# 0413.net
KiCad netlist of a schematic drawn in Altium Designer
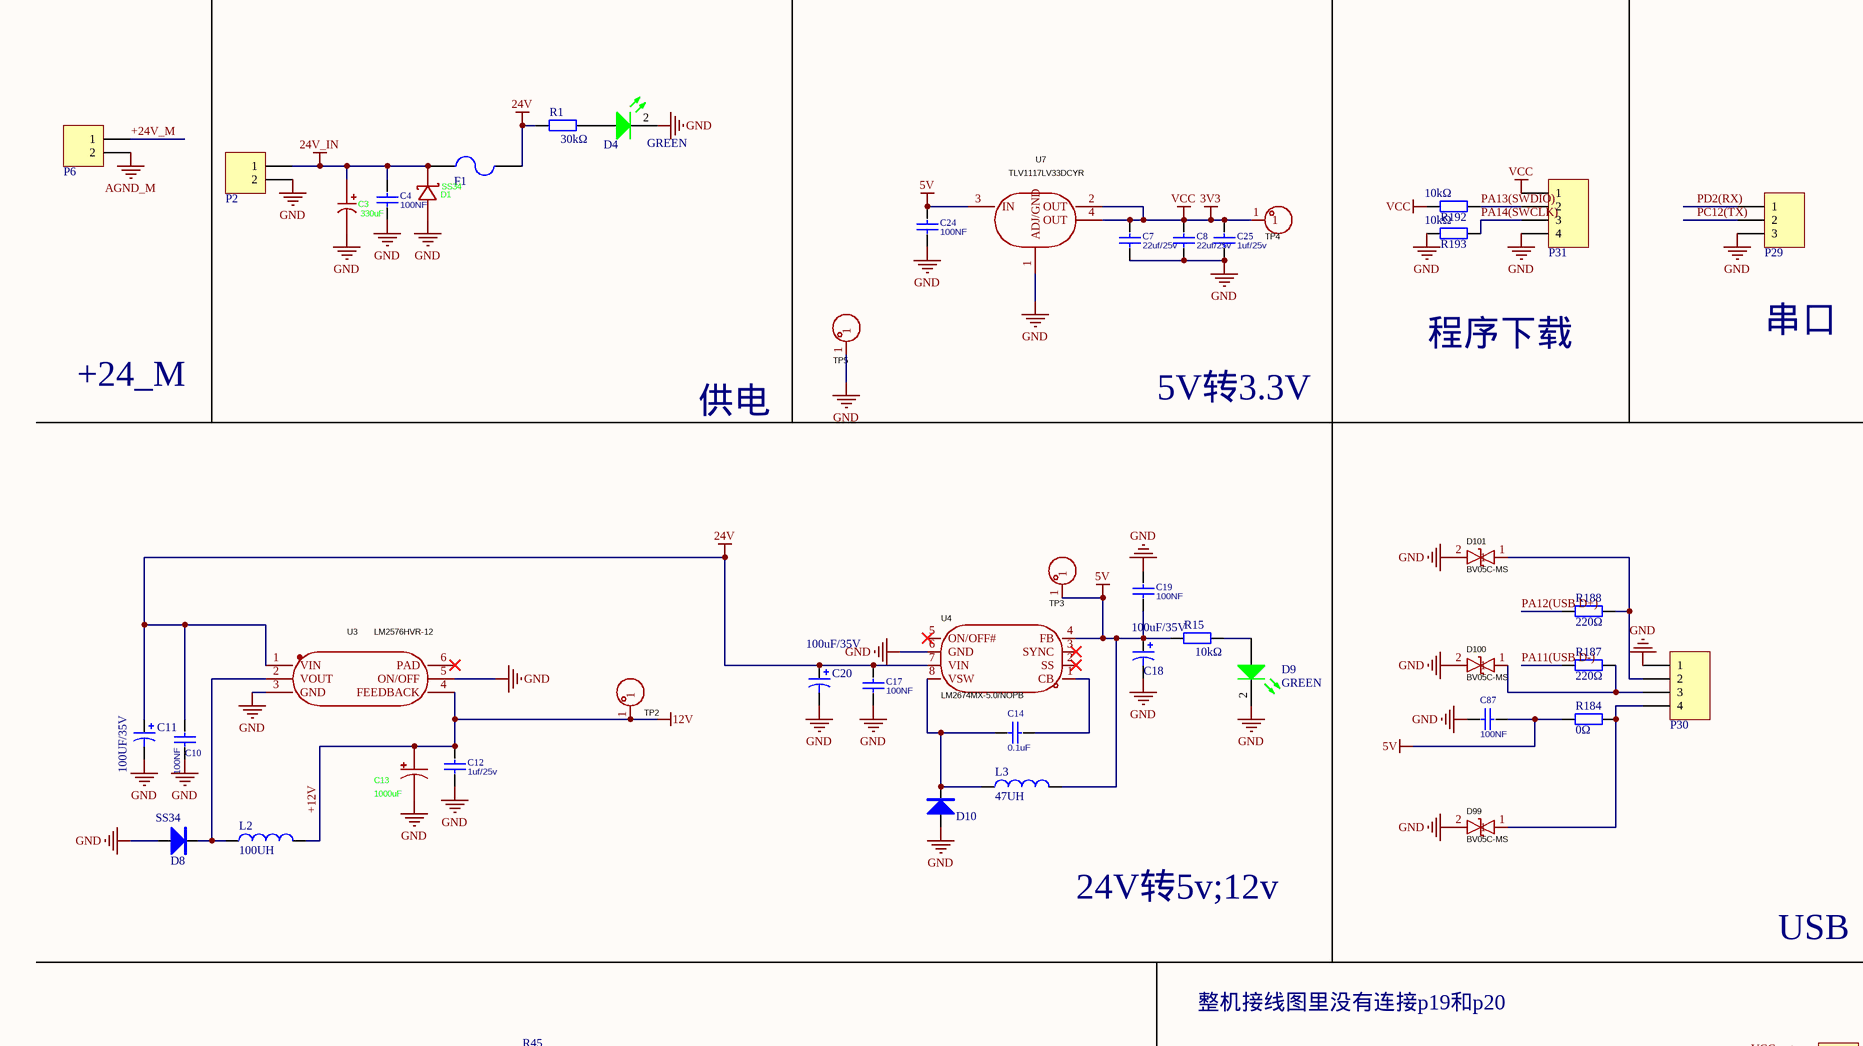
[diagram p0: 主控板0413.SchDoc, top left]
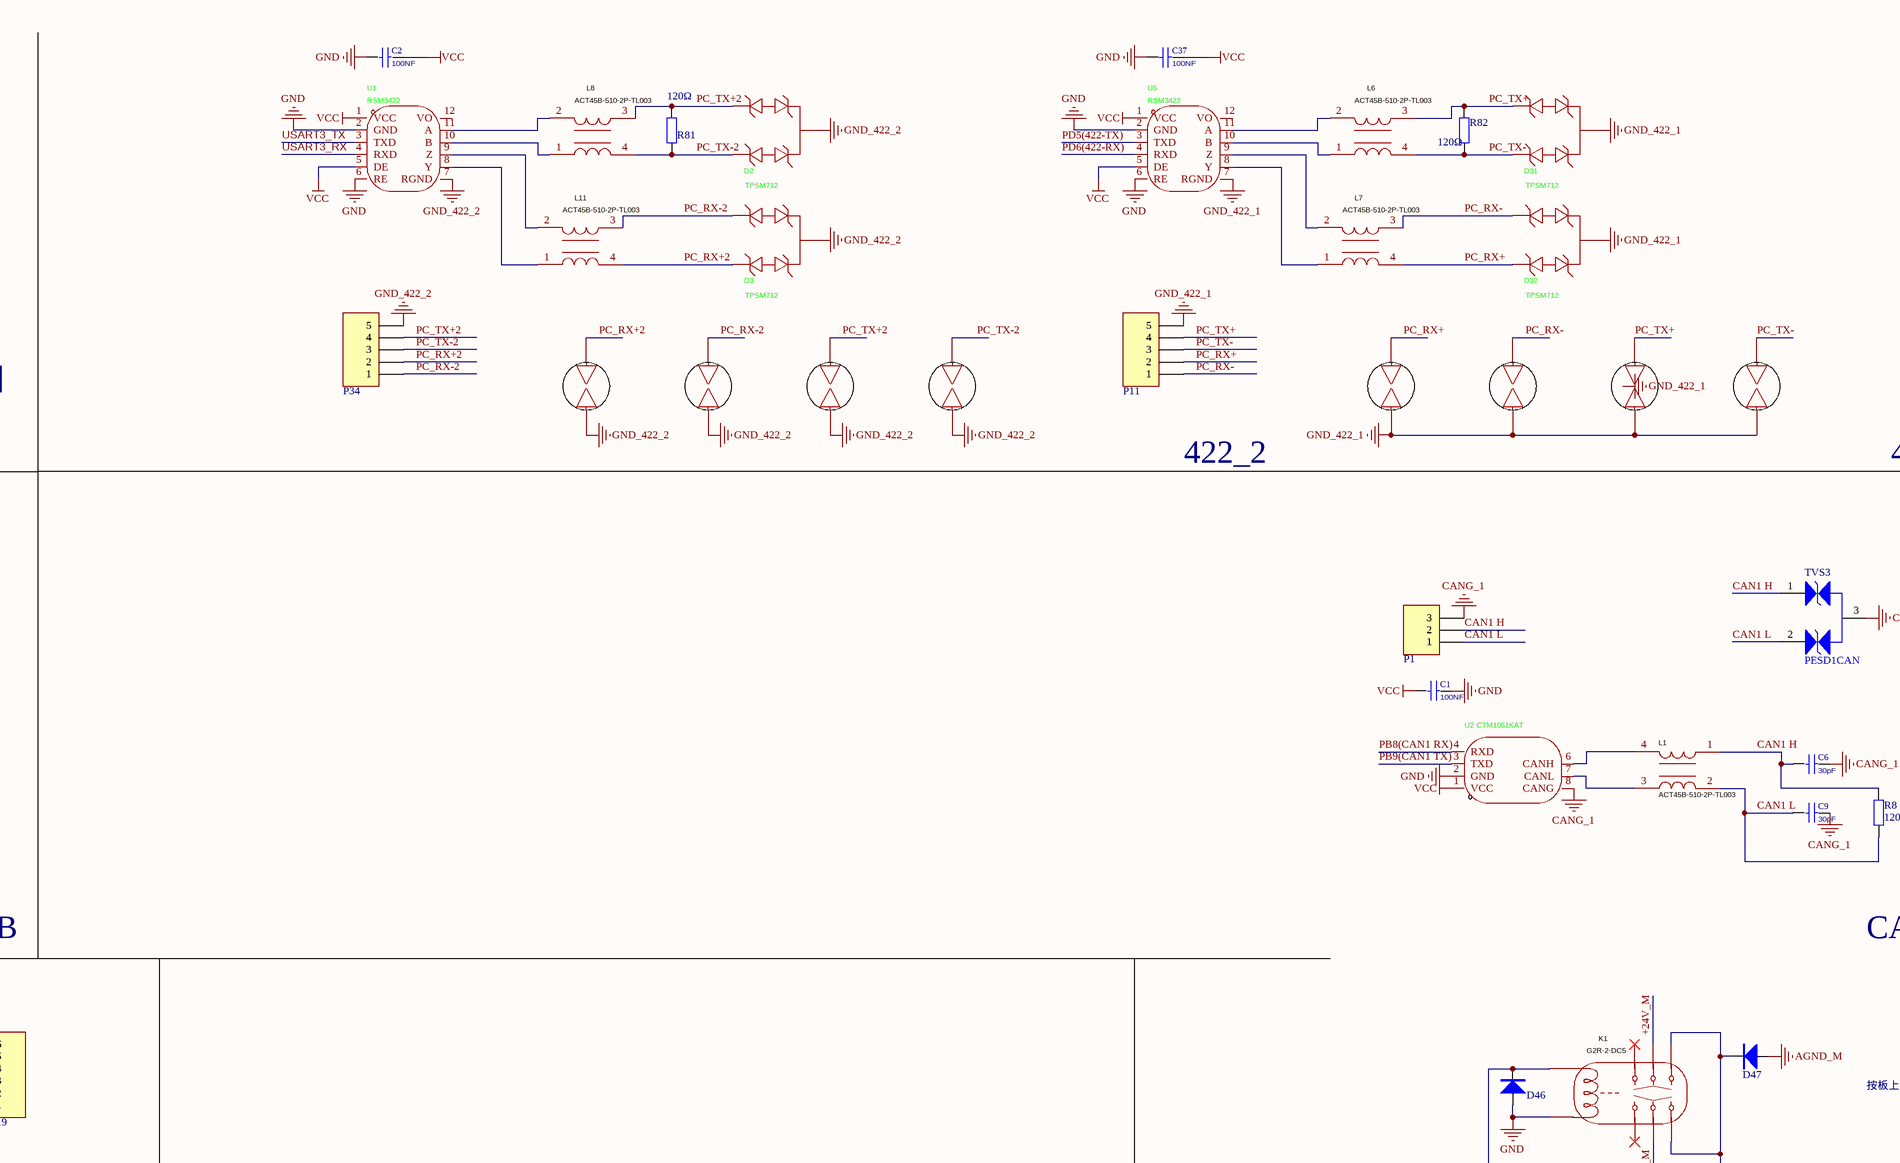
[diagram p1: 主控板0413.SchDoc, top middle]
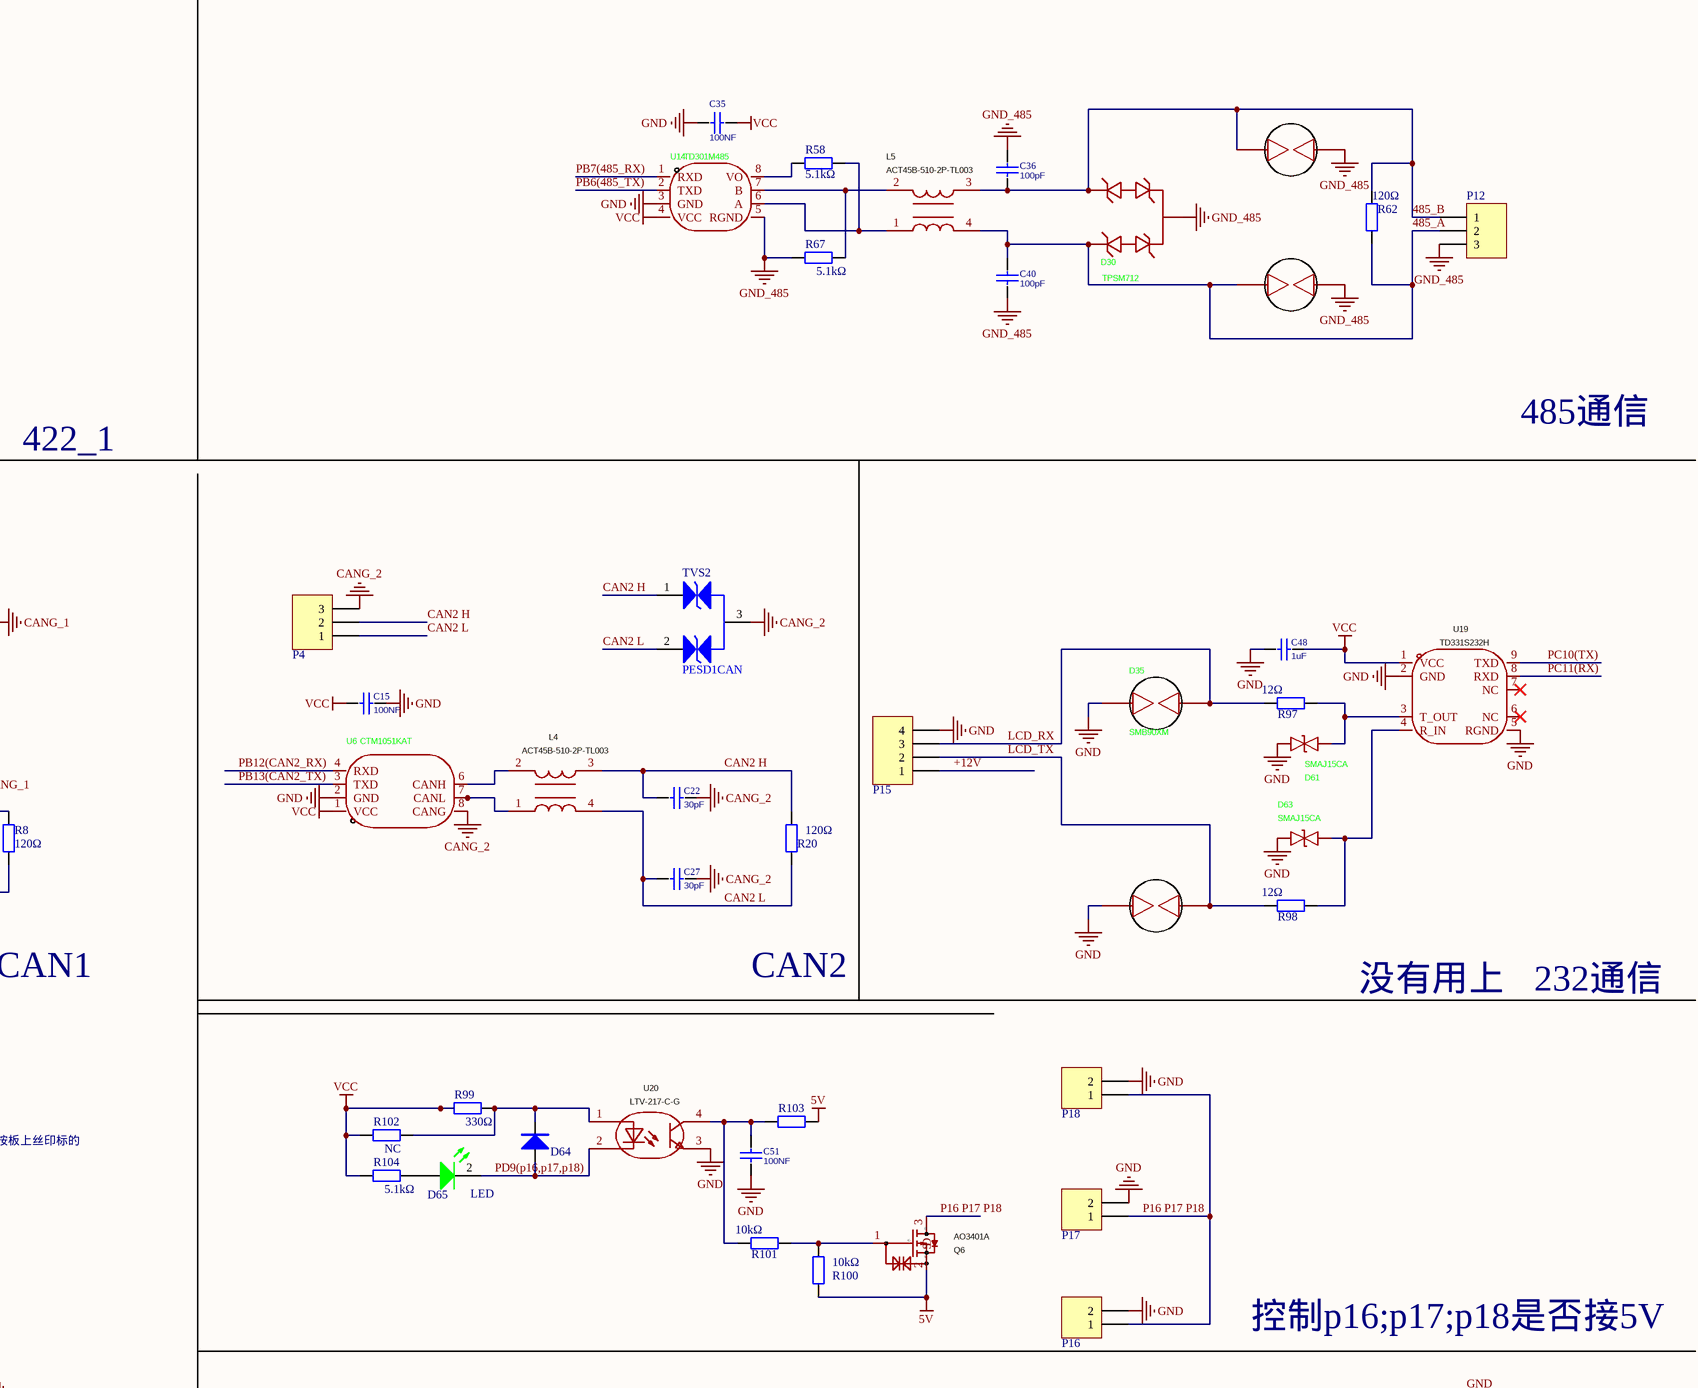
[diagram p2: 主控板0413.SchDoc, top right]
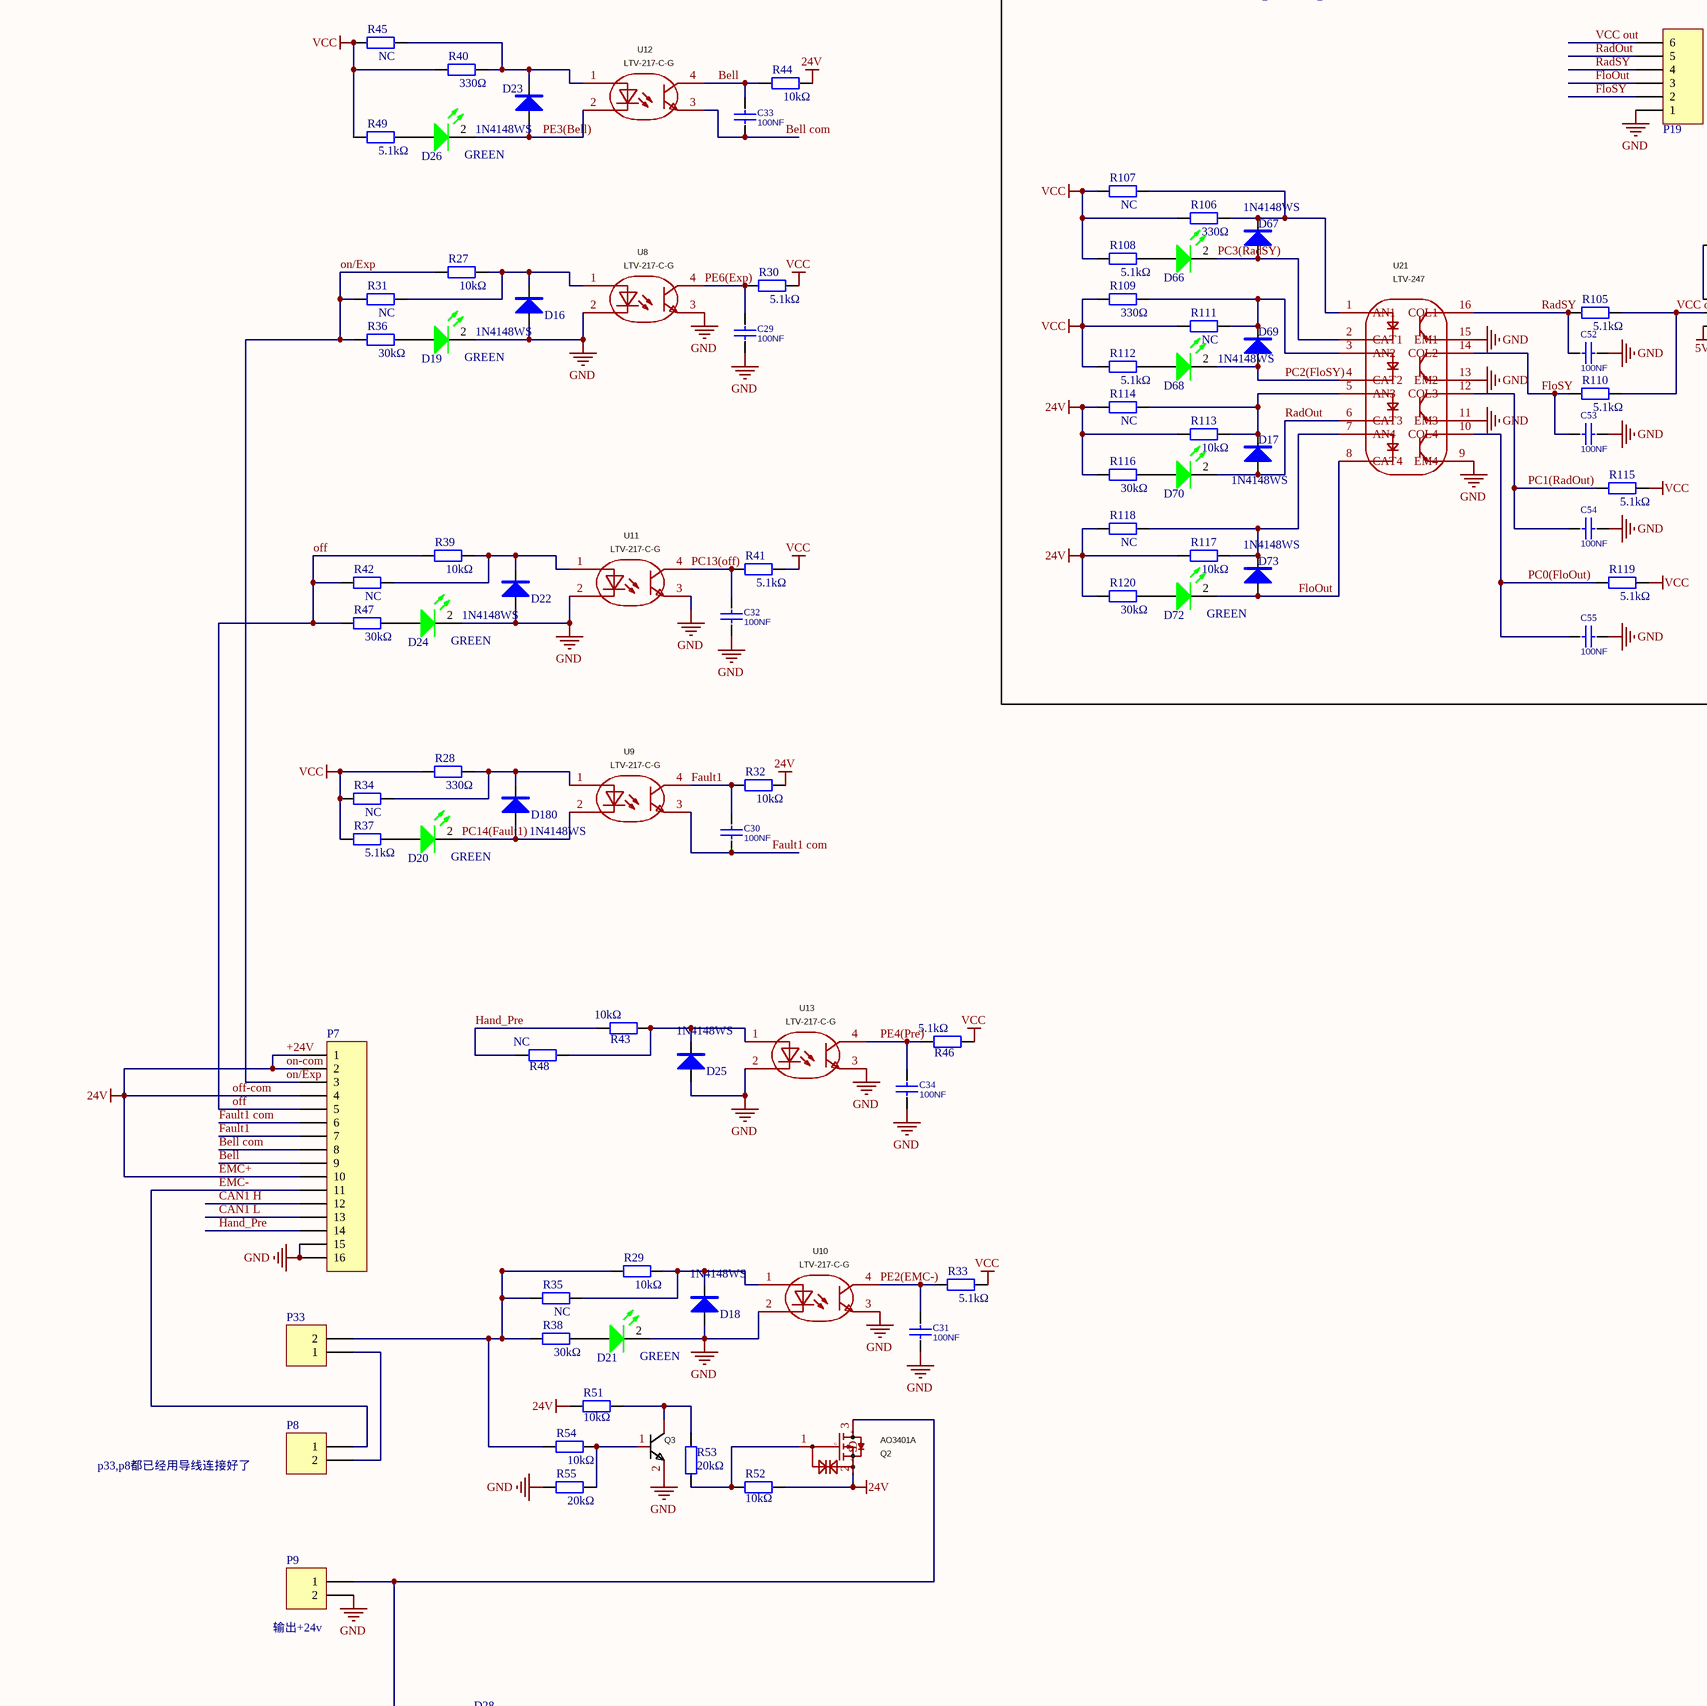
[diagram p3: 主控板0413.SchDoc, centre left]
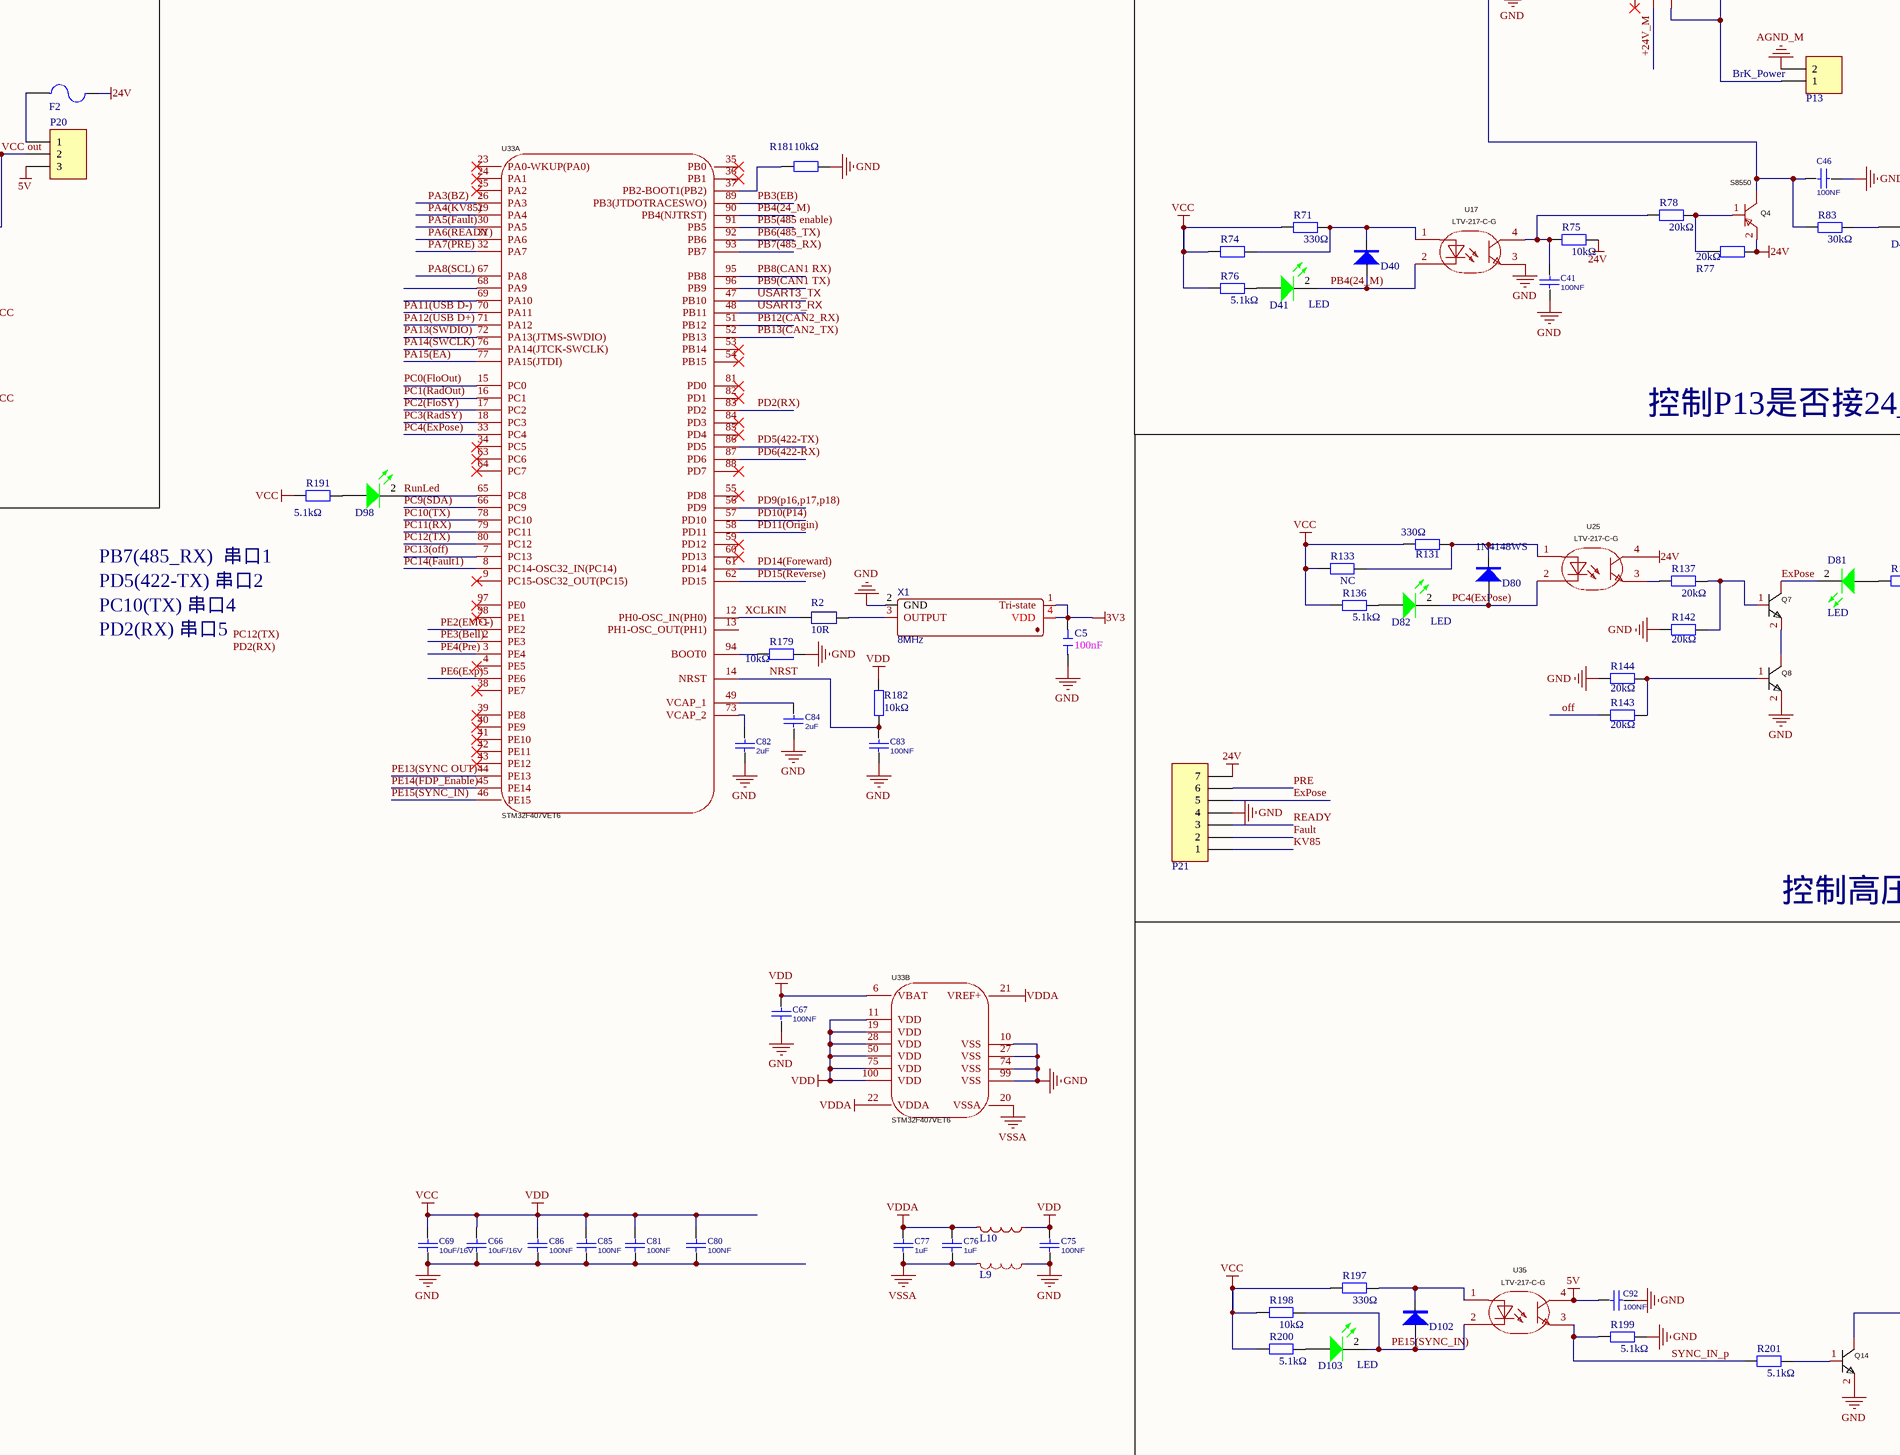
[diagram p4: 主控板0413.SchDoc, centre middle]
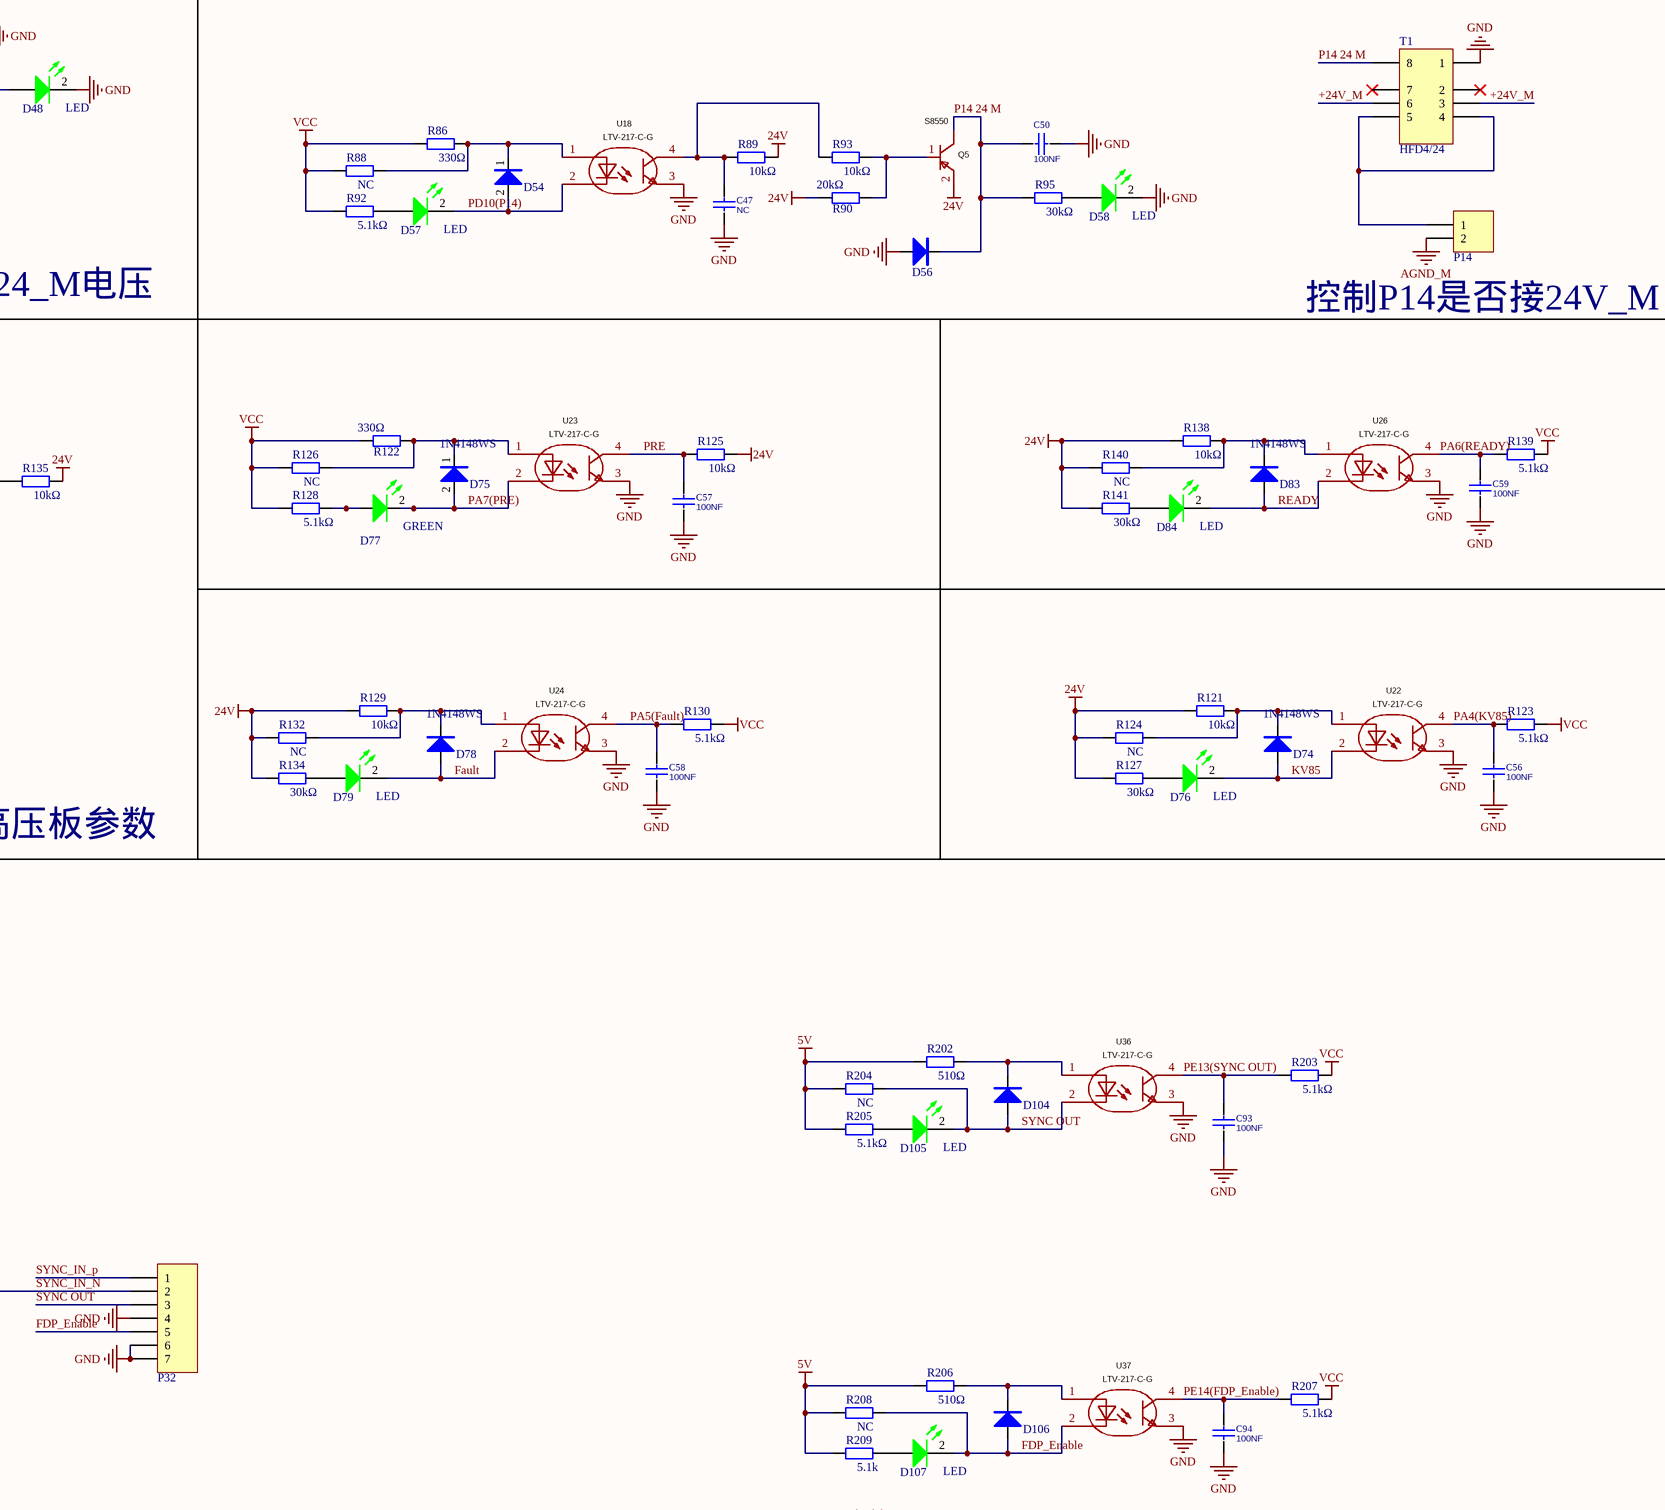
[diagram p5: 主控板0413.SchDoc, centre right]
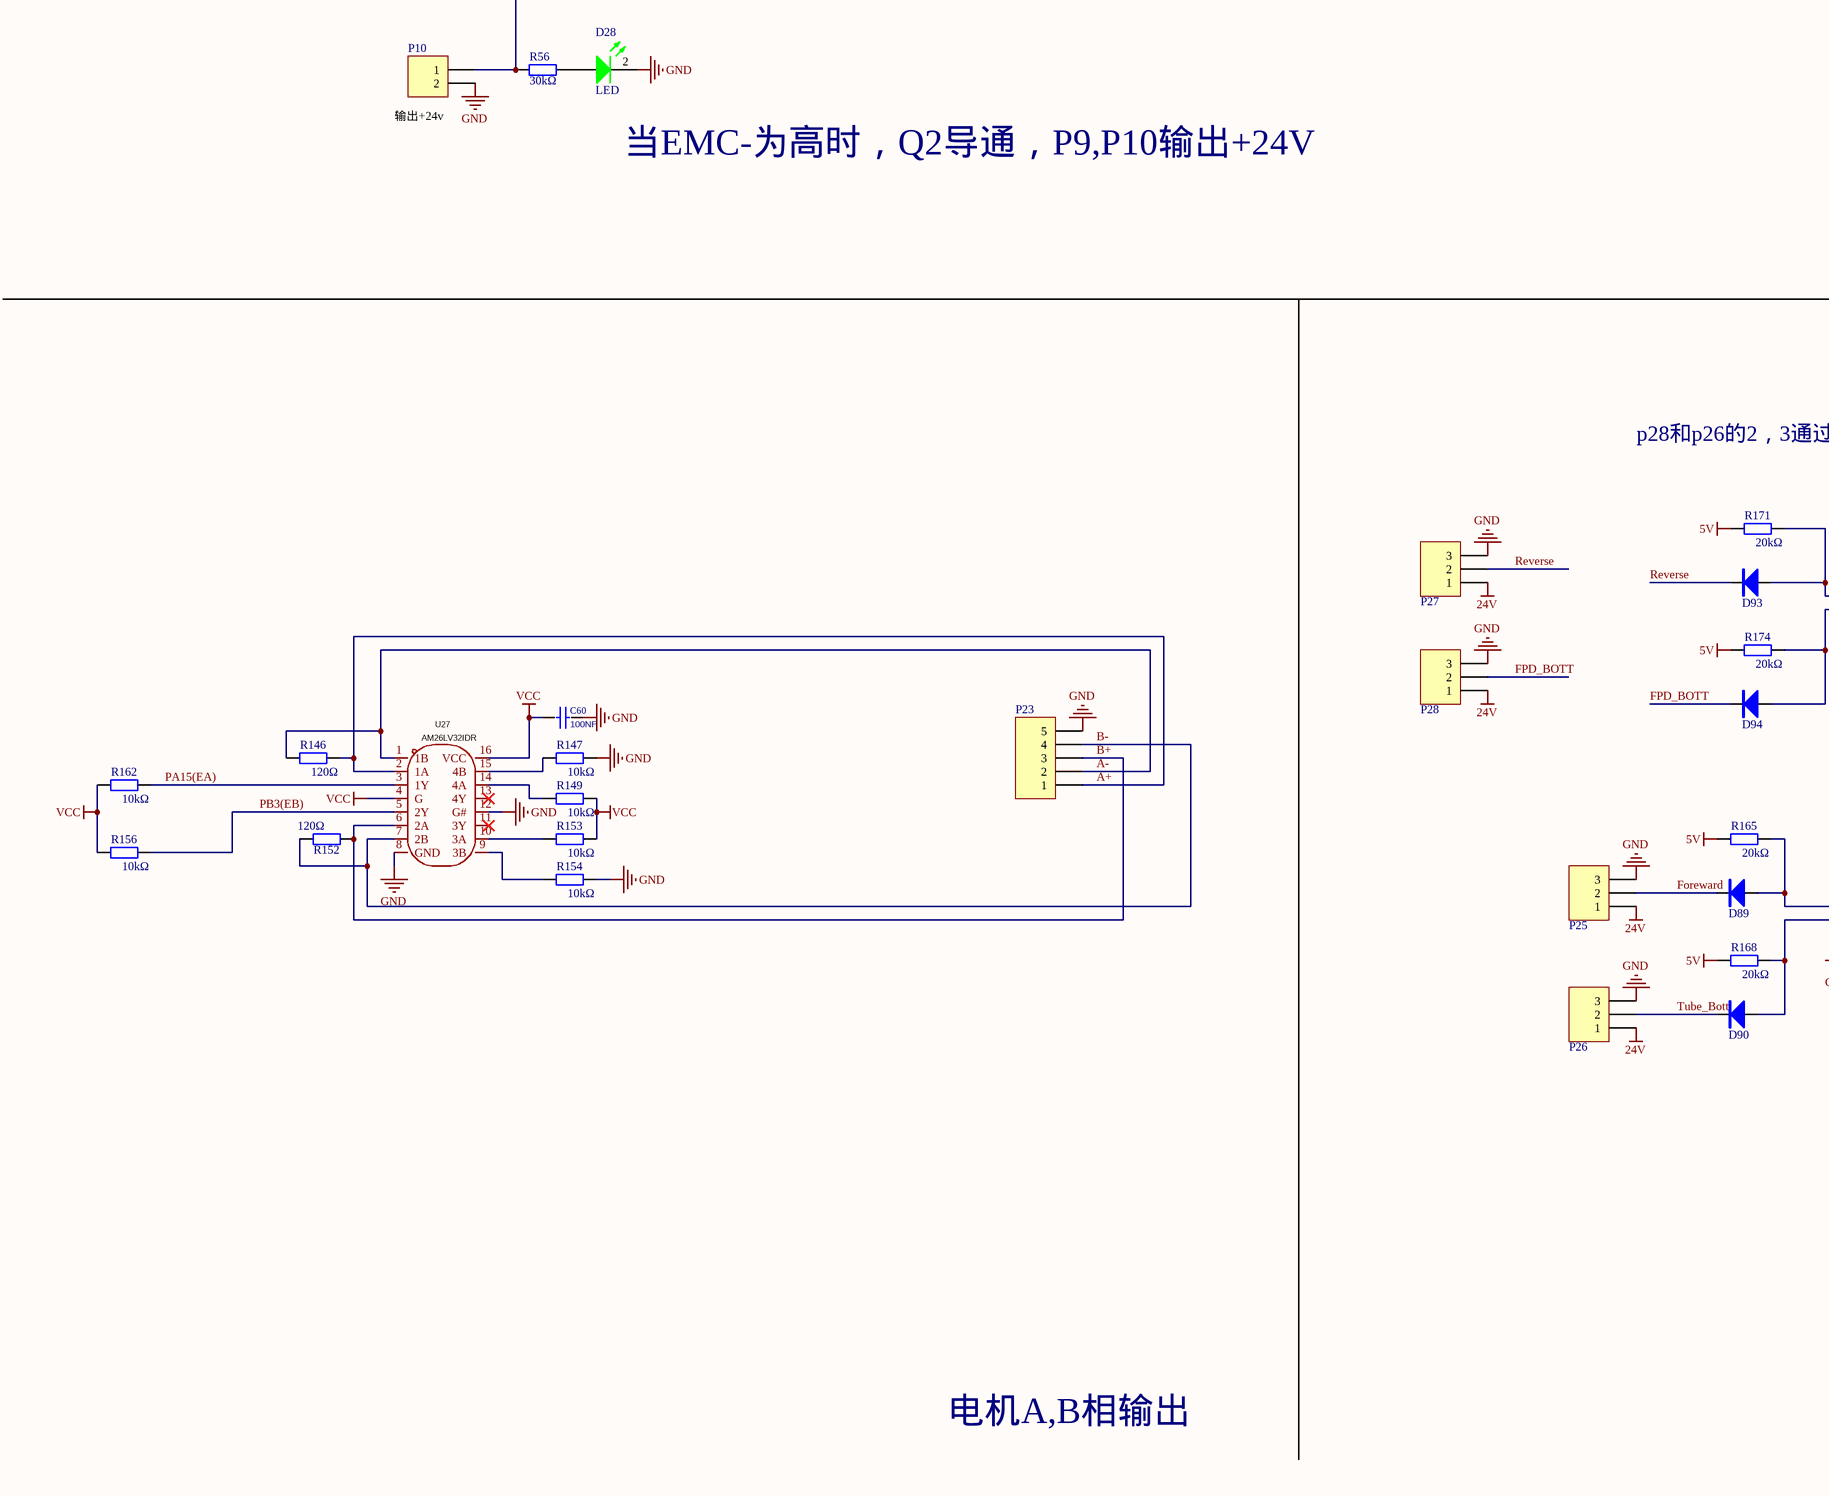
[diagram p6: 主控板0413.SchDoc, bottom left]
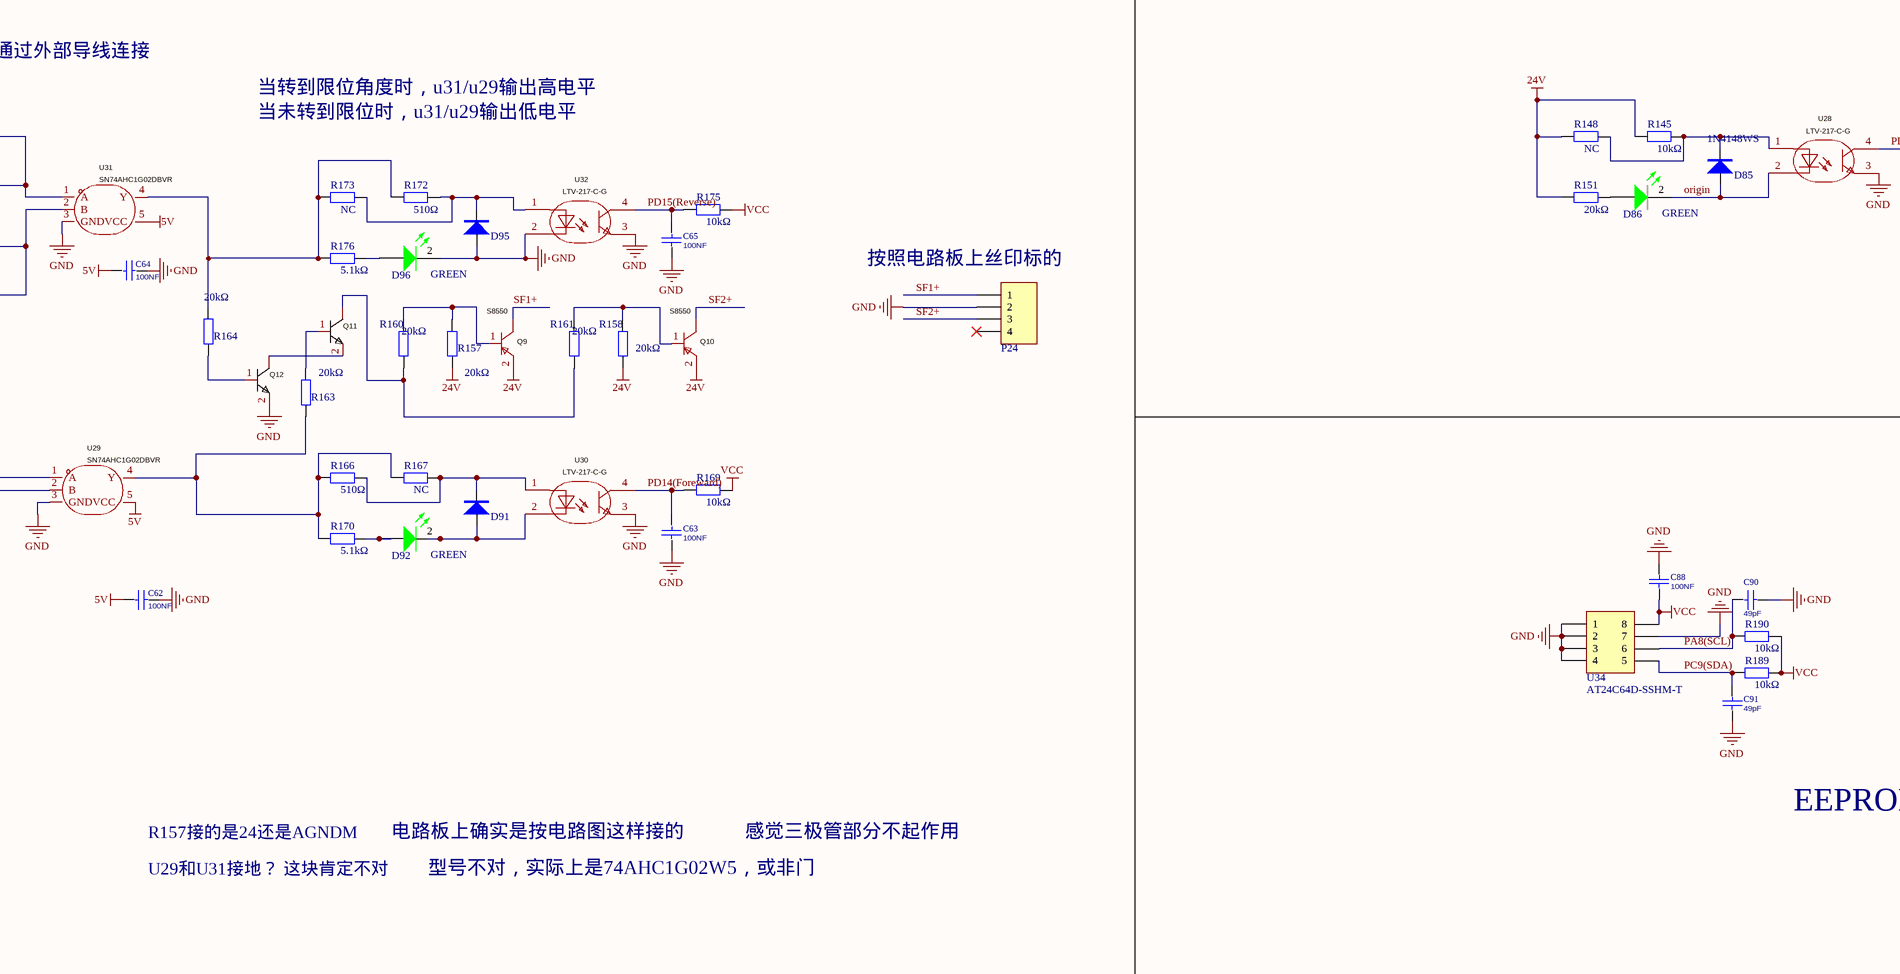
[diagram p7: 主控板0413.SchDoc, bottom middle]
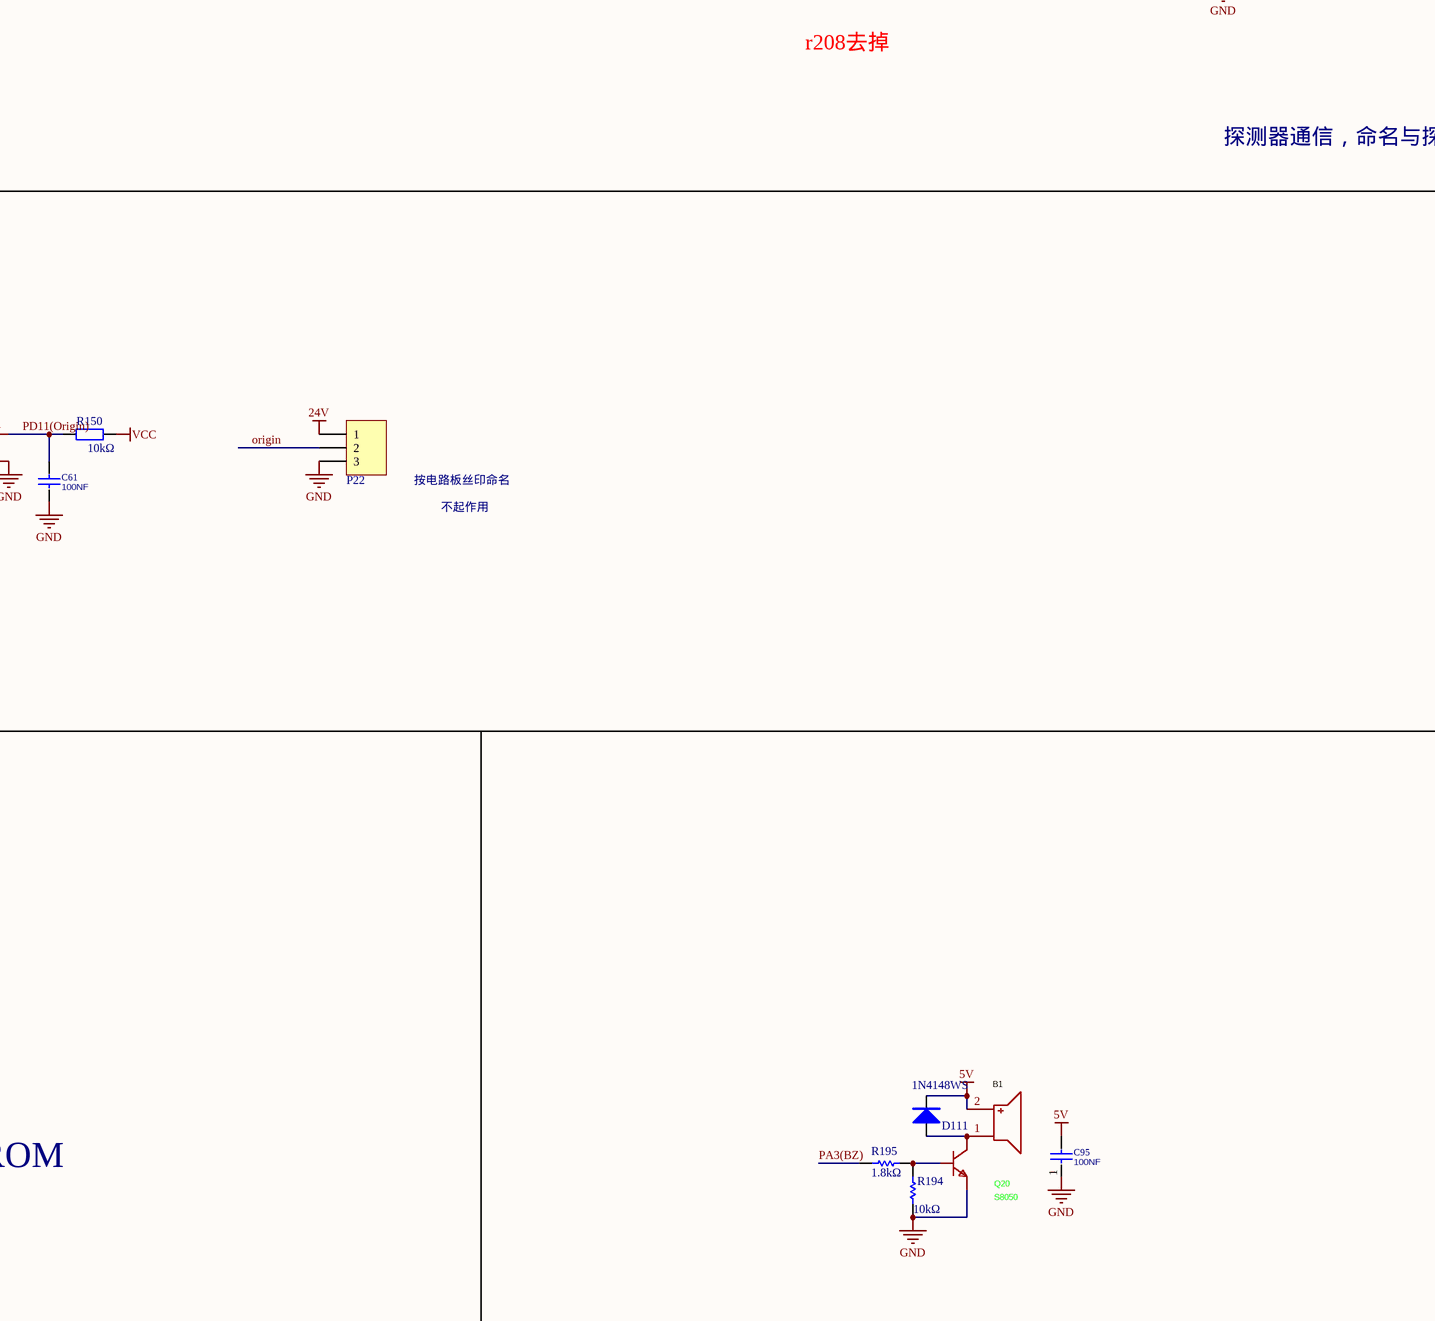
[diagram p8: 主控板0413.SchDoc, bottom right]

(export (version "E")
  (design (tool "Eeschema 10.0.6"))
  (components
    (comp (ref "B1")
      (value "~")
      (footprint "CPA5")
      (fields (field (name "MANUFACTURER") "华能") (field (name "MANUFACTURER PART") "QMB-09B-03"))
      (libsource (lib "小板1_1") (part "QMB-09B-03"))
    )
    (comp (ref "C1")
      (value "100NF")
      (footprint "C0603")
      (description "贴片电容 10uF/X5R/20%/6.3V")
      (fields (field (name "PUBLISHER") "Altium Limited"))
      (libsource (lib "*") (part "CAP"))
    )
    (comp (ref "C2")
      (value "100NF")
      (footprint "C0603")
      (description "贴片电容 10uF/X5R/20%/6.3V")
      (fields (field (name "PUBLISHER") "Altium Limited"))
      (libsource (lib "*") (part "CAP"))
    )
    (comp (ref "C3")
      (value "330uF")
      (footprint "CAP-TH_BD8.0-P3.50-D0.5-FD")
      (fields (field (name "MANUFACTURER PART") "JBLH2331M035D120RLM 330UF 35V"))
      (libsource (lib "altium-import") (part "root_3_JBLH2331M035D120RLM 330UF 35V_"))
    )
    (comp (ref "C4")
      (value "100NF")
      (footprint "C1206")
      (description "贴片电容 10uF/X5R/20%/6.3V")
      (fields (field (name "PUBLISHER") "Altium Limited"))
      (libsource (lib "*") (part "CAP"))
    )
    (comp (ref "C5")
      (value "100nF")
      (footprint "C0603")
      (description "Capacitor")
      (libsource (lib "") (part "CAP_1"))
    )
    (comp (ref "C6")
      (value "30pF")
      (footprint "C0603")
      (description "贴片电容 10uF/X5R/20%/6.3V")
      (fields (field (name "PUBLISHER") "Altium Limited"))
      (libsource (lib "*") (part "CAP"))
    )
    (comp (ref "C7")
      (value "22uf/25v")
      (footprint "C0805")
      (fields (field (name "PUBLISHER") "Altium Limited"))
      (libsource (lib "*") (part "CAP"))
    )
    (comp (ref "C8")
      (value "22uf/25v")
      (footprint "C0805")
      (fields (field (name "PUBLISHER") "Altium Limited"))
      (libsource (lib "*") (part "CAP"))
    )
    (comp (ref "C9")
      (value "30pF")
      (footprint "C0603")
      (description "贴片电容 10uF/X5R/20%/6.3V")
      (fields (field (name "PUBLISHER") "Altium Limited"))
      (libsource (lib "*") (part "CAP"))
    )
    (comp (ref "C10")
      (value "100NF")
      (footprint "C0603")
      (description "贴片电容 10uF/X5R/20%/6.3V")
      (fields (field (name "PUBLISHER") "Altium Limited"))
      (libsource (lib "*") (part "CAP"))
    )
    (comp (ref "C11")
      (value "100UF/35V")
      (footprint "CAP10")
      (description "Polarized Capacitor (Radial)")
      (fields (field (name "PUBLISHER") "Altium Limited"))
      (libsource (lib "Miscellaneous Devices") (part "Cap Pol1"))
    )
    (comp (ref "C12")
      (value "1uf/25v")
      (footprint "C0603")
      (fields (field (name "PUBLISHER") "Altium Limited"))
      (libsource (lib "*") (part "CAP"))
    )
    (comp (ref "C13")
      (value "1000uF")
      (footprint "CAP-TH_BD10.0-P5.00-D1.0-FD")
      (fields (field (name "MANUFACTURER PART") "ORZ102M1CBK-1012"))
      (libsource (lib "altium-import") (part "root_0_ORZ102M1CBK-1012_"))
    )
    (comp (ref "C14")
      (value "0.1uF")
      (footprint "C0603")
      (fields (field (name "PUBLISHER") "Altium Limited"))
      (libsource (lib "*") (part "CAP"))
    )
    (comp (ref "C15")
      (value "100NF")
      (footprint "C0603")
      (description "贴片电容 10uF/X5R/20%/6.3V")
      (fields (field (name "PUBLISHER") "Altium Limited"))
      (libsource (lib "*") (part "CAP"))
    )
    (comp (ref "C17")
      (value "100NF")
      (footprint "C1206")
      (description "贴片电容 10uF/X5R/20%/6.3V")
      (fields (field (name "PUBLISHER") "Altium Limited"))
      (libsource (lib "*") (part "CAP"))
    )
    (comp (ref "C18")
      (value "100uF/35V")
      (footprint "CAP10")
      (description "Polarized Capacitor (Radial)")
      (fields (field (name "PUBLISHER") "Altium Limited"))
      (libsource (lib "Miscellaneous Devices") (part "Cap Pol1"))
    )
    (comp (ref "C19")
      (value "100NF")
      (footprint "C0603")
      (description "贴片电容 10uF/X5R/20%/6.3V")
      (fields (field (name "PUBLISHER") "Altium Limited"))
      (libsource (lib "*") (part "CAP"))
    )
    (comp (ref "C20")
      (value "100uF/35V")
      (footprint "CAP10")
      (description "Polarized Capacitor (Radial)")
      (fields (field (name "PUBLISHER") "Altium Limited"))
      (libsource (lib "Miscellaneous Devices") (part "Cap Pol1"))
    )
    (comp (ref "C22")
      (value "30pF")
      (footprint "C0603")
      (description "贴片电容 10uF/X5R/20%/6.3V")
      (fields (field (name "PUBLISHER") "Altium Limited"))
      (libsource (lib "*") (part "CAP"))
    )
    (comp (ref "C24")
      (value "100NF")
      (footprint "C0603")
      (description "贴片电容 10uF/X5R/20%/6.3V")
      (fields (field (name "PUBLISHER") "Altium Limited"))
      (libsource (lib "*") (part "CAP"))
    )
    (comp (ref "C25")
      (value "1uf/25v")
      (footprint "C0603")
      (fields (field (name "PUBLISHER") "Altium Limited"))
      (libsource (lib "*") (part "CAP"))
    )
    (comp (ref "C27")
      (value "30pF")
      (footprint "C0603")
      (description "贴片电容 10uF/X5R/20%/6.3V")
      (fields (field (name "PUBLISHER") "Altium Limited"))
      (libsource (lib "*") (part "CAP"))
    )
    (comp (ref "C29")
      (value "100NF")
      (footprint "C0603")
      (description "贴片电容 10uF/X5R/20%/6.3V")
      (fields (field (name "PUBLISHER") "Altium Limited"))
      (libsource (lib "*") (part "CAP"))
    )
    (comp (ref "C30")
      (value "100NF")
      (footprint "C0603")
      (description "贴片电容 10uF/X5R/20%/6.3V")
      (fields (field (name "PUBLISHER") "Altium Limited"))
      (libsource (lib "*") (part "CAP"))
    )
    (comp (ref "C31")
      (value "100NF")
      (footprint "C0603")
      (description "贴片电容 10uF/X5R/20%/6.3V")
      (fields (field (name "PUBLISHER") "Altium Limited"))
      (libsource (lib "*") (part "CAP"))
    )
    (comp (ref "C32")
      (value "100NF")
      (footprint "C0603")
      (description "贴片电容 10uF/X5R/20%/6.3V")
      (fields (field (name "PUBLISHER") "Altium Limited"))
      (libsource (lib "*") (part "CAP"))
    )
    (comp (ref "C33")
      (value "100NF")
      (footprint "C0603")
      (description "贴片电容 10uF/X5R/20%/6.3V")
      (fields (field (name "PUBLISHER") "Altium Limited"))
      (libsource (lib "*") (part "CAP"))
    )
    (comp (ref "C34")
      (value "100NF")
      (footprint "C0603")
      (description "贴片电容 10uF/X5R/20%/6.3V")
      (fields (field (name "PUBLISHER") "Altium Limited"))
      (libsource (lib "*") (part "CAP"))
    )
    (comp (ref "C35")
      (value "100NF")
      (footprint "C0603")
      (description "贴片电容 10uF/X5R/20%/6.3V")
      (fields (field (name "PUBLISHER") "Altium Limited"))
      (libsource (lib "*") (part "CAP"))
    )
    (comp (ref "C36")
      (value "100pF")
      (footprint "C0603")
      (description "贴片电容 10uF/X5R/20%/6.3V")
      (fields (field (name "PUBLISHER") "Altium Limited"))
      (libsource (lib "*") (part "CAP"))
    )
    (comp (ref "C37")
      (value "100NF")
      (footprint "C0603")
      (description "贴片电容 10uF/X5R/20%/6.3V")
      (fields (field (name "PUBLISHER") "Altium Limited"))
      (libsource (lib "*") (part "CAP"))
    )
    (comp (ref "C40")
      (value "100pF")
      (footprint "C0603")
      (description "贴片电容 10uF/X5R/20%/6.3V")
      (fields (field (name "PUBLISHER") "Altium Limited"))
      (libsource (lib "*") (part "CAP"))
    )
    (comp (ref "C41")
      (value "100NF")
      (footprint "C0603")
      (description "贴片电容 10uF/X5R/20%/6.3V")
      (fields (field (name "PUBLISHER") "Altium Limited"))
      (libsource (lib "*") (part "CAP"))
    )
    (comp (ref "C46")
      (value "100NF")
      (footprint "C0603")
      (description "贴片电容 10uF/X5R/20%/6.3V")
      (fields (field (name "PUBLISHER") "Altium Limited"))
      (libsource (lib "*") (part "CAP"))
    )
    (comp (ref "C47")
      (value "NC")
      (footprint "C0603")
      (description "贴片电容 10uF/X5R/20%/6.3V")
      (fields (field (name "PUBLISHER") "Altium Limited"))
      (libsource (lib "*") (part "CAP"))
    )
    (comp (ref "C48")
      (value "1uF")
      (footprint "C0603")
      (description "贴片电容 10uF/X5R/20%/6.3V")
      (fields (field (name "PUBLISHER") "Altium Limited"))
      (libsource (lib "*") (part "CAP"))
    )
    (comp (ref "C50")
      (value "100NF")
      (footprint "C0603")
      (description "贴片电容 10uF/X5R/20%/6.3V")
      (fields (field (name "PUBLISHER") "Altium Limited"))
      (libsource (lib "*") (part "CAP"))
    )
    (comp (ref "C51")
      (value "100NF")
      (footprint "C0603")
      (description "贴片电容 10uF/X5R/20%/6.3V")
      (fields (field (name "PUBLISHER") "Altium Limited"))
      (libsource (lib "*") (part "CAP"))
    )
    (comp (ref "C52")
      (value "100NF")
      (footprint "C0603")
      (description "贴片电容 10uF/X5R/20%/6.3V")
      (fields (field (name "PUBLISHER") "Altium Limited"))
      (libsource (lib "*") (part "CAP"))
    )
    (comp (ref "C53")
      (value "100NF")
      (footprint "C0603")
      (description "贴片电容 10uF/X5R/20%/6.3V")
      (fields (field (name "PUBLISHER") "Altium Limited"))
      (libsource (lib "*") (part "CAP"))
    )
    (comp (ref "C54")
      (value "100NF")
      (footprint "C0603")
      (description "贴片电容 10uF/X5R/20%/6.3V")
      (fields (field (name "PUBLISHER") "Altium Limited"))
      (libsource (lib "*") (part "CAP"))
    )
    (comp (ref "C55")
      (value "100NF")
      (footprint "C0603")
      (description "贴片电容 10uF/X5R/20%/6.3V")
      (fields (field (name "PUBLISHER") "Altium Limited"))
      (libsource (lib "*") (part "CAP"))
    )
    (comp (ref "C56")
      (value "100NF")
      (footprint "C0603")
      (description "贴片电容 10uF/X5R/20%/6.3V")
      (fields (field (name "PUBLISHER") "Altium Limited"))
      (libsource (lib "*") (part "CAP"))
    )
    (comp (ref "C57")
      (value "100NF")
      (footprint "C0603")
      (description "贴片电容 10uF/X5R/20%/6.3V")
      (fields (field (name "PUBLISHER") "Altium Limited"))
      (libsource (lib "*") (part "CAP"))
    )
    (comp (ref "C58")
      (value "100NF")
      (footprint "C0603")
      (description "贴片电容 10uF/X5R/20%/6.3V")
      (fields (field (name "PUBLISHER") "Altium Limited"))
      (libsource (lib "*") (part "CAP"))
    )
    (comp (ref "C59")
      (value "100NF")
      (footprint "C0603")
      (description "贴片电容 10uF/X5R/20%/6.3V")
      (fields (field (name "PUBLISHER") "Altium Limited"))
      (libsource (lib "*") (part "CAP"))
    )
    (comp (ref "C60")
      (value "100NF")
      (footprint "C0603")
      (description "贴片电容 10uF/X5R/20%/6.3V")
      (fields (field (name "PUBLISHER") "Altium Limited"))
      (libsource (lib "*") (part "CAP"))
    )
    (comp (ref "C61")
      (value "100NF")
      (footprint "C0603")
      (description "贴片电容 10uF/X5R/20%/6.3V")
      (fields (field (name "PUBLISHER") "Altium Limited"))
      (libsource (lib "*") (part "CAP"))
    )
    (comp (ref "C62")
      (value "100NF")
      (footprint "C0603")
      (description "贴片电容 10uF/X5R/20%/6.3V")
      (fields (field (name "PUBLISHER") "Altium Limited"))
      (libsource (lib "*") (part "CAP"))
    )
    (comp (ref "C63")
      (value "100NF")
      (footprint "C0603")
      (description "贴片电容 10uF/X5R/20%/6.3V")
      (fields (field (name "PUBLISHER") "Altium Limited"))
      (libsource (lib "*") (part "CAP"))
    )
    (comp (ref "C64")
      (value "100NF")
      (footprint "C0603")
      (description "贴片电容 10uF/X5R/20%/6.3V")
      (fields (field (name "PUBLISHER") "Altium Limited"))
      (libsource (lib "*") (part "CAP"))
    )
    (comp (ref "C65")
      (value "100NF")
      (footprint "C0603")
      (description "贴片电容 10uF/X5R/20%/6.3V")
      (fields (field (name "PUBLISHER") "Altium Limited"))
      (libsource (lib "*") (part "CAP"))
    )
    (comp (ref "C66")
      (value "10uF/16V")
      (footprint "C0603")
      (fields (field (name "PUBLISHER") "Altium Limited"))
      (libsource (lib "*") (part "CAP"))
    )
    (comp (ref "C67")
      (value "100NF")
      (footprint "C0603")
      (description "贴片电容 10uF/X5R/20%/6.3V")
      (fields (field (name "PUBLISHER") "Altium Limited"))
      (libsource (lib "*") (part "CAP"))
    )
    (comp (ref "C69")
      (value "10uF/16V")
      (footprint "C0603")
      (fields (field (name "PUBLISHER") "Altium Limited"))
      (libsource (lib "*") (part "CAP"))
    )
    (comp (ref "C75")
      (value "100NF")
      (footprint "C0603")
      (description "贴片电容 10uF/X5R/20%/6.3V")
      (fields (field (name "PUBLISHER") "Altium Limited"))
      (libsource (lib "*") (part "CAP"))
    )
    (comp (ref "C76")
      (value "1uF")
      (footprint "C0603")
      (description "贴片电容 10uF/X5R/20%/6.3V")
      (fields (field (name "PUBLISHER") "Altium Limited"))
      (libsource (lib "*") (part "CAP"))
    )
    (comp (ref "C77")
      (value "1uF")
      (footprint "C0603")
      (description "贴片电容 10uF/X5R/20%/6.3V")
      (fields (field (name "PUBLISHER") "Altium Limited"))
      (libsource (lib "*") (part "CAP"))
    )
    (comp (ref "C80")
      (value "100NF")
      (footprint "C0603")
      (description "贴片电容 10uF/X5R/20%/6.3V")
      (fields (field (name "PUBLISHER") "Altium Limited"))
      (libsource (lib "*") (part "CAP"))
    )
    (comp (ref "C81")
      (value "100NF")
      (footprint "C0603")
      (description "贴片电容 10uF/X5R/20%/6.3V")
      (fields (field (name "PUBLISHER") "Altium Limited"))
      (libsource (lib "*") (part "CAP"))
    )
    (comp (ref "C82")
      (value "2uF")
      (footprint "C0603")
      (description "贴片电容 10uF/X5R/20%/6.3V")
      (fields (field (name "PUBLISHER") "Altium Limited"))
      (libsource (lib "*") (part "CAP"))
    )
    (comp (ref "C83")
      (value "100NF")
      (footprint "C0603")
      (description "贴片电容 10uF/X5R/20%/6.3V")
      (fields (field (name "PUBLISHER") "Altium Limited"))
      (libsource (lib "*") (part "CAP"))
    )
    (comp (ref "C84")
      (value "2uF")
      (footprint "C0603")
      (description "贴片电容 10uF/X5R/20%/6.3V")
      (fields (field (name "PUBLISHER") "Altium Limited"))
      (libsource (lib "*") (part "CAP"))
    )
    (comp (ref "C85")
      (value "100NF")
      (footprint "C0603")
      (description "贴片电容 10uF/X5R/20%/6.3V")
      (fields (field (name "PUBLISHER") "Altium Limited"))
      (libsource (lib "*") (part "CAP"))
    )
    (comp (ref "C86")
      (value "100NF")
      (footprint "C0603")
      (fields (field (name "PUBLISHER") "Altium Limited"))
      (libsource (lib "*") (part "CAP"))
    )
    (comp (ref "C87")
      (value "100NF")
      (footprint "C0603")
      (description "贴片电容 10uF/X5R/20%/6.3V")
      (fields (field (name "PUBLISHER") "Altium Limited"))
      (libsource (lib "*") (part "CAP"))
    )
    (comp (ref "C88")
      (value "100NF")
      (footprint "C0603")
      (description "贴片电容 10uF/X5R/20%/6.3V")
      (fields (field (name "PUBLISHER") "Altium Limited"))
      (libsource (lib "*") (part "CAP"))
    )
    (comp (ref "C90")
      (value "49pF")
      (footprint "C0603")
      (description "贴片电容 10uF/X5R/20%/6.3V")
      (fields (field (name "PUBLISHER") "Altium Limited"))
      (libsource (lib "*") (part "CAP"))
    )
    (comp (ref "C91")
      (value "49pF")
      (footprint "C0603")
      (description "贴片电容 10uF/X5R/20%/6.3V")
      (fields (field (name "PUBLISHER") "Altium Limited"))
      (libsource (lib "*") (part "CAP"))
    )
    (comp (ref "C92")
      (value "100NF")
      (footprint "C0603")
      (description "贴片电容 10uF/X5R/20%/6.3V")
      (fields (field (name "PUBLISHER") "Altium Limited"))
      (libsource (lib "*") (part "CAP"))
    )
    (comp (ref "C93")
      (value "100NF")
      (footprint "C0603")
      (description "贴片电容 10uF/X5R/20%/6.3V")
      (fields (field (name "PUBLISHER") "Altium Limited"))
      (libsource (lib "*") (part "CAP"))
    )
    (comp (ref "C94")
      (value "100NF")
      (footprint "C0603")
      (description "贴片电容 10uF/X5R/20%/6.3V")
      (fields (field (name "PUBLISHER") "Altium Limited"))
      (libsource (lib "*") (part "CAP"))
    )
    (comp (ref "C95")
      (value "100NF")
      (footprint "C0603")
      (description "贴片电容 10uF/X5R/20%/6.3V")
      (fields (field (name "PUBLISHER") "Altium Limited"))
      (libsource (lib "大板") (part "CAP"))
    )
    (comp (ref "D1")
      (value "SS34")
      (footprint "SMA_L4.3-W2.6-LS5.2-RD")
      (libsource (lib "altium-import") (part "root_3_SS34_C8678_"))
    )
    (comp (ref "D2")
      (value "TPSM712")
      (footprint "SOT-23-3_L2.9-W1.3-P1.90-LS2.4-BR")
      (libsource (lib "altium-import") (part "root_0_TPSM712_"))
    )
    (comp (ref "D3")
      (value "TPSM712")
      (footprint "SOT-23-3_L2.9-W1.3-P1.90-LS2.4-BR")
      (libsource (lib "altium-import") (part "root_0_TPSM712_"))
    )
    (comp (ref "D4")
      (value "GREEN")
      (footprint "LED0603")
      (description "LED")
      (libsource (lib "小板1_1") (part "GREEN LED"))
    )
    (comp (ref "D5")
      (value "SMB90XM")
      (footprint "DIO-DT-SMD_L3.2-W1.6")
      (libsource (lib "altium-import") (part "root_1_SMB90XM_"))
    )
    (comp (ref "D6")
      (value "SMB90XM")
      (footprint "DIO-DT-SMD_L3.2-W1.6")
      (libsource (lib "altium-import") (part "root_1_SMB90XM_"))
    )
    (comp (ref "D7")
      (value "SMB90XM")
      (footprint "DIO-DT-SMD_L3.2-W1.6")
      (libsource (lib "altium-import") (part "root_0_SMB90XM_"))
    )
    (comp (ref "D8") (value "SS34") (footprint "SMA") (libsource (lib "标准封装库") (part "D_TH_FR104")))
    (comp (ref "D9")
      (value "GREEN")
      (footprint "LED0603")
      (description "LED")
      (libsource (lib "小板1_1") (part "GREEN LED"))
    )
    (comp (ref "D10") (value "SS34") (footprint "SMA") (libsource (lib "标准封装库") (part "D_TH_FR104")))
    (comp (ref "D11")
      (value "SMB90XM")
      (footprint "DIO-DT-SMD_L3.2-W1.6")
      (libsource (lib "altium-import") (part "root_0_SMB90XM_"))
    )
    (comp (ref "D12")
      (value "SMB90XM")
      (footprint "DIO-DT-SMD_L3.2-W1.6")
      (libsource (lib "altium-import") (part "root_0_SMB90XM_"))
    )
    (comp (ref "D14")
      (value "SMB90XM")
      (footprint "DIO-DT-SMD_L3.2-W1.6")
      (libsource (lib "altium-import") (part "root_0_SMB90XM_"))
    )
    (comp (ref "D15")
      (value "SMB90XM")
      (footprint "DIO-DT-SMD_L3.2-W1.6")
      (libsource (lib "altium-import") (part "root_0_SMB90XM_"))
    )
    (comp (ref "D16") (value "1N4148WS") (footprint "D123-1") (libsource (lib "标准封装库") (part "D_TH_FR104")))
    (comp (ref "D17") (value "1N4148WS") (footprint "D123-1") (libsource (lib "标准封装库") (part "D_TH_FR104")))
    (comp (ref "D18") (value "1N4148WS") (footprint "D123-1") (libsource (lib "标准封装库") (part "D_TH_FR104")))
    (comp (ref "D19")
      (value "GREEN")
      (footprint "LED0603")
      (description "LED")
      (libsource (lib "小板1_1") (part "GREEN LED"))
    )
    (comp (ref "D20")
      (value "GREEN")
      (footprint "LED0603")
      (description "LED")
      (libsource (lib "小板1_1") (part "GREEN LED"))
    )
    (comp (ref "D21")
      (value "GREEN")
      (footprint "LED0603")
      (description "LED")
      (libsource (lib "小板1_1") (part "GREEN LED"))
    )
    (comp (ref "D22") (value "1N4148WS") (footprint "D123-1") (libsource (lib "标准封装库") (part "D_TH_FR104")))
    (comp (ref "D23") (value "1N4148WS") (footprint "D123-1") (libsource (lib "标准封装库") (part "D_TH_FR104")))
    (comp (ref "D24")
      (value "GREEN")
      (footprint "LED0603")
      (description "LED")
      (libsource (lib "小板1_1") (part "GREEN LED"))
    )
    (comp (ref "D25") (value "1N4148WS") (footprint "D123-1") (libsource (lib "标准封装库") (part "D_TH_FR104")))
    (comp (ref "D26")
      (value "GREEN")
      (footprint "LED0603")
      (description "LED")
      (libsource (lib "小板1_1") (part "GREEN LED"))
    )
    (comp (ref "D28") (value "LED") (footprint "LED0603") (libsource (lib "小板1_1") (part "GREEN LED")))
    (comp (ref "D29")
      (value "SMB90XM")
      (footprint "DIO-DT-SMD_L3.2-W1.6")
      (libsource (lib "altium-import") (part "root_0_SMB90XM_"))
    )
    (comp (ref "D30")
      (value "TPSM712")
      (footprint "SOT-23-3_L2.9-W1.3-P1.90-LS2.4-BR")
      (libsource (lib "altium-import") (part "root_0_TPSM712_"))
    )
    (comp (ref "D31")
      (value "TPSM712")
      (footprint "SOT-23-3_L2.9-W1.3-P1.90-LS2.4-BR")
      (libsource (lib "altium-import") (part "root_0_TPSM712_"))
    )
    (comp (ref "D32")
      (value "TPSM712")
      (footprint "SOT-23-3_L2.9-W1.3-P1.90-LS2.4-BR")
      (libsource (lib "altium-import") (part "root_0_TPSM712_"))
    )
    (comp (ref "D33")
      (value "SMB90XM")
      (footprint "DIO-DT-SMD_L3.2-W1.6")
      (libsource (lib "altium-import") (part "root_0_SMB90XM_"))
    )
    (comp (ref "D34")
      (value "SMB90XM")
      (footprint "DIO-DT-SMD_L3.2-W1.6")
      (libsource (lib "altium-import") (part "root_0_SMB90XM_"))
    )
    (comp (ref "D35")
      (value "SMB90XM")
      (footprint "DIO-DT-SMD_L3.2-W1.6")
      (libsource (lib "altium-import") (part "root_1_SMB90XM_"))
    )
    (comp (ref "D36")
      (value "SMB90XM")
      (footprint "DIO-DT-SMD_L3.2-W1.6")
      (libsource (lib "altium-import") (part "root_1_SMB90XM_"))
    )
    (comp (ref "D40") (value "M7") (footprint "D123-1") (libsource (lib "标准封装库") (part "D_TH_FR104")))
    (comp (ref "D41") (value "LED") (footprint "LED0603") (libsource (lib "小板1_1") (part "GREEN LED")))
    (comp (ref "D46") (value "M7") (footprint "D123-1") (libsource (lib "标准封装库") (part "D_TH_FR104")))
    (comp (ref "D47") (value "M7") (footprint "SMA") (libsource (lib "标准封装库") (part "D_TH_FR104")))
    (comp (ref "D48") (value "LED") (footprint "LED0603") (libsource (lib "小板1_1") (part "GREEN LED")))
    (comp (ref "D54") (value "M7") (footprint "D123-1") (libsource (lib "大板") (part "D_TH_FR104")))
    (comp (ref "D56") (value "M7") (footprint "D123-1") (libsource (lib "标准封装库") (part "D_TH_FR104")))
    (comp (ref "D57") (value "LED") (footprint "LED0603") (libsource (lib "小板1_1") (part "GREEN LED")))
    (comp (ref "D58") (value "LED") (footprint "LED0603") (libsource (lib "小板1_1") (part "GREEN LED")))
    (comp (ref "D61")
      (value "SMAJ15CA")
      (footprint "SMA_L4.3-W2.6-LS5.0-BI")
      (libsource (lib "altium-import") (part "root_0_SMAJ15CA_C223985_"))
    )
    (comp (ref "D63")
      (value "SMAJ15CA")
      (footprint "SMA_L4.3-W2.6-LS5.0-BI")
      (libsource (lib "altium-import") (part "root_0_SMAJ15CA_C223985_"))
    )
    (comp (ref "D64") (value "M7") (footprint "D123-1") (libsource (lib "标准封装库") (part "D_TH_FR104")))
    (comp (ref "D65") (value "LED") (footprint "LED0603") (libsource (lib "小板1_1") (part "GREEN LED")))
    (comp (ref "D66")
      (value "GREEN")
      (footprint "LED0603")
      (description "LED")
      (libsource (lib "小板1_1") (part "GREEN LED"))
    )
    (comp (ref "D67") (value "1N4148WS") (footprint "D123-1") (libsource (lib "标准封装库") (part "D_TH_FR104")))
    (comp (ref "D68")
      (value "GREEN")
      (footprint "LED0603")
      (description "LED")
      (libsource (lib "小板1_1") (part "GREEN LED"))
    )
    (comp (ref "D69") (value "1N4148WS") (footprint "D123-1") (libsource (lib "标准封装库") (part "D_TH_FR104")))
    (comp (ref "D70")
      (value "GREEN")
      (footprint "LED0603")
      (description "LED")
      (libsource (lib "小板1_1") (part "GREEN LED"))
    )
    (comp (ref "D72")
      (value "GREEN")
      (footprint "LED0603")
      (description "LED")
      (libsource (lib "小板1_1") (part "GREEN LED"))
    )
    (comp (ref "D73") (value "1N4148WS") (footprint "D123-1") (libsource (lib "标准封装库") (part "D_TH_FR104")))
    (comp (ref "D74") (value "1N4148WS") (footprint "D123-1") (libsource (lib "标准封装库") (part "D_TH_FR104")))
    (comp (ref "D75") (value "1N4148WS") (footprint "D123-1") (libsource (lib "大板") (part "D_TH_FR104")))
    (comp (ref "D76") (value "LED") (footprint "LED0603") (libsource (lib "小板1_1") (part "GREEN LED")))
    (comp (ref "D77")
      (value "GREEN")
      (footprint "LED0603")
      (description "LED")
      (libsource (lib "小板1_1") (part "GREEN LED"))
    )
    (comp (ref "D78") (value "1N4148WS") (footprint "D123-1") (libsource (lib "标准封装库") (part "D_TH_FR104")))
    (comp (ref "D79") (value "LED") (footprint "LED0603") (libsource (lib "小板1_1") (part "GREEN LED")))
    (comp (ref "D80") (value "1N4148WS") (footprint "D123-1") (libsource (lib "标准封装库") (part "D_TH_FR104")))
    (comp (ref "D81") (value "LED") (footprint "LED0603") (libsource (lib "小板1_1") (part "GREEN LED")))
    (comp (ref "D82") (value "LED") (footprint "LED0603") (libsource (lib "小板1_1") (part "GREEN LED")))
    (comp (ref "D83") (value "1N4148WS") (footprint "D123-1") (libsource (lib "标准封装库") (part "D_TH_FR104")))
    (comp (ref "D84") (value "LED") (footprint "LED0603") (libsource (lib "小板1_1") (part "GREEN LED")))
    (comp (ref "D85") (value "1N4148WS") (footprint "D123-1") (libsource (lib "标准封装库") (part "D_TH_FR104")))
    (comp (ref "D86")
      (value "GREEN")
      (footprint "LED0603")
      (description "LED")
      (libsource (lib "小板1_1") (part "GREEN LED"))
    )
    (comp (ref "D89") (value "M7") (footprint "D123-1") (libsource (lib "标准封装库") (part "D_TH_FR104")))
    (comp (ref "D90") (value "M7") (footprint "D123-1") (libsource (lib "标准封装库") (part "D_TH_FR104")))
    (comp (ref "D91") (value "M7") (footprint "D123-1") (libsource (lib "标准封装库") (part "D_TH_FR104")))
    (comp (ref "D92")
      (value "GREEN")
      (footprint "LED0603")
      (description "LED")
      (libsource (lib "小板1_1") (part "GREEN LED"))
    )
    (comp (ref "D93") (value "M7") (footprint "D123-1") (libsource (lib "标准封装库") (part "D_TH_FR104")))
    (comp (ref "D94") (value "M7") (footprint "D123-1") (libsource (lib "标准封装库") (part "D_TH_FR104")))
    (comp (ref "D95") (value "M7") (footprint "D123-1") (libsource (lib "标准封装库") (part "D_TH_FR104")))
    (comp (ref "D96")
      (value "GREEN")
      (footprint "LED0603")
      (description "LED")
      (libsource (lib "小板1_1") (part "GREEN LED"))
    )
    (comp (ref "D98")
      (value "GREEN")
      (footprint "LED0603")
      (description "LED")
      (libsource (lib "小板1_1") (part "GREEN LED"))
    )
    (comp (ref "D99") (value "BV05C-MS") (footprint "D123") (libsource (lib "小板1") (part "BV05C-MS")))
    (comp (ref "D100") (value "BV05C-MS") (footprint "D123") (libsource (lib "小板1") (part "BV05C-MS")))
    (comp (ref "D101") (value "BV05C-MS") (footprint "D123") (libsource (lib "小板1") (part "BV05C-MS")))
    (comp (ref "D102") (value "M7") (footprint "D123-1") (libsource (lib "标准封装库") (part "D_TH_FR104")))
    (comp (ref "D103") (value "LED") (footprint "LED0603") (libsource (lib "小板1_1") (part "GREEN LED")))
    (comp (ref "D104") (value "M7") (footprint "D123-1") (libsource (lib "标准封装库") (part "D_TH_FR104")))
    (comp (ref "D105") (value "LED") (footprint "LED0603") (libsource (lib "小板1_1") (part "GREEN LED")))
    (comp (ref "D106") (value "M7") (footprint "D123-1") (libsource (lib "标准封装库") (part "D_TH_FR104")))
    (comp (ref "D107") (value "LED") (footprint "LED0603") (libsource (lib "小板1_1") (part "GREEN LED")))
    (comp (ref "D111") (value "1N4148WS") (footprint "D123-1") (libsource (lib "标准封装库") (part "D_TH_FR104")))
    (comp (ref "D180") (value "1N4148WS") (footprint "D123-1") (libsource (lib "标准封装库") (part "D_TH_FR104")))
    (comp (ref "F1")
      (value "Fuse 2")
      (footprint "D2120")
      (description "Fuse")
      (fields (field (name "PUBLISHER") "Altium Limited"))
      (libsource (lib "Miscellaneous Devices") (part "Fuse 2"))
    )
    (comp (ref "F2")
      (value "Fuse 2")
      (footprint "D2120")
      (description "Fuse")
      (fields (field (name "PUBLISHER") "Altium Limited"))
      (libsource (lib "Miscellaneous Devices") (part "Fuse 2"))
    )
    (comp (ref "K1")
      (value "G2R-2-DC5")
      (footprint "K1")
      (libsource (lib "altium-import") (part "root_0_G2R-2-DC5_"))
    )
    (comp (ref "L1")
      (value "ACT45B-510-2P-TL003")
      (footprint "L1206-6")
      (fields (field (name "MANUFACTURER") "TDK"))
      (libsource (lib "大板") (part "ACT45B-510-2P-TL003"))
    )
    (comp (ref "L2")
      (value "100UH")
      (footprint "L-C54")
      (description "Inductor")
      (fields (field (name "PUBLISHER") "Altium Limited"))
      (libsource (lib "*") (part "Inductor"))
    )
    (comp (ref "L3")
      (value "47UH")
      (footprint "LC")
      (description "Inductor")
      (fields (field (name "PUBLISHER") "Altium Limited"))
      (libsource (lib "*") (part "Inductor"))
    )
    (comp (ref "L4")
      (value "ACT45B-510-2P-TL003")
      (footprint "L1206-6")
      (fields (field (name "MANUFACTURER") "TDK"))
      (libsource (lib "大板") (part "ACT45B-510-2P-TL003"))
    )
    (comp (ref "L5")
      (value "ACT45B-510-2P-TL003")
      (footprint "L1206-6")
      (fields (field (name "MANUFACTURER") "TDK"))
      (libsource (lib "大板") (part "ACT45B-510-2P-TL003"))
    )
    (comp (ref "L6")
      (value "ACT45B-510-2P-TL003")
      (footprint "L1206-6")
      (fields (field (name "MANUFACTURER") "TDK"))
      (libsource (lib "大板") (part "ACT45B-510-2P-TL003"))
    )
    (comp (ref "L7")
      (value "ACT45B-510-2P-TL003")
      (footprint "L1206-6")
      (fields (field (name "MANUFACTURER") "TDK"))
      (libsource (lib "大板") (part "ACT45B-510-2P-TL003"))
    )
    (comp (ref "L8")
      (value "ACT45B-510-2P-TL003")
      (footprint "L1206-6")
      (fields (field (name "MANUFACTURER") "TDK"))
      (libsource (lib "大板") (part "ACT45B-510-2P-TL003"))
    )
    (comp (ref "L9")
      (value "BPH853025R5-101T")
      (footprint "L0603")
      (description "标称阻抗@测试频率:100Ω@100MHz;误差:±25%;直流电阻(RDC):1mΩ;")
      (fields (field (name "MANUFACTURER") "TAI-TECH(台庆)") (field (name "TOLERANCE") "±25%"))
      (libsource (lib "altium-import") (part "root_2_BPH853025R5-101T_"))
    )
    (comp (ref "L10")
      (value "BPH853025R5-101T")
      (footprint "L0603")
      (description "标称阻抗@测试频率:100Ω@100MHz;误差:±25%;直流电阻(RDC):1mΩ;")
      (fields (field (name "MANUFACTURER") "TAI-TECH(台庆)") (field (name "TOLERANCE") "±25%"))
      (libsource (lib "altium-import") (part "root_2_BPH853025R5-101T_"))
    )
    (comp (ref "L11")
      (value "ACT45B-510-2P-TL003")
      (footprint "L1206-6")
      (fields (field (name "MANUFACTURER") "TDK"))
      (libsource (lib "大板") (part "ACT45B-510-2P-TL003"))
    )
    (comp (ref "P1")
      (value "Header 3")
      (footprint "254-3P")
      (description "Header, 3-Pin")
      (fields (field (name "PUBLISHER") "Altium Limited"))
      (libsource (lib "大板") (part "Header 3"))
    )
    (comp (ref "P2")
      (value "Header 2")
      (footprint "JPP1")
      (description "Header, 2-Pin")
      (fields (field (name "PUBLISHER") "Altium Limited"))
      (libsource (lib "Miscellaneous Connectors") (part "Header 2"))
    )
    (comp (ref "P4")
      (value "Header 3")
      (footprint "254-3P")
      (description "Header, 3-Pin")
      (fields (field (name "PUBLISHER") "Altium Limited"))
      (libsource (lib "大板") (part "Header 3"))
    )
    (comp (ref "P6")
      (value "Header 2")
      (footprint "JPP1")
      (description "Header, 2-Pin")
      (fields (field (name "PUBLISHER") "Altium Limited"))
      (libsource (lib "Miscellaneous Connectors") (part "Header 2"))
    )
    (comp (ref "P7")
      (value "Header 16")
      (footprint "254-16P")
      (description "Header, 16-Pin")
      (fields (field (name "PUBLISHER") "Altium Limited"))
      (libsource (lib "Miscellaneous Connectors") (part "Header 16"))
    )
    (comp (ref "P8")
      (value "Header 2")
      (footprint "254-2P")
      (description "Header, 2-Pin")
      (fields (field (name "PUBLISHER") "Altium Limited"))
      (libsource (lib "Miscellaneous Connectors") (part "Header 2"))
    )
    (comp (ref "P9")
      (value "Header 2")
      (footprint "254-2P")
      (description "Header, 2-Pin")
      (fields (field (name "PUBLISHER") "Altium Limited"))
      (libsource (lib "Miscellaneous Connectors") (part "Header 2"))
    )
    (comp (ref "P10")
      (value "Header 2")
      (footprint "254-2P")
      (description "Header, 2-Pin")
      (fields (field (name "PUBLISHER") "Altium Limited"))
      (libsource (lib "Miscellaneous Connectors") (part "Header 2"))
    )
    (comp (ref "P11")
      (value "Header 5")
      (footprint "254-5P")
      (description "Header, 5-Pin")
      (fields (field (name "PUBLISHER") "Altium Limited"))
      (libsource (lib "Miscellaneous Connectors") (part "Header 5"))
    )
    (comp (ref "P12")
      (value "Header 3")
      (footprint "254-3P")
      (description "Header, 3-Pin")
      (fields (field (name "PUBLISHER") "Altium Limited"))
      (libsource (lib "") (part "Header 3_1"))
    )
    (comp (ref "P13")
      (value "Header 2")
      (footprint "JPP1")
      (description "Header, 2-Pin")
      (fields (field (name "PUBLISHER") "Altium Limited"))
      (libsource (lib "") (part "Header 2_1"))
    )
    (comp (ref "P14")
      (value "Header 2")
      (footprint "254-2P")
      (description "Header, 2-Pin")
      (fields (field (name "PUBLISHER") "Altium Limited"))
      (libsource (lib "") (part "Header 2_2"))
    )
    (comp (ref "P15")
      (value "Header 4")
      (footprint "254-4P")
      (description "Header, 4-Pin")
      (fields (field (name "PUBLISHER") "Altium Limited"))
      (libsource (lib "") (part "Header 4_1"))
    )
    (comp (ref "P16")
      (value "Header 2")
      (footprint "254-2P")
      (description "Header, 2-Pin")
      (fields (field (name "PUBLISHER") "Altium Limited"))
      (libsource (lib "") (part "Header 2_3"))
    )
    (comp (ref "P17")
      (value "Header 2")
      (footprint "254-2P")
      (description "Header, 2-Pin")
      (fields (field (name "PUBLISHER") "Altium Limited"))
      (libsource (lib "") (part "Header 2_3"))
    )
    (comp (ref "P18")
      (value "Header 2")
      (footprint "254-2P")
      (description "Header, 2-Pin")
      (fields (field (name "PUBLISHER") "Altium Limited"))
      (libsource (lib "") (part "Header 2_3"))
    )
    (comp (ref "P19")
      (value "Header 6")
      (footprint "254-6P")
      (description "Header, 6-Pin")
      (fields (field (name "PUBLISHER") "Altium Limited"))
      (libsource (lib "Miscellaneous Connectors") (part "Header 6"))
    )
    (comp (ref "P20")
      (value "Header 3")
      (footprint "2.54-3P")
      (description "Header, 3-Pin")
      (fields (field (name "PUBLISHER") "Altium Limited"))
      (libsource (lib "") (part "Header 3_1"))
    )
    (comp (ref "P21")
      (value "Header 7")
      (footprint "254-7P")
      (description "Header, 7-Pin")
      (fields (field (name "PUBLISHER") "Altium Limited"))
      (libsource (lib "Miscellaneous Connectors") (part "Header 7"))
    )
    (comp (ref "P22")
      (value "Header 3")
      (footprint "254-3P")
      (description "Header, 3-Pin")
      (fields (field (name "PUBLISHER") "Altium Limited"))
      (libsource (lib "") (part "Header 3_1"))
    )
    (comp (ref "P23")
      (value "Header 5")
      (footprint "254-5P")
      (description "Header, 5-Pin")
      (fields (field (name "PUBLISHER") "Altium Limited"))
      (libsource (lib "Miscellaneous Connectors") (part "Header 5"))
    )
    (comp (ref "P24")
      (value "Header 4H")
      (footprint "254-4P")
      (description "Header, 4-Pin, Right Angle")
      (fields (field (name "PUBLISHER") "Altium Limited"))
      (libsource (lib "Miscellaneous Connectors") (part "Header 4H"))
    )
    (comp (ref "P25")
      (value "Header 3")
      (footprint "254-3P")
      (description "Header, 3-Pin")
      (fields (field (name "PUBLISHER") "Altium Limited"))
      (libsource (lib "大板") (part "Header 3"))
    )
    (comp (ref "P26")
      (value "Header 3")
      (footprint "254-3P")
      (description "Header, 3-Pin")
      (fields (field (name "PUBLISHER") "Altium Limited"))
      (libsource (lib "大板") (part "Header 3"))
    )
    (comp (ref "P27")
      (value "Header 3")
      (footprint "254-3P")
      (description "Header, 3-Pin")
      (fields (field (name "PUBLISHER") "Altium Limited"))
      (libsource (lib "大板") (part "Header 3"))
    )
    (comp (ref "P28")
      (value "Header 3")
      (footprint "254-3P")
      (description "Header, 3-Pin")
      (fields (field (name "PUBLISHER") "Altium Limited"))
      (libsource (lib "大板") (part "Header 3"))
    )
    (comp (ref "P29")
      (value "Header 3")
      (footprint "2.54-3P")
      (description "Header, 3-Pin")
      (fields (field (name "PUBLISHER") "Altium Limited"))
      (libsource (lib "") (part "Header 3_1"))
    )
    (comp (ref "P30")
      (value "Header 4")
      (footprint "USB-A")
      (description "Header, 4-Pin")
      (fields (field (name "PUBLISHER") "Altium Limited"))
      (libsource (lib "Miscellaneous Connectors") (part "Header 4"))
    )
    (comp (ref "P31")
      (value "Header 4")
      (footprint "JP2")
      (description "Header, 4-Pin")
      (fields (field (name "PUBLISHER") "Altium Limited"))
      (libsource (lib "Miscellaneous Connectors") (part "Header 4"))
    )
    (comp (ref "P32")
      (value "Header 7")
      (footprint "254-7P")
      (description "Header, 7-Pin")
      (fields (field (name "PUBLISHER") "Altium Limited"))
      (libsource (lib "") (part "Header 7_1"))
    )
    (comp (ref "P33")
      (value "Header 2")
      (footprint "254-2P")
      (description "Header, 2-Pin")
      (fields (field (name "PUBLISHER") "Altium Limited"))
      (libsource (lib "") (part "Header 2_3"))
    )
    (comp (ref "P34")
      (value "Header 5")
      (footprint "254-5P")
      (description "Header, 5-Pin")
      (fields (field (name "PUBLISHER") "Altium Limited"))
      (libsource (lib "Miscellaneous Connectors") (part "Header 5"))
    )
    (comp (ref "Q2")
      (value "AO3401A")
      (footprint "SOT32-5")
      (fields (field (name "MANUFACTURER PART") "NCE3415"))
      (libsource (lib "NCE34151_NCE3415") (part "NCE3415"))
    )
    (comp (ref "Q3")
      (value "Y1")
      (footprint "SOT32-5")
      (fields (field (name "MANUFACTURER PART") "MMBT8050C(1.5A)"))
      (libsource (lib "大板") (part "MMBT8050C(1.5A)"))
    )
    (comp (ref "Q4")
      (value "S8550")
      (footprint "SOT32-5")
      (fields (field (name "MANUFACTURER") "宏迦橙"))
      (libsource (lib "小板1_1") (part "S8550_C20069126"))
    )
    (comp (ref "Q5")
      (value "S8550")
      (footprint "SOT32-5")
      (fields (field (name "MANUFACTURER") "宏迦橙"))
      (libsource (lib "小板1_1") (part "S8550_C20069126"))
    )
    (comp (ref "Q6")
      (value "AO3401A")
      (footprint "SOT32-5")
      (fields (field (name "MANUFACTURER PART") "NCE3415"))
      (libsource (lib "NCE34151_NCE3415") (part "NCE3415"))
    )
    (comp (ref "Q7")
      (value "Y1")
      (footprint "SOT32-5")
      (fields (field (name "MANUFACTURER PART") "MMBT8050C(1.5A)"))
      (libsource (lib "大板") (part "MMBT8050C(1.5A)"))
    )
    (comp (ref "Q8")
      (value "Y1")
      (footprint "SOT32-5")
      (fields (field (name "MANUFACTURER PART") "MMBT8050C(1.5A)"))
      (libsource (lib "大板") (part "MMBT8050C(1.5A)"))
    )
    (comp (ref "Q9")
      (value "S8550")
      (footprint "SOT32-5")
      (fields (field (name "MANUFACTURER") "宏迦橙"))
      (libsource (lib "小板1_1") (part "S8550_C20069126"))
    )
    (comp (ref "Q10")
      (value "S8550")
      (footprint "SOT32-5")
      (fields (field (name "MANUFACTURER") "宏迦橙"))
      (libsource (lib "小板1_1") (part "S8550_C20069126"))
    )
    (comp (ref "Q11")
      (value "Y1")
      (footprint "SOT32-5")
      (fields (field (name "MANUFACTURER PART") "MMBT8050C(1.5A)"))
      (libsource (lib "大板") (part "MMBT8050C(1.5A)"))
    )
    (comp (ref "Q12")
      (value "Y1")
      (footprint "SOT32-5")
      (fields (field (name "MANUFACTURER PART") "MMBT8050C(1.5A)"))
      (libsource (lib "大板") (part "MMBT8050C(1.5A)"))
    )
    (comp (ref "Q14")
      (value "Y1")
      (footprint "SOT32-5")
      (fields (field (name "MANUFACTURER PART") "MMBT8050C(1.5A)"))
      (libsource (lib "大板") (part "MMBT8050C(1.5A)"))
    )
    (comp (ref "Q20")
      (value "S8050")
      (footprint "SOT-23-3_L2.9-W1.3-P1.90-LS2.3-BR")
      (libsource (lib "altium-import") (part "root_0_S8050_C20069125_"))
    )
    (comp (ref "R1")
      (value "30kΩ")
      (footprint "R0603")
      (description "Resistor")
      (fields (field (name "PUBLISHER") "Altium Limited"))
      (libsource (lib "") (part "Res2_1"))
    )
    (comp (ref "R2")
      (value "10R")
      (footprint "R0603")
      (fields (field (name "RESISTANCE") "10R"))
      (libsource (lib "DDG_Panel") (part "RES"))
    )
    (comp (ref "R8")
      (value "120Ω")
      (footprint "R0805")
      (description "Resistor")
      (fields (field (name "PUBLISHER") "Altium Limited"))
      (libsource (lib "") (part "Res2_3"))
    )
    (comp (ref "R15")
      (value "10kΩ")
      (footprint "R0603")
      (description "Resistor")
      (fields (field (name "PUBLISHER") "Altium Limited"))
      (libsource (lib "") (part "Res2_1"))
    )
    (comp (ref "R20")
      (value "120Ω")
      (footprint "R0805")
      (description "Resistor")
      (fields (field (name "PUBLISHER") "Altium Limited"))
      (libsource (lib "") (part "Res2_2"))
    )
    (comp (ref "R27")
      (value "10kΩ")
      (footprint "R0603")
      (description "Resistor")
      (fields (field (name "PUBLISHER") "Altium Limited"))
      (libsource (lib "") (part "Res2_1"))
    )
    (comp (ref "R28")
      (value "330Ω")
      (footprint "R0603")
      (description "Resistor")
      (fields (field (name "PUBLISHER") "Altium Limited"))
      (libsource (lib "") (part "Res2_1"))
    )
    (comp (ref "R29")
      (value "10kΩ")
      (footprint "R0603")
      (description "Resistor")
      (fields (field (name "PUBLISHER") "Altium Limited"))
      (libsource (lib "") (part "Res2_1"))
    )
    (comp (ref "R30")
      (value "5.1kΩ")
      (footprint "R0603")
      (description "Resistor")
      (fields (field (name "PUBLISHER") "Altium Limited"))
      (libsource (lib "") (part "Res2_1"))
    )
    (comp (ref "R31")
      (value "NC")
      (footprint "R0603")
      (description "Resistor")
      (fields (field (name "PUBLISHER") "Altium Limited"))
      (libsource (lib "") (part "Res2_1"))
    )
    (comp (ref "R32")
      (value "10kΩ")
      (footprint "R0603")
      (description "Resistor")
      (fields (field (name "PUBLISHER") "Altium Limited"))
      (libsource (lib "") (part "Res2_1"))
    )
    (comp (ref "R33")
      (value "5.1kΩ")
      (footprint "R0603")
      (description "Resistor")
      (fields (field (name "PUBLISHER") "Altium Limited"))
      (libsource (lib "") (part "Res2_1"))
    )
    (comp (ref "R34")
      (value "NC")
      (footprint "R0603")
      (description "Resistor")
      (fields (field (name "PUBLISHER") "Altium Limited"))
      (libsource (lib "") (part "Res2_1"))
    )
    (comp (ref "R35")
      (value "NC")
      (footprint "R0603")
      (description "Resistor")
      (fields (field (name "PUBLISHER") "Altium Limited"))
      (libsource (lib "") (part "Res2_1"))
    )
    (comp (ref "R36")
      (value "30kΩ")
      (footprint "R0603")
      (description "Resistor")
      (fields (field (name "PUBLISHER") "Altium Limited"))
      (libsource (lib "") (part "Res2_1"))
    )
    (comp (ref "R37")
      (value "5.1kΩ")
      (footprint "R0603")
      (description "Resistor")
      (fields (field (name "PUBLISHER") "Altium Limited"))
      (libsource (lib "") (part "Res2_1"))
    )
    (comp (ref "R38")
      (value "30kΩ")
      (footprint "R0603")
      (description "Resistor")
      (fields (field (name "PUBLISHER") "Altium Limited"))
      (libsource (lib "") (part "Res2_1"))
    )
    (comp (ref "R39")
      (value "10kΩ")
      (footprint "R0603")
      (description "Resistor")
      (fields (field (name "PUBLISHER") "Altium Limited"))
      (libsource (lib "") (part "Res2_1"))
    )
    (comp (ref "R40")
      (value "330Ω")
      (footprint "R0603")
      (description "Resistor")
      (fields (field (name "PUBLISHER") "Altium Limited"))
      (libsource (lib "") (part "Res2_1"))
    )
    (comp (ref "R41")
      (value "5.1kΩ")
      (footprint "R0603")
      (description "Resistor")
      (fields (field (name "PUBLISHER") "Altium Limited"))
      (libsource (lib "") (part "Res2_1"))
    )
    (comp (ref "R42")
      (value "NC")
      (footprint "R0603")
      (description "Resistor")
      (fields (field (name "PUBLISHER") "Altium Limited"))
      (libsource (lib "") (part "Res2_1"))
    )
    (comp (ref "R43")
      (value "10kΩ")
      (footprint "R0603")
      (description "Resistor")
      (fields (field (name "PUBLISHER") "Altium Limited"))
      (libsource (lib "大板") (part "Res2"))
    )
    (comp (ref "R44")
      (value "10kΩ")
      (footprint "R0603")
      (description "Resistor")
      (fields (field (name "PUBLISHER") "Altium Limited"))
      (libsource (lib "") (part "Res2_1"))
    )
    (comp (ref "R45")
      (value "NC")
      (footprint "R0603")
      (description "Resistor")
      (fields (field (name "PUBLISHER") "Altium Limited"))
      (libsource (lib "") (part "Res2_1"))
    )
    (comp (ref "R46")
      (value "5.1kΩ")
      (footprint "R0603")
      (description "Resistor")
      (fields (field (name "PUBLISHER") "Altium Limited"))
      (libsource (lib "大板") (part "Res2"))
    )
    (comp (ref "R47")
      (value "30kΩ")
      (footprint "R0603")
      (description "Resistor")
      (fields (field (name "PUBLISHER") "Altium Limited"))
      (libsource (lib "") (part "Res2_1"))
    )
    (comp (ref "R48")
      (value "NC")
      (footprint "R0603")
      (description "Resistor")
      (fields (field (name "PUBLISHER") "Altium Limited"))
      (libsource (lib "大板") (part "Res2"))
    )
    (comp (ref "R49")
      (value "5.1kΩ")
      (footprint "R0603")
      (description "Resistor")
      (fields (field (name "PUBLISHER") "Altium Limited"))
      (libsource (lib "") (part "Res2_1"))
    )
    (comp (ref "R51")
      (value "10kΩ")
      (footprint "R0603")
      (description "Resistor")
      (fields (field (name "PUBLISHER") "Altium Limited"))
      (libsource (lib "大板") (part "Res2"))
    )
    (comp (ref "R52")
      (value "10kΩ")
      (footprint "R0603")
      (description "Resistor")
      (fields (field (name "PUBLISHER") "Altium Limited"))
      (libsource (lib "大板") (part "Res2"))
    )
    (comp (ref "R53")
      (value "20kΩ")
      (footprint "R0603")
      (description "Resistor")
      (fields (field (name "PUBLISHER") "Altium Limited"))
      (libsource (lib "") (part "Res2_3"))
    )
    (comp (ref "R54")
      (value "10kΩ")
      (footprint "R0603")
      (description "Resistor")
      (fields (field (name "PUBLISHER") "Altium Limited"))
      (libsource (lib "") (part "Res2_1"))
    )
    (comp (ref "R55")
      (value "20kΩ")
      (footprint "R0603")
      (description "Resistor")
      (fields (field (name "PUBLISHER") "Altium Limited"))
      (libsource (lib "") (part "Res2_1"))
    )
    (comp (ref "R56")
      (value "30kΩ")
      (footprint "R0603")
      (description "Resistor")
      (fields (field (name "PUBLISHER") "Altium Limited"))
      (libsource (lib "") (part "Res2_1"))
    )
    (comp (ref "R58")
      (value "5.1kΩ")
      (footprint "R0603")
      (description "Resistor")
      (fields (field (name "PUBLISHER") "Altium Limited"))
      (libsource (lib "大板") (part "Res2"))
    )
    (comp (ref "R62")
      (value "120Ω")
      (footprint "R0805")
      (description "Resistor")
      (fields (field (name "PUBLISHER") "Altium Limited"))
      (libsource (lib "") (part "Res2_3"))
    )
    (comp (ref "R67")
      (value "5.1kΩ")
      (footprint "R0603")
      (description "Resistor")
      (fields (field (name "PUBLISHER") "Altium Limited"))
      (libsource (lib "") (part "Res2_1"))
    )
    (comp (ref "R71")
      (value "330Ω")
      (footprint "R0603")
      (description "Resistor")
      (fields (field (name "PUBLISHER") "Altium Limited"))
      (libsource (lib "") (part "Res2_1"))
    )
    (comp (ref "R74")
      (value "15P101R")
      (footprint "R0603")
      (description "Resistor")
      (fields (field (name "PUBLISHER") "Altium Limited"))
      (libsource (lib "") (part "Res2_1"))
    )
    (comp (ref "R75")
      (value "10kΩ")
      (footprint "R0603")
      (description "Resistor")
      (fields (field (name "PUBLISHER") "Altium Limited"))
      (libsource (lib "") (part "Res2_1"))
    )
    (comp (ref "R76")
      (value "5.1kΩ")
      (footprint "R0603")
      (description "Resistor")
      (fields (field (name "PUBLISHER") "Altium Limited"))
      (libsource (lib "") (part "Res2_1"))
    )
    (comp (ref "R77")
      (value "20kΩ")
      (footprint "R0603")
      (description "Resistor")
      (fields (field (name "PUBLISHER") "Altium Limited"))
      (libsource (lib "") (part "Res2_1"))
    )
    (comp (ref "R78")
      (value "20kΩ")
      (footprint "R0603")
      (description "Resistor")
      (fields (field (name "PUBLISHER") "Altium Limited"))
      (libsource (lib "") (part "Res2_1"))
    )
    (comp (ref "R81")
      (value "120Ω")
      (footprint "R0805")
      (description "Resistor")
      (fields (field (name "PUBLISHER") "Altium Limited"))
      (libsource (lib "") (part "Res2_3"))
    )
    (comp (ref "R82")
      (value "120Ω")
      (footprint "R0805")
      (description "Resistor")
      (fields (field (name "PUBLISHER") "Altium Limited"))
      (libsource (lib "") (part "Res2_2"))
    )
    (comp (ref "R83")
      (value "30kΩ")
      (footprint "R0603")
      (description "Resistor")
      (fields (field (name "PUBLISHER") "Altium Limited"))
      (libsource (lib "") (part "Res2_1"))
    )
    (comp (ref "R86")
      (value "330Ω")
      (footprint "R0603")
      (description "Resistor")
      (fields (field (name "PUBLISHER") "Altium Limited"))
      (libsource (lib "") (part "Res2_1"))
    )
    (comp (ref "R88")
      (value "NC")
      (footprint "R0603")
      (description "Resistor")
      (fields (field (name "PUBLISHER") "Altium Limited"))
      (libsource (lib "") (part "Res2_1"))
    )
    (comp (ref "R89")
      (value "10kΩ")
      (footprint "R0603")
      (description "Resistor")
      (fields (field (name "PUBLISHER") "Altium Limited"))
      (libsource (lib "") (part "Res2_1"))
    )
    (comp (ref "R90")
      (value "20kΩ")
      (footprint "R0603")
      (description "Resistor")
      (fields (field (name "PUBLISHER") "Altium Limited"))
      (libsource (lib "大板") (part "Res2"))
    )
    (comp (ref "R92")
      (value "5.1kΩ")
      (footprint "R0603")
      (description "Resistor")
      (fields (field (name "PUBLISHER") "Altium Limited"))
      (libsource (lib "") (part "Res2_1"))
    )
    (comp (ref "R93")
      (value "10kΩ")
      (footprint "R0603")
      (description "Resistor")
      (fields (field (name "PUBLISHER") "Altium Limited"))
      (libsource (lib "") (part "Res2_1"))
    )
    (comp (ref "R95")
      (value "30kΩ")
      (footprint "R0603")
      (description "Resistor")
      (fields (field (name "PUBLISHER") "Altium Limited"))
      (libsource (lib "") (part "Res2_1"))
    )
    (comp (ref "R97")
      (value "12Ω")
      (footprint "R0805")
      (description "Resistor")
      (fields (field (name "PUBLISHER") "Altium Limited"))
      (libsource (lib "大板") (part "Res2"))
    )
    (comp (ref "R98")
      (value "12Ω")
      (footprint "R0805")
      (description "Resistor")
      (fields (field (name "PUBLISHER") "Altium Limited"))
      (libsource (lib "大板") (part "Res2"))
    )
    (comp (ref "R99")
      (value "330Ω")
      (footprint "R0603")
      (description "Resistor")
      (fields (field (name "PUBLISHER") "Altium Limited"))
      (libsource (lib "") (part "Res2_1"))
    )
    (comp (ref "R100")
      (value "10kΩ")
      (footprint "R0603")
      (description "Resistor")
      (fields (field (name "PUBLISHER") "Altium Limited"))
      (libsource (lib "") (part "Res2_3"))
    )
    (comp (ref "R101")
      (value "10kΩ")
      (footprint "R0603")
      (description "Resistor")
      (fields (field (name "PUBLISHER") "Altium Limited"))
      (libsource (lib "") (part "Res2_1"))
    )
    (comp (ref "R102")
      (value "NC")
      (footprint "R0603")
      (description "Resistor")
      (fields (field (name "PUBLISHER") "Altium Limited"))
      (libsource (lib "") (part "Res2_1"))
    )
    (comp (ref "R103")
      (value "10kΩ")
      (footprint "R0603")
      (description "Resistor")
      (fields (field (name "PUBLISHER") "Altium Limited"))
      (libsource (lib "") (part "Res2_1"))
    )
    (comp (ref "R104")
      (value "5.1kΩ")
      (footprint "R0603")
      (description "Resistor")
      (fields (field (name "PUBLISHER") "Altium Limited"))
      (libsource (lib "") (part "Res2_1"))
    )
    (comp (ref "R105")
      (value "5.1kΩ")
      (footprint "R0603")
      (description "Resistor")
      (fields (field (name "PUBLISHER") "Altium Limited"))
      (libsource (lib "") (part "Res2_1"))
    )
    (comp (ref "R106")
      (value "330Ω")
      (footprint "R0603")
      (description "Resistor")
      (fields (field (name "PUBLISHER") "Altium Limited"))
      (libsource (lib "") (part "Res2_1"))
    )
    (comp (ref "R107")
      (value "NC")
      (footprint "R0603")
      (description "Resistor")
      (fields (field (name "PUBLISHER") "Altium Limited"))
      (libsource (lib "") (part "Res2_1"))
    )
    (comp (ref "R108")
      (value "5.1kΩ")
      (footprint "R0603")
      (description "Resistor")
      (fields (field (name "PUBLISHER") "Altium Limited"))
      (libsource (lib "") (part "Res2_1"))
    )
    (comp (ref "R109")
      (value "330Ω")
      (footprint "R0603")
      (description "Resistor")
      (fields (field (name "PUBLISHER") "Altium Limited"))
      (libsource (lib "") (part "Res2_1"))
    )
    (comp (ref "R110")
      (value "5.1kΩ")
      (footprint "R0603")
      (description "Resistor")
      (fields (field (name "PUBLISHER") "Altium Limited"))
      (libsource (lib "") (part "Res2_1"))
    )
    (comp (ref "R111")
      (value "NC")
      (footprint "R0603")
      (description "Resistor")
      (fields (field (name "PUBLISHER") "Altium Limited"))
      (libsource (lib "") (part "Res2_1"))
    )
    (comp (ref "R112")
      (value "5.1kΩ")
      (footprint "R0603")
      (description "Resistor")
      (fields (field (name "PUBLISHER") "Altium Limited"))
      (libsource (lib "") (part "Res2_1"))
    )
    (comp (ref "R113")
      (value "10kΩ")
      (footprint "R0603")
      (description "Resistor")
      (fields (field (name "PUBLISHER") "Altium Limited"))
      (libsource (lib "") (part "Res2_1"))
    )
    (comp (ref "R114")
      (value "NC")
      (footprint "R0603")
      (description "Resistor")
      (fields (field (name "PUBLISHER") "Altium Limited"))
      (libsource (lib "") (part "Res2_1"))
    )
    (comp (ref "R115")
      (value "5.1kΩ")
      (footprint "R0603")
      (description "Resistor")
      (fields (field (name "PUBLISHER") "Altium Limited"))
      (libsource (lib "") (part "Res2_1"))
    )
    (comp (ref "R116")
      (value "30kΩ")
      (footprint "R0603")
      (description "Resistor")
      (fields (field (name "PUBLISHER") "Altium Limited"))
      (libsource (lib "") (part "Res2_1"))
    )
    (comp (ref "R117")
      (value "10kΩ")
      (footprint "R0603")
      (description "Resistor")
      (fields (field (name "PUBLISHER") "Altium Limited"))
      (libsource (lib "") (part "Res2_1"))
    )
    (comp (ref "R118")
      (value "NC")
      (footprint "R0603")
      (description "Resistor")
      (fields (field (name "PUBLISHER") "Altium Limited"))
      (libsource (lib "") (part "Res2_1"))
    )
    (comp (ref "R119")
      (value "5.1kΩ")
      (footprint "R0603")
      (description "Resistor")
      (fields (field (name "PUBLISHER") "Altium Limited"))
      (libsource (lib "") (part "Res2_1"))
    )
    (comp (ref "R120")
      (value "30kΩ")
      (footprint "R0603")
      (description "Resistor")
      (fields (field (name "PUBLISHER") "Altium Limited"))
      (libsource (lib "") (part "Res2_1"))
    )
    (comp (ref "R121")
      (value "10kΩ")
      (footprint "R0603")
      (description "Resistor")
      (fields (field (name "PUBLISHER") "Altium Limited"))
      (libsource (lib "") (part "Res2_1"))
    )
    (comp (ref "R122")
      (value "330Ω")
      (footprint "R0805")
      (description "Resistor")
      (fields (field (name "PUBLISHER") "Altium Limited"))
      (libsource (lib "大板") (part "Res2"))
    )
    (comp (ref "R123")
      (value "5.1kΩ")
      (footprint "R0603")
      (description "Resistor")
      (fields (field (name "PUBLISHER") "Altium Limited"))
      (libsource (lib "") (part "Res2_1"))
    )
    (comp (ref "R124")
      (value "NC")
      (footprint "R0603")
      (description "Resistor")
      (fields (field (name "PUBLISHER") "Altium Limited"))
      (libsource (lib "") (part "Res2_1"))
    )
    (comp (ref "R125")
      (value "10kΩ")
      (footprint "R0603")
      (description "Resistor")
      (fields (field (name "PUBLISHER") "Altium Limited"))
      (libsource (lib "") (part "Res2_1"))
    )
    (comp (ref "R126")
      (value "NC")
      (footprint "R0603")
      (description "Resistor")
      (fields (field (name "PUBLISHER") "Altium Limited"))
      (libsource (lib "") (part "Res2_1"))
    )
    (comp (ref "R127")
      (value "30kΩ")
      (footprint "R0603")
      (description "Resistor")
      (fields (field (name "PUBLISHER") "Altium Limited"))
      (libsource (lib "") (part "Res2_1"))
    )
    (comp (ref "R128")
      (value "5.1kΩ")
      (footprint "R0603")
      (description "Resistor")
      (fields (field (name "PUBLISHER") "Altium Limited"))
      (libsource (lib "") (part "Res2_1"))
    )
    (comp (ref "R129")
      (value "10kΩ")
      (footprint "R0603")
      (description "Resistor")
      (fields (field (name "PUBLISHER") "Altium Limited"))
      (libsource (lib "") (part "Res2_1"))
    )
    (comp (ref "R130")
      (value "5.1kΩ")
      (footprint "R0603")
      (description "Resistor")
      (fields (field (name "PUBLISHER") "Altium Limited"))
      (libsource (lib "") (part "Res2_1"))
    )
    (comp (ref "R131")
      (value "330Ω")
      (footprint "R0805")
      (description "Resistor")
      (fields (field (name "PUBLISHER") "Altium Limited"))
      (libsource (lib "大板") (part "Res2"))
    )
    (comp (ref "R132")
      (value "NC")
      (footprint "R0603")
      (description "Resistor")
      (fields (field (name "PUBLISHER") "Altium Limited"))
      (libsource (lib "") (part "Res2_1"))
    )
    (comp (ref "R133")
      (value "NC")
      (footprint "R0603")
      (description "Resistor")
      (fields (field (name "PUBLISHER") "Altium Limited"))
      (libsource (lib "") (part "Res2_1"))
    )
    (comp (ref "R134")
      (value "30kΩ")
      (footprint "R0603")
      (description "Resistor")
      (fields (field (name "PUBLISHER") "Altium Limited"))
      (libsource (lib "") (part "Res2_1"))
    )
    (comp (ref "R135")
      (value "10kΩ")
      (footprint "R0603")
      (description "Resistor")
      (fields (field (name "PUBLISHER") "Altium Limited"))
      (libsource (lib "") (part "Res2_1"))
    )
    (comp (ref "R136")
      (value "5.1kΩ")
      (footprint "R0603")
      (description "Resistor")
      (fields (field (name "PUBLISHER") "Altium Limited"))
      (libsource (lib "") (part "Res2_1"))
    )
    (comp (ref "R137")
      (value "20kΩ")
      (footprint "R0603")
      (description "Resistor")
      (fields (field (name "PUBLISHER") "Altium Limited"))
      (libsource (lib "") (part "Res2_1"))
    )
    (comp (ref "R138")
      (value "10kΩ")
      (footprint "R0603")
      (description "Resistor")
      (fields (field (name "PUBLISHER") "Altium Limited"))
      (libsource (lib "") (part "Res2_1"))
    )
    (comp (ref "R139")
      (value "5.1kΩ")
      (footprint "R0603")
      (description "Resistor")
      (fields (field (name "PUBLISHER") "Altium Limited"))
      (libsource (lib "") (part "Res2_1"))
    )
    (comp (ref "R140")
      (value "NC")
      (footprint "R0603")
      (description "Resistor")
      (fields (field (name "PUBLISHER") "Altium Limited"))
      (libsource (lib "") (part "Res2_1"))
    )
    (comp (ref "R141")
      (value "30kΩ")
      (footprint "R0603")
      (description "Resistor")
      (fields (field (name "PUBLISHER") "Altium Limited"))
      (libsource (lib "") (part "Res2_1"))
    )
    (comp (ref "R142")
      (value "20kΩ")
      (footprint "R0603")
      (description "Resistor")
      (fields (field (name "PUBLISHER") "Altium Limited"))
      (libsource (lib "大板") (part "Res2"))
    )
    (comp (ref "R143")
      (value "20kΩ")
      (footprint "R0603")
      (description "Resistor")
      (fields (field (name "PUBLISHER") "Altium Limited"))
      (libsource (lib "") (part "Res2_1"))
    )
    (comp (ref "R144")
      (value "20kΩ")
      (footprint "R0603")
      (description "Resistor")
      (fields (field (name "PUBLISHER") "Altium Limited"))
      (libsource (lib "大板") (part "Res2"))
    )
    (comp (ref "R145")
      (value "10kΩ")
      (footprint "R0603")
      (description "Resistor")
      (fields (field (name "PUBLISHER") "Altium Limited"))
      (libsource (lib "") (part "Res2_1"))
    )
    (comp (ref "R146")
      (value "120Ω")
      (footprint "R0603")
      (description "Resistor")
      (fields (field (name "PUBLISHER") "Altium Limited"))
      (libsource (lib "") (part "Res2_1"))
    )
    (comp (ref "R147")
      (value "10kΩ")
      (footprint "R0603")
      (description "Resistor")
      (fields (field (name "PUBLISHER") "Altium Limited"))
      (libsource (lib "") (part "Res2_1"))
    )
    (comp (ref "R148")
      (value "NC")
      (footprint "R0603")
      (description "Resistor")
      (fields (field (name "PUBLISHER") "Altium Limited"))
      (libsource (lib "") (part "Res2_1"))
    )
    (comp (ref "R149")
      (value "10kΩ")
      (footprint "R0603")
      (description "Resistor")
      (fields (field (name "PUBLISHER") "Altium Limited"))
      (libsource (lib "") (part "Res2_1"))
    )
    (comp (ref "R150")
      (value "10kΩ")
      (footprint "R0603")
      (description "Resistor")
      (fields (field (name "PUBLISHER") "Altium Limited"))
      (libsource (lib "") (part "Res2_1"))
    )
    (comp (ref "R151")
      (value "20kΩ")
      (footprint "R0603")
      (description "Resistor")
      (fields (field (name "PUBLISHER") "Altium Limited"))
      (libsource (lib "") (part "Res2_1"))
    )
    (comp (ref "R152")
      (value "120Ω")
      (footprint "R0603")
      (description "Resistor")
      (fields (field (name "PUBLISHER") "Altium Limited"))
      (libsource (lib "大板") (part "Res2"))
    )
    (comp (ref "R153")
      (value "10kΩ")
      (footprint "R0603")
      (description "Resistor")
      (fields (field (name "PUBLISHER") "Altium Limited"))
      (libsource (lib "") (part "Res2_1"))
    )
    (comp (ref "R154")
      (value "10kΩ")
      (footprint "R0603")
      (description "Resistor")
      (fields (field (name "PUBLISHER") "Altium Limited"))
      (libsource (lib "") (part "Res2_1"))
    )
    (comp (ref "R156")
      (value "10kΩ")
      (footprint "R0603")
      (description "Resistor")
      (fields (field (name "PUBLISHER") "Altium Limited"))
      (libsource (lib "") (part "Res2_1"))
    )
    (comp (ref "R157")
      (value "20kΩ")
      (footprint "R0603")
      (description "Resistor")
      (fields (field (name "PUBLISHER") "Altium Limited"))
      (libsource (lib "") (part "Res2_3"))
    )
    (comp (ref "R158")
      (value "20kΩ")
      (footprint "R0603")
      (description "Resistor")
      (fields (field (name "PUBLISHER") "Altium Limited"))
      (libsource (lib "") (part "Res2_3"))
    )
    (comp (ref "R160")
      (value "20kΩ")
      (footprint "R0603")
      (description "Resistor")
      (fields (field (name "PUBLISHER") "Altium Limited"))
      (libsource (lib "") (part "Res2_3"))
    )
    (comp (ref "R161")
      (value "20kΩ")
      (footprint "R0603")
      (description "Resistor")
      (fields (field (name "PUBLISHER") "Altium Limited"))
      (libsource (lib "") (part "Res2_3"))
    )
    (comp (ref "R162")
      (value "10kΩ")
      (footprint "R0603")
      (description "Resistor")
      (fields (field (name "PUBLISHER") "Altium Limited"))
      (libsource (lib "") (part "Res2_1"))
    )
    (comp (ref "R163")
      (value "20kΩ")
      (footprint "R0603")
      (description "Resistor")
      (fields (field (name "PUBLISHER") "Altium Limited"))
      (libsource (lib "") (part "Res2_3"))
    )
    (comp (ref "R164")
      (value "20kΩ")
      (footprint "R0603")
      (description "Resistor")
      (fields (field (name "PUBLISHER") "Altium Limited"))
      (libsource (lib "") (part "Res2_2"))
    )
    (comp (ref "R165")
      (value "20kΩ")
      (footprint "R0603")
      (description "Resistor")
      (fields (field (name "PUBLISHER") "Altium Limited"))
      (libsource (lib "") (part "Res2_1"))
    )
    (comp (ref "R166")
      (value "510Ω")
      (footprint "R0603")
      (description "Resistor")
      (fields (field (name "PUBLISHER") "Altium Limited"))
      (libsource (lib "") (part "Res2_1"))
    )
    (comp (ref "R167")
      (value "NC")
      (footprint "R0603")
      (description "Resistor")
      (fields (field (name "PUBLISHER") "Altium Limited"))
      (libsource (lib "") (part "Res2_1"))
    )
    (comp (ref "R168")
      (value "20kΩ")
      (footprint "R0603")
      (description "Resistor")
      (fields (field (name "PUBLISHER") "Altium Limited"))
      (libsource (lib "") (part "Res2_1"))
    )
    (comp (ref "R169")
      (value "10kΩ")
      (footprint "R0603")
      (description "Resistor")
      (fields (field (name "PUBLISHER") "Altium Limited"))
      (libsource (lib "") (part "Res2_1"))
    )
    (comp (ref "R170")
      (value "5.1kΩ")
      (footprint "R0603")
      (description "Resistor")
      (fields (field (name "PUBLISHER") "Altium Limited"))
      (libsource (lib "") (part "Res2_1"))
    )
    (comp (ref "R171")
      (value "20kΩ")
      (footprint "R0603")
      (description "Resistor")
      (fields (field (name "PUBLISHER") "Altium Limited"))
      (libsource (lib "") (part "Res2_1"))
    )
    (comp (ref "R172")
      (value "510Ω")
      (footprint "R0603")
      (description "Resistor")
      (fields (field (name "PUBLISHER") "Altium Limited"))
      (libsource (lib "") (part "Res2_1"))
    )
    (comp (ref "R173")
      (value "NC")
      (footprint "R0603")
      (description "Resistor")
      (fields (field (name "PUBLISHER") "Altium Limited"))
      (libsource (lib "") (part "Res2_1"))
    )
    (comp (ref "R174")
      (value "20kΩ")
      (footprint "R0603")
      (description "Resistor")
      (fields (field (name "PUBLISHER") "Altium Limited"))
      (libsource (lib "") (part "Res2_1"))
    )
    (comp (ref "R175")
      (value "10kΩ")
      (footprint "R0603")
      (description "Resistor")
      (fields (field (name "PUBLISHER") "Altium Limited"))
      (libsource (lib "") (part "Res2_1"))
    )
    (comp (ref "R176")
      (value "5.1kΩ")
      (footprint "R0603")
      (description "Resistor")
      (fields (field (name "PUBLISHER") "Altium Limited"))
      (libsource (lib "") (part "Res2_1"))
    )
    (comp (ref "R179")
      (value "10kΩ")
      (footprint "R0603")
      (description "Resistor")
      (fields (field (name "PUBLISHER") "Altium Limited"))
      (libsource (lib "大板") (part "Res2"))
    )
    (comp (ref "R181")
      (value "10kΩ")
      (footprint "R0603")
      (description "Resistor")
      (fields (field (name "PUBLISHER") "Altium Limited"))
      (libsource (lib "大板") (part "Res2"))
    )
    (comp (ref "R182")
      (value "10kΩ")
      (footprint "R0603")
      (description "Resistor")
      (fields (field (name "PUBLISHER") "Altium Limited"))
      (libsource (lib "") (part "Res2_2"))
    )
    (comp (ref "R184")
      (value "0Ω")
      (footprint "R0603")
      (description "Resistor")
      (fields (field (name "PUBLISHER") "Altium Limited"))
      (libsource (lib "大板") (part "Res2"))
    )
    (comp (ref "R187")
      (value "220Ω")
      (footprint "R0603")
      (description "Resistor")
      (fields (field (name "PUBLISHER") "Altium Limited"))
      (libsource (lib "大板") (part "Res2"))
    )
    (comp (ref "R188")
      (value "220Ω")
      (footprint "R0603")
      (description "Resistor")
      (fields (field (name "PUBLISHER") "Altium Limited"))
      (libsource (lib "大板") (part "Res2"))
    )
    (comp (ref "R189")
      (value "10kΩ")
      (footprint "R0603")
      (description "Resistor")
      (fields (field (name "PUBLISHER") "Altium Limited"))
      (libsource (lib "") (part "Res2_1"))
    )
    (comp (ref "R190")
      (value "10kΩ")
      (footprint "R0603")
      (description "Resistor")
      (fields (field (name "PUBLISHER") "Altium Limited"))
      (libsource (lib "") (part "Res2_1"))
    )
    (comp (ref "R191")
      (value "5.1kΩ")
      (footprint "R0603")
      (description "Resistor")
      (fields (field (name "PUBLISHER") "Altium Limited"))
      (libsource (lib "大板") (part "Res2"))
    )
    (comp (ref "R192")
      (value "10kΩ")
      (footprint "R0603")
      (description "Resistor")
      (fields (field (name "PUBLISHER") "Altium Limited"))
      (libsource (lib "大板") (part "Res2"))
    )
    (comp (ref "R193")
      (value "10kΩ")
      (footprint "R0603")
      (description "Resistor")
      (fields (field (name "PUBLISHER") "Altium Limited"))
      (libsource (lib "大板") (part "Res2"))
    )
    (comp (ref "R194")
      (value "10kΩ")
      (footprint "R0603")
      (description "Semiconductor Resistor")
      (fields (field (name "PUBLISHER") "Altium Limited"))
      (libsource (lib "小板1") (part "Res Semi"))
    )
    (comp (ref "R195")
      (value "1.8kΩ")
      (footprint "R0603")
      (description "Semiconductor Resistor")
      (fields (field (name "PUBLISHER") "Altium Limited"))
      (libsource (lib "小板1") (part "Res Semi"))
    )
    (comp (ref "R197")
      (value "330Ω")
      (footprint "R0603")
      (description "Resistor")
      (fields (field (name "PUBLISHER") "Altium Limited"))
      (libsource (lib "") (part "Res2_1"))
    )
    (comp (ref "R198")
      (value "10kΩ")
      (footprint "R0603")
      (description "Resistor")
      (fields (field (name "PUBLISHER") "Altium Limited"))
      (libsource (lib "") (part "Res2_1"))
    )
    (comp (ref "R199")
      (value "5.1kΩ")
      (footprint "R0603")
      (description "Resistor")
      (fields (field (name "PUBLISHER") "Altium Limited"))
      (libsource (lib "") (part "Res2_1"))
    )
    (comp (ref "R200")
      (value "5.1kΩ")
      (footprint "R0603")
      (description "Resistor")
      (fields (field (name "PUBLISHER") "Altium Limited"))
      (libsource (lib "") (part "Res2_1"))
    )
    (comp (ref "R201")
      (value "5.1kΩ")
      (footprint "R0603")
      (description "Resistor")
      (fields (field (name "PUBLISHER") "Altium Limited"))
      (libsource (lib "") (part "Res2_1"))
    )
    (comp (ref "R202")
      (value "510Ω")
      (footprint "R0603")
      (description "Resistor")
      (fields (field (name "PUBLISHER") "Altium Limited"))
      (libsource (lib "") (part "Res2_1"))
    )
    (comp (ref "R203")
      (value "5.1kΩ")
      (footprint "R0603")
      (description "Resistor")
      (fields (field (name "PUBLISHER") "Altium Limited"))
      (libsource (lib "") (part "Res2_1"))
    )
    (comp (ref "R204")
      (value "NC")
      (footprint "R0603")
      (description "Resistor")
      (fields (field (name "PUBLISHER") "Altium Limited"))
      (libsource (lib "") (part "Res2_1"))
    )
    (comp (ref "R205")
      (value "5.1kΩ")
      (footprint "R0603")
      (description "Resistor")
      (fields (field (name "PUBLISHER") "Altium Limited"))
      (libsource (lib "") (part "Res2_1"))
    )
    (comp (ref "R206")
      (value "510Ω")
      (footprint "R0603")
      (description "Resistor")
      (fields (field (name "PUBLISHER") "Altium Limited"))
      (libsource (lib "") (part "Res2_1"))
    )
    (comp (ref "R207")
      (value "5.1kΩ")
      (footprint "R0603")
      (description "Resistor")
      (fields (field (name "PUBLISHER") "Altium Limited"))
      (libsource (lib "") (part "Res2_1"))
    )
    (comp (ref "R208")
      (value "NC")
      (footprint "R0603")
      (description "Resistor")
      (fields (field (name "PUBLISHER") "Altium Limited"))
      (libsource (lib "") (part "Res2_1"))
    )
    (comp (ref "R209")
      (value "5.1k")
      (footprint "R0603")
      (description "Resistor")
      (fields (field (name "PUBLISHER") "Altium Limited"))
      (libsource (lib "") (part "Res2_1"))
    )
    (comp (ref "T1")
      (value "HFD4/24")
      (footprint "JP1")
      (description "Header, 6-Pin, Dual row")
      (fields (field (name "PUBLISHER") "Altium Limited"))
      (libsource (lib "小板1_1") (part "Header 6X2"))
    )
    (comp (ref "TP2")
      (value "RH-5001")
      (footprint "TP")
      (fields (field (name "MANUFACTURER") "荣和"))
      (libsource (lib "altium-import") (part "root_1_RH-5001_"))
    )
    (comp (ref "TP3")
      (value "RH-5001")
      (footprint "TP")
      (fields (field (name "MANUFACTURER") "荣和"))
      (libsource (lib "altium-import") (part "root_1_RH-5001_"))
    )
    (comp (ref "TP4")
      (value "RH-5001")
      (footprint "TP")
      (fields (field (name "MANUFACTURER") "荣和"))
      (libsource (lib "altium-import") (part "root_0_RH-5001_"))
    )
    (comp (ref "TP5")
      (value "RH-5001")
      (footprint "TP")
      (fields (field (name "MANUFACTURER") "荣和"))
      (libsource (lib "altium-import") (part "root_1_RH-5001_"))
    )
    (comp (ref "TVS2")
      (value "PESD1CAN")
      (footprint "SOT-23-3_L2.9-W1.3-P1.90-LS2.3-BR")
      (libsource (lib "*") (part "CAN_TVS_NUP2015L"))
    )
    (comp (ref "TVS3")
      (value "PESD1CAN")
      (footprint "SOT-23-3_L2.9-W1.3-P1.90-LS2.3-BR")
      (libsource (lib "*") (part "CAN_TVS_NUP2015L"))
    )
    (comp (ref "U1")
      (value "RSM3422")
      (footprint "DIP-12_L19.5-W16.5-P2.54-LS12.7-BL")
      (libsource (lib "altium-import") (part "root_0_RSM3422_C7425471_"))
    )
    (comp (ref "U2")
      (value "CTM1051KAT")
      (footprint "COMM-TH_CTM1051KAT")
      (fields (field (name "MANUFACTURER") "VISOM"))
      (libsource (lib "altium-import") (part "root_0_CTM1051KAT_"))
    )
    (comp (ref "U3")
      (value "LM2576HVR-12")
      (footprint "TO5")
      (fields (field (name "MANUFACTURER") "HTC") (field (name "MANUFACTURER PART") "LM2576HVR-5.0"))
      (libsource (lib "altium-import") (part "root_0_LM2576HVR-5.0_"))
    )
    (comp (ref "U4")
      (value "LM2674MX-5.0/NOPB")
      (footprint "SOP-8")
      (fields (field (name "MANUFACTURER PART") "LM2672M-ADJ/NOPB"))
      (libsource (lib "altium-import") (part "root_2_LM2672M-ADJ/NOPB_"))
    )
    (comp (ref "U5")
      (value "RSM3422")
      (footprint "DIP-12_L19.5-W16.5-P2.54-LS12.7-BL")
      (libsource (lib "altium-import") (part "root_0_RSM3422_C7425471_"))
    )
    (comp (ref "U6")
      (value "CTM1051KAT")
      (footprint "COMM-TH_CTM1051KAT")
      (fields (field (name "MANUFACTURER") "VISOM"))
      (libsource (lib "altium-import") (part "root_0_CTM1051KAT_"))
    )
    (comp (ref "U7")
      (value "TLV1117LV33DCYR")
      (footprint "TO9")
      (libsource (lib "altium-import") (part "root_0_TLV1117LV33DCYR_"))
    )
    (comp (ref "U8")
      (value "LTV-217-C-G")
      (footprint "SOP-4")
      (libsource (lib "altium-import") (part "root_0_LTV-217-C-G_"))
    )
    (comp (ref "U9")
      (value "LTV-217-C-G")
      (footprint "SOP-4")
      (libsource (lib "altium-import") (part "root_0_LTV-217-C-G_"))
    )
    (comp (ref "U10")
      (value "LTV-217-C-G")
      (footprint "SOP-4")
      (libsource (lib "altium-import") (part "root_0_LTV-217-C-G_"))
    )
    (comp (ref "U11")
      (value "LTV-217-C-G")
      (footprint "SOP-4")
      (libsource (lib "altium-import") (part "root_0_LTV-217-C-G_"))
    )
    (comp (ref "U12")
      (value "LTV-217-C-G")
      (footprint "SOP-4")
      (libsource (lib "altium-import") (part "root_0_LTV-217-C-G_"))
    )
    (comp (ref "U13")
      (value "LTV-217-C-G")
      (footprint "SOP-4")
      (libsource (lib "altium-import") (part "root_0_LTV-217-C-G_"))
    )
    (comp (ref "U14")
      (value "TD301M485")
      (footprint "COMM-TH_TD301M485")
      (fields (field (name "MANUFACTURER") "VISOM"))
      (libsource (lib "altium-import") (part "root_0_TD301M485_"))
    )
    (comp (ref "U17")
      (value "LTV-217-C-G")
      (footprint "SOP-4")
      (libsource (lib "altium-import") (part "root_0_LTV-217-C-G_"))
    )
    (comp (ref "U18")
      (value "LTV-217-C-G")
      (footprint "SOP-4")
      (libsource (lib "altium-import") (part "root_0_LTV-217-C-G_"))
    )
    (comp (ref "U19")
      (value "TD331S232H")
      (footprint "U1")
      (libsource (lib "altium-import") (part "root_0_TD331S232H_"))
    )
    (comp (ref "U20")
      (value "LTV-217-C-G")
      (footprint "SOP-4")
      (libsource (lib "altium-import") (part "root_0_LTV-217-C-G_"))
    )
    (comp (ref "U21")
      (value "LTV-247")
      (footprint "SOP16-1")
      (libsource (lib "altium-import") (part "root_0_LTV-247_"))
    )
    (comp (ref "U22")
      (value "LTV-217-C-G")
      (footprint "SOP-4")
      (libsource (lib "altium-import") (part "root_0_LTV-217-C-G_"))
    )
    (comp (ref "U23")
      (value "LTV-217-C-G")
      (footprint "SOP-4")
      (libsource (lib "altium-import") (part "root_0_LTV-217-C-G_"))
    )
    (comp (ref "U24")
      (value "LTV-217-C-G")
      (footprint "SOP-4")
      (libsource (lib "altium-import") (part "root_0_LTV-217-C-G_"))
    )
    (comp (ref "U25")
      (value "LTV-217-C-G")
      (footprint "SOP-4")
      (libsource (lib "altium-import") (part "root_0_LTV-217-C-G_"))
    )
    (comp (ref "U26")
      (value "LTV-217-C-G")
      (footprint "SOP-4")
      (libsource (lib "altium-import") (part "root_0_LTV-217-C-G_"))
    )
    (comp (ref "U27")
      (value "AM26LV32IDR")
      (footprint "SOP16")
      (fields (field (name "MANUFACTURER PART") "AM26LV32CDR"))
      (libsource (lib "altium-import") (part "root_0_AM26LV32CDR_"))
    )
    (comp (ref "U28")
      (value "LTV-217-C-G")
      (footprint "SOP-4")
      (libsource (lib "altium-import") (part "root_0_LTV-217-C-G_"))
    )
    (comp (ref "U29")
      (value "SN74AHC1G02DBVR")
      (footprint "SOT32-6")
      (fields (field (name "MANUFACTURER PART") "74AHC1G02GV"))
      (libsource (lib "altium-import") (part "root_0_74AHC1G02GV_"))
    )
    (comp (ref "U30")
      (value "LTV-217-C-G")
      (footprint "SOP-4")
      (libsource (lib "altium-import") (part "root_0_LTV-217-C-G_"))
    )
    (comp (ref "U31")
      (value "SN74AHC1G02DBVR")
      (footprint "SOT32-6")
      (fields (field (name "MANUFACTURER PART") "74AHC1G02GV"))
      (libsource (lib "altium-import") (part "root_0_74AHC1G02GV_"))
    )
    (comp (ref "U32")
      (value "LTV-217-C-G")
      (footprint "SOP-4")
      (libsource (lib "altium-import") (part "root_0_LTV-217-C-G_"))
    )
    (comp (ref "U33")
      (value "STM32F407VET6")
      (footprint "100PIN")
      (libsource (lib "大板") (part "STM32F407VET6"))
    )
    (comp (ref "U34")
      (value "AT24C64D-SSHM-T")
      (footprint "SOP-8")
      (description "Header, 4-Pin, Dual row")
      (fields (field (name "PUBLISHER") "Altium Limited"))
      (libsource (lib "大板") (part "Header 4X2A"))
    )
    (comp (ref "U35")
      (value "LTV-217-C-G")
      (footprint "SOP-4")
      (libsource (lib "altium-import") (part "root_0_LTV-217-C-G_"))
    )
    (comp (ref "U36")
      (value "LTV-217-C-G")
      (footprint "SOP-4")
      (libsource (lib "altium-import") (part "root_0_LTV-217-C-G_"))
    )
    (comp (ref "U37")
      (value "LTV-217-C-G")
      (footprint "SOP-4")
      (libsource (lib "altium-import") (part "root_0_LTV-217-C-G_"))
    )
    (comp (ref "X1")
      (value "8MHz")
      (footprint "OSC-SMD_4P-L5.0-W3.2-BL_SG5032")
      (fields (field (name "CONTRIBUTOR") "LCSC"))
      (libsource (lib "低成本_控制-2") (part "8MHz"))
    )
  )
  (nets
    (net (code "1") (name "/+24V_M") (class "Default")
      (node (ref "K1") (pin "3") (pinfunction "3_3") (pintype "passive"))
      (node (ref "K1") (pin "6") (pinfunction "6_6") (pintype "passive"))
      (node (ref "P6") (pin "1") (pinfunction "1_1") (pintype "passive"))
      (node (ref "T1") (pin "3") (pinfunction "3_3") (pintype "passive"))
      (node (ref "T1") (pin "6") (pinfunction "6_6") (pintype "passive"))
    )
    (net (code "2") (name "/485_A") (class "Default")
      (node (ref "C40") (pin "2") (pinfunction "2_2") (pintype "passive"))
      (node (ref "D30") (pin "2") (pinfunction "2_2") (pintype "passive"))
      (node (ref "D6") (pin "1") (pinfunction "1_1") (pintype "passive"))
      (node (ref "L5") (pin "4") (pinfunction "4_4") (pintype "passive"))
      (node (ref "P12") (pin "2") (pinfunction "2_2") (pintype "passive"))
      (node (ref "R62") (pin "2") (pinfunction "2_2") (pintype "passive"))
    )
    (net (code "3") (name "/485_B") (class "Default")
      (node (ref "C36") (pin "2") (pinfunction "2_2") (pintype "passive"))
      (node (ref "D30") (pin "1") (pinfunction "1_1") (pintype "passive"))
      (node (ref "D5") (pin "1") (pinfunction "1_1") (pintype "passive"))
      (node (ref "L5") (pin "3") (pinfunction "3_3") (pintype "passive"))
      (node (ref "P12") (pin "1") (pinfunction "1_1") (pintype "passive"))
      (node (ref "R62") (pin "1") (pinfunction "1_1") (pintype "passive"))
    )
    (net (code "4") (name "/A+") (class "Default")
      (node (ref "P23") (pin "1") (pinfunction "1_1") (pintype "passive"))
      (node (ref "R146") (pin "1") (pinfunction "1_1") (pintype "passive"))
      (node (ref "U27") (pin "2") (pinfunction "1A_2") (pintype "passive"))
    )
    (net (code "5") (name "/A-") (class "Default")
      (node (ref "P23") (pin "2") (pinfunction "2_2") (pintype "passive"))
      (node (ref "R146") (pin "2") (pinfunction "2_2") (pintype "passive"))
      (node (ref "U27") (pin "1") (pinfunction "1B_1") (pintype "passive"))
    )
    (net (code "6") (name "/B+") (class "Default")
      (node (ref "P23") (pin "3") (pinfunction "3_3") (pintype "passive"))
      (node (ref "R152") (pin "2") (pinfunction "2_2") (pintype "passive"))
      (node (ref "U27") (pin "6") (pinfunction "2A_6") (pintype "passive"))
    )
    (net (code "7") (name "/B-") (class "Default")
      (node (ref "P23") (pin "4") (pinfunction "4_4") (pintype "passive"))
      (node (ref "R152") (pin "1") (pinfunction "1_1") (pintype "passive"))
      (node (ref "U27") (pin "7") (pinfunction "2B_7") (pintype "passive"))
    )
    (net (code "8") (name "/Bell") (class "Default")
      (node (ref "C33") (pin "2") (pinfunction "2_2") (pintype "passive"))
      (node (ref "P7") (pin "9") (pinfunction "9_9") (pintype "passive"))
      (node (ref "R44") (pin "2") (pinfunction "2_2") (pintype "passive"))
      (node (ref "U12") (pin "4") (pinfunction "4_4") (pintype "passive"))
    )
    (net (code "9") (name "/Bell com") (class "Default")
      (node (ref "C33") (pin "1") (pinfunction "1_1") (pintype "passive"))
      (node (ref "P7") (pin "8") (pinfunction "8_8") (pintype "passive"))
      (node (ref "U12") (pin "3") (pinfunction "3_3") (pintype "passive"))
    )
    (net (code "10") (name "/CAN1 H") (class "Default")
      (node (ref "C6") (pin "1") (pinfunction "1_1") (pintype "passive"))
      (node (ref "L1") (pin "1") (pinfunction "1_1") (pintype "passive"))
      (node (ref "P1") (pin "2") (pinfunction "2_2") (pintype "passive"))
      (node (ref "P7") (pin "12") (pinfunction "12_12") (pintype "passive"))
      (node (ref "R8") (pin "1") (pinfunction "1_1") (pintype "passive"))
      (node (ref "TVS3") (pin "1") (pinfunction "1_1") (pintype "passive"))
    )
    (net (code "11") (name "/CAN1 L") (class "Default")
      (node (ref "C9") (pin "1") (pinfunction "1_1") (pintype "passive"))
      (node (ref "L1") (pin "2") (pinfunction "2_2") (pintype "passive"))
      (node (ref "P1") (pin "1") (pinfunction "1_1") (pintype "passive"))
      (node (ref "P7") (pin "13") (pinfunction "13_13") (pintype "passive"))
      (node (ref "R8") (pin "2") (pinfunction "2_2") (pintype "passive"))
      (node (ref "TVS3") (pin "2") (pinfunction "2_2") (pintype "passive"))
    )
    (net (code "12") (name "/CAN2 H") (class "Default")
      (node (ref "C22") (pin "1") (pinfunction "1_1") (pintype "passive"))
      (node (ref "L4") (pin "3") (pinfunction "3_3") (pintype "passive"))
      (node (ref "P4") (pin "2") (pinfunction "2_2") (pintype "passive"))
      (node (ref "R20") (pin "2") (pinfunction "2_2") (pintype "passive"))
      (node (ref "TVS2") (pin "1") (pinfunction "1_1") (pintype "passive"))
    )
    (net (code "13") (name "/CAN2 L") (class "Default")
      (node (ref "C27") (pin "1") (pinfunction "1_1") (pintype "passive"))
      (node (ref "L4") (pin "4") (pinfunction "4_4") (pintype "passive"))
      (node (ref "P4") (pin "1") (pinfunction "1_1") (pintype "passive"))
      (node (ref "R20") (pin "1") (pinfunction "1_1") (pintype "passive"))
      (node (ref "TVS2") (pin "2") (pinfunction "2_2") (pintype "passive"))
    )
    (net (code "14") (name "/EMC-") (class "Default")
      (node (ref "P7") (pin "11") (pinfunction "11_11") (pintype "passive"))
      (node (ref "P8") (pin "1") (pinfunction "1_1") (pintype "passive"))
    )
    (net (code "15") (name "/ExPose") (class "Default")
      (node (ref "D81") (pin "2") (pinfunction "K_2") (pintype "passive"))
      (node (ref "P21") (pin "5") (pinfunction "5_5") (pintype "passive"))
      (node (ref "Q7") (pin "3") (pinfunction "C_3") (pintype "passive"))
    )
    (net (code "16") (name "/FDP_Enable") (class "Default")
      (node (ref "D106") (pin "2") (pinfunction "2_2") (pintype "passive"))
      (node (ref "D107") (pin "2") (pinfunction "K_2") (pintype "passive"))
      (node (ref "P32") (pin "5") (pinfunction "5_5") (pintype "passive"))
      (node (ref "R208") (pin "1") (pinfunction "1_1") (pintype "passive"))
      (node (ref "U37") (pin "2") (pinfunction "2_2") (pintype "passive"))
    )
    (net (code "17") (name "/FPD_BOTT") (class "Default")
      (node (ref "D94") (pin "1") (pinfunction "1_1") (pintype "passive"))
      (node (ref "P28") (pin "2") (pinfunction "2_2") (pintype "passive"))
    )
    (net (code "18") (name "/Fault") (class "Default")
      (node (ref "D78") (pin "2") (pinfunction "2_2") (pintype "passive"))
      (node (ref "D79") (pin "2") (pinfunction "K_2") (pintype "passive"))
      (node (ref "P21") (pin "2") (pinfunction "2_2") (pintype "passive"))
      (node (ref "U24") (pin "2") (pinfunction "2_2") (pintype "passive"))
    )
    (net (code "19") (name "/Fault1") (class "Default")
      (node (ref "C30") (pin "2") (pinfunction "2_2") (pintype "passive"))
      (node (ref "P7") (pin "7") (pinfunction "7_7") (pintype "passive"))
      (node (ref "R32") (pin "2") (pinfunction "2_2") (pintype "passive"))
      (node (ref "U9") (pin "4") (pinfunction "4_4") (pintype "passive"))
    )
    (net (code "20") (name "/Fault1 com") (class "Default")
      (node (ref "C30") (pin "1") (pinfunction "1_1") (pintype "passive"))
      (node (ref "P7") (pin "6") (pinfunction "6_6") (pintype "passive"))
      (node (ref "U9") (pin "3") (pinfunction "3_3") (pintype "passive"))
    )
    (net (code "21") (name "/FloOut") (class "Default")
      (node (ref "D72") (pin "2") (pinfunction "K_2") (pintype "passive"))
      (node (ref "D73") (pin "2") (pinfunction "2_2") (pintype "passive"))
      (node (ref "P19") (pin "4") (pinfunction "3_4") (pintype "passive"))
      (node (ref "U21") (pin "8") (pinfunction "CAT4_8") (pintype "passive"))
    )
    (net (code "22") (name "/FloSY") (class "Default")
      (node (ref "C53") (pin "2") (pinfunction "2_2") (pintype "passive"))
      (node (ref "P19") (pin "5") (pinfunction "2_5") (pintype "passive"))
      (node (ref "R110") (pin "2") (pinfunction "2_2") (pintype "passive"))
      (node (ref "U21") (pin "14") (pinfunction "COL2_14") (pintype "passive"))
    )
    (net (code "23") (name "/Foreward") (class "Default")
      (node (ref "D89") (pin "1") (pinfunction "1_1") (pintype "passive"))
      (node (ref "P25") (pin "2") (pinfunction "2_2") (pintype "passive"))
    )
    (net (code "24") (name "/Hand_Pre") (class "Default")
      (node (ref "P7") (pin "14") (pinfunction "14_14") (pintype "passive"))
      (node (ref "R43") (pin "1") (pinfunction "1_1") (pintype "passive"))
      (node (ref "R48") (pin "1") (pinfunction "1_1") (pintype "passive"))
    )
    (net (code "25") (name "/KV85") (class "Default")
      (node (ref "D74") (pin "2") (pinfunction "2_2") (pintype "passive"))
      (node (ref "D76") (pin "2") (pinfunction "K_2") (pintype "passive"))
      (node (ref "P21") (pin "1") (pinfunction "1_1") (pintype "passive"))
      (node (ref "U22") (pin "2") (pinfunction "2_2") (pintype "passive"))
    )
    (net (code "26") (name "/LCD_RX") (class "Default")
      (node (ref "D35") (pin "2") (pinfunction "2_2") (pintype "passive"))
      (node (ref "P15") (pin "3") (pinfunction "3_3") (pintype "passive"))
      (node (ref "R97") (pin "1") (pinfunction "1_1") (pintype "passive"))
    )
    (net (code "27") (name "/LCD_TX") (class "Default")
      (node (ref "D36") (pin "2") (pinfunction "2_2") (pintype "passive"))
      (node (ref "P15") (pin "2") (pinfunction "2_2") (pintype "passive"))
      (node (ref "R98") (pin "1") (pinfunction "1_1") (pintype "passive"))
    )
    (net (code "28") (name "/NRST") (class "Default")
      (node (ref "C83") (pin "2") (pinfunction "2_2") (pintype "passive"))
      (node (ref "R182") (pin "1") (pinfunction "1_1") (pintype "passive"))
      (node (ref "U33") (pin "14") (pinfunction "NRST_14") (pintype "passive"))
    )
    (net (code "29") (name "/P14 24 M") (class "Default")
      (node (ref "C50") (pin "2") (pinfunction "2_2") (pintype "passive"))
      (node (ref "D56") (pin "1") (pinfunction "1_1") (pintype "passive"))
      (node (ref "Q5") (pin "3") (pinfunction "C_3") (pintype "passive"))
      (node (ref "R95") (pin "2") (pinfunction "2_2") (pintype "passive"))
      (node (ref "T1") (pin "8") (pinfunction "8_8") (pintype "passive"))
    )
    (net (code "30") (name "/P16 P17 P18") (class "Default")
      (node (ref "P16") (pin "1") (pinfunction "1_1") (pintype "passive"))
      (node (ref "P17") (pin "1") (pinfunction "1_1") (pintype "passive"))
      (node (ref "P18") (pin "1") (pinfunction "1_1") (pintype "passive"))
      (node (ref "Q6") (pin "3") (pinfunction "D_3") (pintype "passive"))
    )
    (net (code "31") (name "/PA3(BZ)") (class "Default")
      (node (ref "R195") (pin "2") (pinfunction "2_2") (pintype "passive"))
      (node (ref "U33") (pin "26") (pinfunction "PA3_26") (pintype "passive"))
    )
    (net (code "32") (name "/PA4(KV85)") (class "Default")
      (node (ref "C56") (pin "2") (pinfunction "2_2") (pintype "passive"))
      (node (ref "R123") (pin "2") (pinfunction "2_2") (pintype "passive"))
      (node (ref "U22") (pin "4") (pinfunction "4_4") (pintype "passive"))
      (node (ref "U33") (pin "29") (pinfunction "PA4_29") (pintype "passive"))
    )
    (net (code "33") (name "/PA5(Fault)") (class "Default")
      (node (ref "C58") (pin "2") (pinfunction "2_2") (pintype "passive"))
      (node (ref "R130") (pin "2") (pinfunction "2_2") (pintype "passive"))
      (node (ref "U24") (pin "4") (pinfunction "4_4") (pintype "passive"))
      (node (ref "U33") (pin "30") (pinfunction "PA5_30") (pintype "passive"))
    )
    (net (code "34") (name "/PA6(READY)") (class "Default")
      (node (ref "C59") (pin "2") (pinfunction "2_2") (pintype "passive"))
      (node (ref "R139") (pin "2") (pinfunction "2_2") (pintype "passive"))
      (node (ref "U26") (pin "4") (pinfunction "4_4") (pintype "passive"))
      (node (ref "U33") (pin "31") (pinfunction "PA6_31") (pintype "passive"))
    )
    (net (code "35") (name "/PA7(PRE)") (class "Default")
      (node (ref "D75") (pin "2") (pinfunction "2_2") (pintype "passive"))
      (node (ref "D77") (pin "2") (pinfunction "K_2") (pintype "passive"))
      (node (ref "U23") (pin "2") (pinfunction "2_2") (pintype "passive"))
      (node (ref "U33") (pin "32") (pinfunction "PA7_32") (pintype "passive"))
    )
    (net (code "36") (name "/PA8(SCL)") (class "Default")
      (node (ref "C90") (pin "1") (pinfunction "1_1") (pintype "passive"))
      (node (ref "R190") (pin "2") (pinfunction "2_2") (pintype "passive"))
      (node (ref "U33") (pin "67") (pinfunction "PA8_67") (pintype "passive"))
      (node (ref "U34") (pin "6") (pinfunction "6_6") (pintype "passive"))
    )
    (net (code "37") (name "/PA11(USB D-)") (class "Default")
      (node (ref "R187") (pin "1") (pinfunction "1_1") (pintype "passive"))
      (node (ref "U33") (pin "70") (pinfunction "PA11_70") (pintype "passive"))
    )
    (net (code "38") (name "/PA12(USB D+)") (class "Default")
      (node (ref "R188") (pin "1") (pinfunction "1_1") (pintype "passive"))
      (node (ref "U33") (pin "71") (pinfunction "PA12_71") (pintype "passive"))
    )
    (net (code "39") (name "/PA13(SWDIO)") (class "Default")
      (node (ref "P31") (pin "2") (pinfunction "2_2") (pintype "passive"))
      (node (ref "R192") (pin "2") (pinfunction "2_2") (pintype "passive"))
      (node (ref "U33") (pin "72") (pinfunction "PA13(JTMS-SWDIO)_72") (pintype "passive"))
    )
    (net (code "40") (name "/PA14(SWCLK)") (class "Default")
      (node (ref "P31") (pin "3") (pinfunction "3_3") (pintype "passive"))
      (node (ref "R193") (pin "2") (pinfunction "2_2") (pintype "passive"))
      (node (ref "U33") (pin "76") (pinfunction "PA14(JTCK-SWCLK)_76") (pintype "passive"))
    )
    (net (code "41") (name "/PA15(EA)") (class "Default")
      (node (ref "R162") (pin "1") (pinfunction "1_1") (pintype "passive"))
      (node (ref "U27") (pin "3") (pinfunction "1Y_3") (pintype "passive"))
      (node (ref "U33") (pin "77") (pinfunction "PA15(JTDI)_77") (pintype "passive"))
    )
    (net (code "42") (name "/PB3(EB)") (class "Default")
      (node (ref "R156") (pin "1") (pinfunction "1_1") (pintype "passive"))
      (node (ref "U27") (pin "5") (pinfunction "2Y_5") (pintype "passive"))
      (node (ref "U33") (pin "89") (pinfunction "PB3(JTDOTRACESWO)_89") (pintype "passive"))
    )
    (net (code "43") (name "/PB4(24_M)") (class "Default")
      (node (ref "D40") (pin "2") (pinfunction "2_2") (pintype "passive"))
      (node (ref "D41") (pin "2") (pinfunction "K_2") (pintype "passive"))
      (node (ref "U17") (pin "2") (pinfunction "2_2") (pintype "passive"))
      (node (ref "U33") (pin "90") (pinfunction "PB4(NJTRST)_90") (pintype "passive"))
    )
    (net (code "44") (name "/PB5(485 enable)") (class "Default")
      (node (ref "U33") (pin "91") (pinfunction "PB5_91") (pintype "passive"))
    )
    (net (code "45") (name "/PB6(485_TX)") (class "Default")
      (node (ref "U14") (pin "2") (pinfunction "TXD_2") (pintype "passive"))
      (node (ref "U33") (pin "92") (pinfunction "PB6_92") (pintype "passive"))
    )
    (net (code "46") (name "/PB7(485_RX)") (class "Default")
      (node (ref "U14") (pin "1") (pinfunction "RXD_1") (pintype "passive"))
      (node (ref "U33") (pin "93") (pinfunction "PB7_93") (pintype "passive"))
    )
    (net (code "47") (name "/PB8(CAN1 RX)") (class "Default")
      (node (ref "U2") (pin "4") (pinfunction "RXD_4") (pintype "passive"))
      (node (ref "U33") (pin "95") (pinfunction "PB8_95") (pintype "passive"))
    )
    (net (code "48") (name "/PB9(CAN1 TX)") (class "Default")
      (node (ref "U2") (pin "3") (pinfunction "TXD_3") (pintype "passive"))
      (node (ref "U33") (pin "96") (pinfunction "PB9_96") (pintype "passive"))
    )
    (net (code "49") (name "/PB12(CAN2_RX)") (class "Default")
      (node (ref "U33") (pin "51") (pinfunction "PB12_51") (pintype "passive"))
      (node (ref "U6") (pin "4") (pinfunction "RXD_4") (pintype "passive"))
    )
    (net (code "50") (name "/PB13(CAN2_TX)") (class "Default")
      (node (ref "U33") (pin "52") (pinfunction "PB13_52") (pintype "passive"))
      (node (ref "U6") (pin "3") (pinfunction "TXD_3") (pintype "passive"))
    )
    (net (code "51") (name "/PC0(FloOut)") (class "Default")
      (node (ref "C55") (pin "2") (pinfunction "2_2") (pintype "passive"))
      (node (ref "R119") (pin "2") (pinfunction "2_2") (pintype "passive"))
      (node (ref "U21") (pin "10") (pinfunction "COL4_10") (pintype "passive"))
      (node (ref "U33") (pin "15") (pinfunction "PC0_15") (pintype "passive"))
    )
    (net (code "52") (name "/PC1(RadOut)") (class "Default")
      (node (ref "C54") (pin "2") (pinfunction "2_2") (pintype "passive"))
      (node (ref "R115") (pin "2") (pinfunction "2_2") (pintype "passive"))
      (node (ref "U21") (pin "12") (pinfunction "COL3_12") (pintype "passive"))
      (node (ref "U33") (pin "16") (pinfunction "PC1_16") (pintype "passive"))
    )
    (net (code "53") (name "/PC2(FloSY)") (class "Default")
      (node (ref "D68") (pin "2") (pinfunction "K_2") (pintype "passive"))
      (node (ref "D69") (pin "2") (pinfunction "2_2") (pintype "passive"))
      (node (ref "U21") (pin "4") (pinfunction "CAT2_4") (pintype "passive"))
      (node (ref "U33") (pin "17") (pinfunction "PC2_17") (pintype "passive"))
    )
    (net (code "54") (name "/PC3(RadSY)") (class "Default")
      (node (ref "D66") (pin "2") (pinfunction "K_2") (pintype "passive"))
      (node (ref "D67") (pin "2") (pinfunction "2_2") (pintype "passive"))
      (node (ref "U21") (pin "2") (pinfunction "CAT1_2") (pintype "passive"))
      (node (ref "U33") (pin "18") (pinfunction "PC3_18") (pintype "passive"))
    )
    (net (code "55") (name "/PC4(ExPose)") (class "Default")
      (node (ref "D80") (pin "2") (pinfunction "2_2") (pintype "passive"))
      (node (ref "D82") (pin "2") (pinfunction "K_2") (pintype "passive"))
      (node (ref "U25") (pin "2") (pinfunction "2_2") (pintype "passive"))
      (node (ref "U33") (pin "33") (pinfunction "PC4_33") (pintype "passive"))
    )
    (net (code "56") (name "/PC9(SDA)") (class "Default")
      (node (ref "C91") (pin "1") (pinfunction "1_1") (pintype "passive"))
      (node (ref "R189") (pin "2") (pinfunction "2_2") (pintype "passive"))
      (node (ref "U33") (pin "66") (pinfunction "PC9_66") (pintype "passive"))
      (node (ref "U34") (pin "5") (pinfunction "5_5") (pintype "passive"))
    )
    (net (code "57") (name "/PC10(TX)") (class "Default")
      (node (ref "U19") (pin "9") (pinfunction "TXD_9") (pintype "passive"))
      (node (ref "U33") (pin "78") (pinfunction "PC10_78") (pintype "passive"))
    )
    (net (code "58") (name "/PC11(RX)") (class "Default")
      (node (ref "U19") (pin "8") (pinfunction "RXD_8") (pintype "passive"))
      (node (ref "U33") (pin "79") (pinfunction "PC11_79") (pintype "passive"))
    )
    (net (code "59") (name "/PC12(TX)") (class "Default")
      (node (ref "P29") (pin "2") (pinfunction "2_2") (pintype "passive"))
      (node (ref "U33") (pin "80") (pinfunction "PC12_80") (pintype "passive"))
    )
    (net (code "60") (name "/PC13(off)") (class "Default")
      (node (ref "C32") (pin "2") (pinfunction "2_2") (pintype "passive"))
      (node (ref "R41") (pin "2") (pinfunction "2_2") (pintype "passive"))
      (node (ref "U11") (pin "4") (pinfunction "4_4") (pintype "passive"))
      (node (ref "U33") (pin "7") (pinfunction "PC13_7") (pintype "passive"))
    )
    (net (code "61") (name "/PC14(Fault1)") (class "Default")
      (node (ref "D180") (pin "2") (pinfunction "2_2") (pintype "passive"))
      (node (ref "D20") (pin "2") (pinfunction "K_2") (pintype "passive"))
      (node (ref "U33") (pin "8") (pinfunction "PC14-OSC32_IN(PC14)_8") (pintype "passive"))
      (node (ref "U9") (pin "2") (pinfunction "2_2") (pintype "passive"))
    )
    (net (code "62") (name "/PC_RX+") (class "Default")
      (node (ref "D15") (pin "1") (pinfunction "1_1") (pintype "passive"))
      (node (ref "D32") (pin "2") (pinfunction "2_2") (pintype "passive"))
      (node (ref "L7") (pin "4") (pinfunction "4_4") (pintype "passive"))
      (node (ref "P11") (pin "2") (pinfunction "2_2") (pintype "passive"))
    )
    (net (code "63") (name "/PC_RX+2") (class "Default")
      (node (ref "D3") (pin "2") (pinfunction "2_2") (pintype "passive"))
      (node (ref "D7") (pin "1") (pinfunction "1_1") (pintype "passive"))
      (node (ref "L11") (pin "4") (pinfunction "4_4") (pintype "passive"))
      (node (ref "P34") (pin "2") (pinfunction "2_2") (pintype "passive"))
    )
    (net (code "64") (name "/PC_RX-") (class "Default")
      (node (ref "D29") (pin "1") (pinfunction "1_1") (pintype "passive"))
      (node (ref "D32") (pin "1") (pinfunction "1_1") (pintype "passive"))
      (node (ref "L7") (pin "3") (pinfunction "3_3") (pintype "passive"))
      (node (ref "P11") (pin "1") (pinfunction "1_1") (pintype "passive"))
    )
    (net (code "65") (name "/PC_RX-2") (class "Default")
      (node (ref "D11") (pin "1") (pinfunction "1_1") (pintype "passive"))
      (node (ref "D3") (pin "1") (pinfunction "1_1") (pintype "passive"))
      (node (ref "L11") (pin "3") (pinfunction "3_3") (pintype "passive"))
      (node (ref "P34") (pin "1") (pinfunction "1_1") (pintype "passive"))
    )
    (net (code "66") (name "/PC_TX+") (class "Default")
      (node (ref "D31") (pin "1") (pinfunction "1_1") (pintype "passive"))
      (node (ref "D33") (pin "1") (pinfunction "1_1") (pintype "passive"))
      (node (ref "L6") (pin "3") (pinfunction "3_3") (pintype "passive"))
      (node (ref "P11") (pin "4") (pinfunction "4_4") (pintype "passive"))
      (node (ref "R82") (pin "2") (pinfunction "2_2") (pintype "passive"))
    )
    (net (code "67") (name "/PC_TX+2") (class "Default")
      (node (ref "D12") (pin "1") (pinfunction "1_1") (pintype "passive"))
      (node (ref "D2") (pin "1") (pinfunction "1_1") (pintype "passive"))
      (node (ref "L8") (pin "3") (pinfunction "3_3") (pintype "passive"))
      (node (ref "P34") (pin "4") (pinfunction "4_4") (pintype "passive"))
      (node (ref "R81") (pin "1") (pinfunction "1_1") (pintype "passive"))
    )
    (net (code "68") (name "/PC_TX-") (class "Default")
      (node (ref "D31") (pin "2") (pinfunction "2_2") (pintype "passive"))
      (node (ref "D34") (pin "1") (pinfunction "1_1") (pintype "passive"))
      (node (ref "L6") (pin "4") (pinfunction "4_4") (pintype "passive"))
      (node (ref "P11") (pin "3") (pinfunction "3_3") (pintype "passive"))
      (node (ref "R82") (pin "1") (pinfunction "1_1") (pintype "passive"))
    )
    (net (code "69") (name "/PC_TX-2") (class "Default")
      (node (ref "D14") (pin "1") (pinfunction "1_1") (pintype "passive"))
      (node (ref "D2") (pin "2") (pinfunction "2_2") (pintype "passive"))
      (node (ref "L8") (pin "4") (pinfunction "4_4") (pintype "passive"))
      (node (ref "P34") (pin "3") (pinfunction "3_3") (pintype "passive"))
      (node (ref "R81") (pin "2") (pinfunction "2_2") (pintype "passive"))
    )
    (net (code "70") (name "/PD2(RX)") (class "Default")
      (node (ref "P29") (pin "1") (pinfunction "1_1") (pintype "passive"))
      (node (ref "U33") (pin "83") (pinfunction "PD2_83") (pintype "passive"))
    )
    (net (code "71") (name "/PD5(422-TX)") (class "Default")
      (node (ref "U33") (pin "86") (pinfunction "PD5_86") (pintype "passive"))
      (node (ref "U5") (pin "3") (pinfunction "TXD_3") (pintype "passive"))
    )
    (net (code "72") (name "/PD6(422-RX)") (class "Default")
      (node (ref "U33") (pin "87") (pinfunction "PD6_87") (pintype "passive"))
      (node (ref "U5") (pin "4") (pinfunction "RXD_4") (pintype "passive"))
    )
    (net (code "73") (name "/PD9(p16,p17,p18)") (class "Default")
      (node (ref "D64") (pin "2") (pinfunction "2_2") (pintype "passive"))
      (node (ref "D65") (pin "2") (pinfunction "K_2") (pintype "passive"))
      (node (ref "U20") (pin "2") (pinfunction "2_2") (pintype "passive"))
      (node (ref "U33") (pin "56") (pinfunction "PD9_56") (pintype "passive"))
    )
    (net (code "74") (name "/PD10(P14)") (class "Default")
      (node (ref "D54") (pin "2") (pinfunction "2_2") (pintype "passive"))
      (node (ref "D57") (pin "2") (pinfunction "K_2") (pintype "passive"))
      (node (ref "U18") (pin "2") (pinfunction "2_2") (pintype "passive"))
      (node (ref "U33") (pin "57") (pinfunction "PD10_57") (pintype "passive"))
    )
    (net (code "75") (name "/PD11(Origin)") (class "Default")
      (node (ref "C61") (pin "2") (pinfunction "2_2") (pintype "passive"))
      (node (ref "R150") (pin "2") (pinfunction "2_2") (pintype "passive"))
      (node (ref "U28") (pin "4") (pinfunction "4_4") (pintype "passive"))
      (node (ref "U33") (pin "58") (pinfunction "PD11_58") (pintype "passive"))
    )
    (net (code "76") (name "/PD14(Foreward)") (class "Default")
      (node (ref "C63") (pin "2") (pinfunction "2_2") (pintype "passive"))
      (node (ref "R169") (pin "2") (pinfunction "2_2") (pintype "passive"))
      (node (ref "U30") (pin "4") (pinfunction "4_4") (pintype "passive"))
      (node (ref "U33") (pin "61") (pinfunction "PD14_61") (pintype "passive"))
    )
    (net (code "77") (name "/PD15(Reverse)") (class "Default")
      (node (ref "C65") (pin "2") (pinfunction "2_2") (pintype "passive"))
      (node (ref "R175") (pin "2") (pinfunction "2_2") (pintype "passive"))
      (node (ref "U32") (pin "4") (pinfunction "4_4") (pintype "passive"))
      (node (ref "U33") (pin "62") (pinfunction "PD15_62") (pintype "passive"))
    )
    (net (code "78") (name "/PE2(EMC-)") (class "Default")
      (node (ref "C31") (pin "2") (pinfunction "2_2") (pintype "passive"))
      (node (ref "R33") (pin "2") (pinfunction "2_2") (pintype "passive"))
      (node (ref "U10") (pin "4") (pinfunction "4_4") (pintype "passive"))
      (node (ref "U33") (pin "1") (pinfunction "PE2_1") (pintype "passive"))
    )
    (net (code "79") (name "/PE3(Bell)") (class "Default")
      (node (ref "D23") (pin "2") (pinfunction "2_2") (pintype "passive"))
      (node (ref "D26") (pin "2") (pinfunction "K_2") (pintype "passive"))
      (node (ref "U12") (pin "2") (pinfunction "2_2") (pintype "passive"))
      (node (ref "U33") (pin "2") (pinfunction "PE3_2") (pintype "passive"))
    )
    (net (code "80") (name "/PE4(Pre)") (class "Default")
      (node (ref "C34") (pin "1") (pinfunction "1_1") (pintype "passive"))
      (node (ref "R46") (pin "1") (pinfunction "1_1") (pintype "passive"))
      (node (ref "U13") (pin "4") (pinfunction "4_4") (pintype "passive"))
      (node (ref "U33") (pin "3") (pinfunction "PE4_3") (pintype "passive"))
    )
    (net (code "81") (name "/PE6(Exp)") (class "Default")
      (node (ref "C29") (pin "2") (pinfunction "2_2") (pintype "passive"))
      (node (ref "R30") (pin "2") (pinfunction "2_2") (pintype "passive"))
      (node (ref "U33") (pin "5") (pinfunction "PE6_5") (pintype "passive"))
      (node (ref "U8") (pin "4") (pinfunction "4_4") (pintype "passive"))
    )
    (net (code "82") (name "/PE13(SYNC OUT)") (class "Default")
      (node (ref "C93") (pin "2") (pinfunction "2_2") (pintype "passive"))
      (node (ref "R203") (pin "2") (pinfunction "2_2") (pintype "passive"))
      (node (ref "U33") (pin "44") (pinfunction "PE13_44") (pintype "passive"))
      (node (ref "U36") (pin "4") (pinfunction "4_4") (pintype "passive"))
    )
    (net (code "83") (name "/PE14(FDP_Enable)") (class "Default")
      (node (ref "C94") (pin "2") (pinfunction "2_2") (pintype "passive"))
      (node (ref "R207") (pin "2") (pinfunction "2_2") (pintype "passive"))
      (node (ref "U33") (pin "45") (pinfunction "PE14_45") (pintype "passive"))
      (node (ref "U37") (pin "4") (pinfunction "4_4") (pintype "passive"))
    )
    (net (code "84") (name "/PE15(SYNC_IN)") (class "Default")
      (node (ref "D102") (pin "2") (pinfunction "2_2") (pintype "passive"))
      (node (ref "D103") (pin "2") (pinfunction "K_2") (pintype "passive"))
      (node (ref "R198") (pin "1") (pinfunction "1_1") (pintype "passive"))
      (node (ref "U33") (pin "46") (pinfunction "PE15_46") (pintype "passive"))
      (node (ref "U35") (pin "2") (pinfunction "2_2") (pintype "passive"))
    )
    (net (code "85") (name "/PRE") (class "Default")
      (node (ref "C57") (pin "2") (pinfunction "2_2") (pintype "passive"))
      (node (ref "P21") (pin "6") (pinfunction "6_6") (pintype "passive"))
      (node (ref "R125") (pin "2") (pinfunction "2_2") (pintype "passive"))
      (node (ref "U23") (pin "4") (pinfunction "4_4") (pintype "passive"))
    )
    (net (code "86") (name "/READY") (class "Default")
      (node (ref "D83") (pin "2") (pinfunction "2_2") (pintype "passive"))
      (node (ref "D84") (pin "2") (pinfunction "K_2") (pintype "passive"))
      (node (ref "P21") (pin "3") (pinfunction "3_3") (pintype "passive"))
      (node (ref "U26") (pin "2") (pinfunction "2_2") (pintype "passive"))
    )
    (net (code "87") (name "/RadOut") (class "Default")
      (node (ref "D17") (pin "2") (pinfunction "2_2") (pintype "passive"))
      (node (ref "D70") (pin "2") (pinfunction "K_2") (pintype "passive"))
      (node (ref "P19") (pin "2") (pinfunction "5_2") (pintype "passive"))
      (node (ref "U21") (pin "6") (pinfunction "CAT3_6") (pintype "passive"))
    )
    (net (code "88") (name "/RadSY") (class "Default")
      (node (ref "C52") (pin "2") (pinfunction "2_2") (pintype "passive"))
      (node (ref "P19") (pin "3") (pinfunction "4_3") (pintype "passive"))
      (node (ref "R105") (pin "2") (pinfunction "2_2") (pintype "passive"))
      (node (ref "U21") (pin "16") (pinfunction "COL1_16") (pintype "passive"))
    )
    (net (code "89") (name "/Reverse") (class "Default")
      (node (ref "D93") (pin "1") (pinfunction "1_1") (pintype "passive"))
      (node (ref "P27") (pin "2") (pinfunction "2_2") (pintype "passive"))
    )
    (net (code "90") (name "/RunLed") (class "Default")
      (node (ref "D98") (pin "2") (pinfunction "K_2") (pintype "passive"))
      (node (ref "U33") (pin "65") (pinfunction "PC8_65") (pintype "passive"))
    )
    (net (code "91") (name "/SF1+") (class "Default")
      (node (ref "P24") (pin "1") (pinfunction "1_1") (pintype "passive"))
      (node (ref "Q9") (pin "3") (pinfunction "C_3") (pintype "passive"))
    )
    (net (code "92") (name "/SF2+") (class "Default")
      (node (ref "P24") (pin "3") (pinfunction "3_3") (pintype "passive"))
      (node (ref "Q10") (pin "3") (pinfunction "C_3") (pintype "passive"))
    )
    (net (code "93") (name "/SYNC OUT") (class "Default")
      (node (ref "D104") (pin "2") (pinfunction "2_2") (pintype "passive"))
      (node (ref "D105") (pin "2") (pinfunction "K_2") (pintype "passive"))
      (node (ref "P32") (pin "3") (pinfunction "3_3") (pintype "passive"))
      (node (ref "R204") (pin "1") (pinfunction "1_1") (pintype "passive"))
      (node (ref "U36") (pin "2") (pinfunction "2_2") (pintype "passive"))
    )
    (net (code "94") (name "/SYNC_IN_N") (class "Default")
      (node (ref "P32") (pin "2") (pinfunction "2_2") (pintype "passive"))
      (node (ref "Q14") (pin "3") (pinfunction "C_3") (pintype "passive"))
    )
    (net (code "95") (name "/SYNC_IN_p") (class "Default")
      (node (ref "P32") (pin "1") (pinfunction "1_1") (pintype "passive"))
      (node (ref "R199") (pin "2") (pinfunction "2_2") (pintype "passive"))
      (node (ref "R201") (pin "2") (pinfunction "2_2") (pintype "passive"))
      (node (ref "U35") (pin "3") (pinfunction "3_3") (pintype "passive"))
    )
    (net (code "96") (name "/Tube_Bott") (class "Default")
      (node (ref "D90") (pin "1") (pinfunction "1_1") (pintype "passive"))
      (node (ref "P26") (pin "2") (pinfunction "2_2") (pintype "passive"))
    )
    (net (code "97") (name "/USART3_RX") (class "Default")
      (node (ref "U1") (pin "4") (pinfunction "RXD_4") (pintype "passive"))
      (node (ref "U33") (pin "48") (pinfunction "PB11_48") (pintype "passive"))
    )
    (net (code "98") (name "/USART3_TX") (class "Default")
      (node (ref "U1") (pin "3") (pinfunction "TXD_3") (pintype "passive"))
      (node (ref "U33") (pin "47") (pinfunction "PB10_47") (pintype "passive"))
    )
    (net (code "99") (name "/VCC out") (class "Default")
      (node (ref "P19") (pin "1") (pinfunction "6_1") (pintype "passive"))
      (node (ref "P20") (pin "2") (pinfunction "2_2") (pintype "passive"))
      (node (ref "R105") (pin "1") (pinfunction "1_1") (pintype "passive"))
      (node (ref "R110") (pin "1") (pinfunction "1_1") (pintype "passive"))
    )
    (net (code "100") (name "/XCLKIN") (class "Default")
      (node (ref "R2") (pin "1") (pintype "passive"))
      (node (ref "U33") (pin "12") (pinfunction "PH0-OSC_IN(PH0)_12") (pintype "passive"))
    )
    (net (code "101") (name "/off") (class "Default")
      (node (ref "P7") (pin "5") (pinfunction "5_5") (pintype "passive"))
      (node (ref "R143") (pin "2") (pinfunction "2_2") (pintype "passive"))
      (node (ref "R39") (pin "2") (pinfunction "2_2") (pintype "passive"))
      (node (ref "R42") (pin "2") (pinfunction "2_2") (pintype "passive"))
      (node (ref "R47") (pin "2") (pinfunction "2_2") (pintype "passive"))
    )
    (net (code "102") (name "/on{slash}Exp") (class "Default")
      (node (ref "P7") (pin "3") (pinfunction "3_3") (pintype "passive"))
      (node (ref "R27") (pin "2") (pinfunction "2_2") (pintype "passive"))
      (node (ref "R31") (pin "2") (pinfunction "2_2") (pintype "passive"))
      (node (ref "R36") (pin "2") (pinfunction "2_2") (pintype "passive"))
    )
    (net (code "103") (name "/origin") (class "Default")
      (node (ref "D85") (pin "2") (pinfunction "2_2") (pintype "passive"))
      (node (ref "D86") (pin "2") (pinfunction "K_2") (pintype "passive"))
      (node (ref "P22") (pin "2") (pinfunction "2_2") (pintype "passive"))
      (node (ref "U28") (pin "2") (pinfunction "2_2") (pintype "passive"))
    )
    (net (code "104") (name "3V3") (class "Default")
      (node (ref "C1") (pin "1") (pinfunction "1_1") (pintype "passive"))
      (node (ref "C15") (pin "1") (pinfunction "1_1") (pintype "passive"))
      (node (ref "C2") (pin "2") (pinfunction "2_2") (pintype "passive"))
      (node (ref "C25") (pin "2") (pinfunction "2_2") (pintype "passive"))
      (node (ref "C35") (pin "1") (pinfunction "1_1") (pintype "passive"))
      (node (ref "C37") (pin "2") (pinfunction "2_2") (pintype "passive"))
      (node (ref "C48") (pin "2") (pinfunction "2_2") (pintype "passive"))
      (node (ref "C5") (pin "1") (pintype "passive"))
      (node (ref "C60") (pin "1") (pinfunction "1_1") (pintype "passive"))
      (node (ref "C66") (pin "1") (pinfunction "1_1") (pintype "passive"))
      (node (ref "C67") (pin "1") (pinfunction "1_1") (pintype "passive"))
      (node (ref "C69") (pin "1") (pinfunction "1_1") (pintype "passive"))
      (node (ref "C7") (pin "2") (pinfunction "2_2") (pintype "passive"))
      (node (ref "C75") (pin "2") (pinfunction "2_2") (pintype "passive"))
      (node (ref "C8") (pin "2") (pinfunction "2_2") (pintype "passive"))
      (node (ref "C80") (pin "2") (pinfunction "2_2") (pintype "passive"))
      (node (ref "C81") (pin "2") (pinfunction "2_2") (pintype "passive"))
      (node (ref "C85") (pin "2") (pinfunction "2_2") (pintype "passive"))
      (node (ref "C86") (pin "2") (pinfunction "2_2") (pintype "passive"))
      (node (ref "C88") (pin "1") (pinfunction "1_1") (pintype "passive"))
      (node (ref "L10") (pin "1") (pinfunction "1_1") (pintype "passive"))
      (node (ref "P31") (pin "1") (pinfunction "1_1") (pintype "passive"))
      (node (ref "R102") (pin "2") (pinfunction "2_2") (pintype "passive"))
      (node (ref "R104") (pin "2") (pinfunction "2_2") (pintype "passive"))
      (node (ref "R106") (pin "2") (pinfunction "2_2") (pintype "passive"))
      (node (ref "R107") (pin "2") (pinfunction "2_2") (pintype "passive"))
      (node (ref "R108") (pin "2") (pinfunction "2_2") (pintype "passive"))
      (node (ref "R109") (pin "2") (pinfunction "2_2") (pintype "passive"))
      (node (ref "R111") (pin "2") (pinfunction "2_2") (pintype "passive"))
      (node (ref "R112") (pin "2") (pinfunction "2_2") (pintype "passive"))
      (node (ref "R115") (pin "1") (pinfunction "1_1") (pintype "passive"))
      (node (ref "R119") (pin "1") (pinfunction "1_1") (pintype "passive"))
      (node (ref "R122") (pin "1") (pinfunction "1_1") (pintype "passive"))
      (node (ref "R123") (pin "1") (pinfunction "1_1") (pintype "passive"))
      (node (ref "R126") (pin "2") (pinfunction "2_2") (pintype "passive"))
      (node (ref "R128") (pin "2") (pinfunction "2_2") (pintype "passive"))
      (node (ref "R130") (pin "1") (pinfunction "1_1") (pintype "passive"))
      (node (ref "R131") (pin "1") (pinfunction "1_1") (pintype "passive"))
      (node (ref "R133") (pin "2") (pinfunction "2_2") (pintype "passive"))
      (node (ref "R136") (pin "2") (pinfunction "2_2") (pintype "passive"))
      (node (ref "R139") (pin "1") (pinfunction "1_1") (pintype "passive"))
      (node (ref "R149") (pin "1") (pinfunction "1_1") (pintype "passive"))
      (node (ref "R150") (pin "1") (pinfunction "1_1") (pintype "passive"))
      (node (ref "R153") (pin "1") (pinfunction "1_1") (pintype "passive"))
      (node (ref "R156") (pin "2") (pinfunction "2_2") (pintype "passive"))
      (node (ref "R162") (pin "2") (pinfunction "2_2") (pintype "passive"))
      (node (ref "R169") (pin "1") (pinfunction "1_1") (pintype "passive"))
      (node (ref "R175") (pin "1") (pinfunction "1_1") (pintype "passive"))
      (node (ref "R182") (pin "2") (pinfunction "2_2") (pintype "passive"))
      (node (ref "R189") (pin "1") (pinfunction "1_1") (pintype "passive"))
      (node (ref "R190") (pin "1") (pinfunction "1_1") (pintype "passive"))
      (node (ref "R191") (pin "1") (pinfunction "1_1") (pintype "passive"))
      (node (ref "R192") (pin "1") (pinfunction "1_1") (pintype "passive"))
      (node (ref "R197") (pin "2") (pinfunction "2_2") (pintype "passive"))
      (node (ref "R198") (pin "2") (pinfunction "2_2") (pintype "passive"))
      (node (ref "R200") (pin "2") (pinfunction "2_2") (pintype "passive"))
      (node (ref "R203") (pin "1") (pinfunction "1_1") (pintype "passive"))
      (node (ref "R207") (pin "1") (pinfunction "1_1") (pintype "passive"))
      (node (ref "R28") (pin "2") (pinfunction "2_2") (pintype "passive"))
      (node (ref "R30") (pin "1") (pinfunction "1_1") (pintype "passive"))
      (node (ref "R33") (pin "1") (pinfunction "1_1") (pintype "passive"))
      (node (ref "R34") (pin "2") (pinfunction "2_2") (pintype "passive"))
      (node (ref "R37") (pin "2") (pinfunction "2_2") (pintype "passive"))
      (node (ref "R40") (pin "2") (pinfunction "2_2") (pintype "passive"))
      (node (ref "R41") (pin "1") (pinfunction "1_1") (pintype "passive"))
      (node (ref "R45") (pin "2") (pinfunction "2_2") (pintype "passive"))
      (node (ref "R46") (pin "2") (pinfunction "2_2") (pintype "passive"))
      (node (ref "R49") (pin "2") (pinfunction "2_2") (pintype "passive"))
      (node (ref "R71") (pin "2") (pinfunction "2_2") (pintype "passive"))
      (node (ref "R74") (pin "2") (pinfunction "2_2") (pintype "passive"))
      (node (ref "R76") (pin "2") (pinfunction "2_2") (pintype "passive"))
      (node (ref "R86") (pin "2") (pinfunction "2_2") (pintype "passive"))
      (node (ref "R88") (pin "2") (pinfunction "2_2") (pintype "passive"))
      (node (ref "R92") (pin "2") (pinfunction "2_2") (pintype "passive"))
      (node (ref "R99") (pin "2") (pinfunction "2_2") (pintype "passive"))
      (node (ref "TP4") (pin "1") (pinfunction "1_1") (pintype "passive"))
      (node (ref "U1") (pin "1") (pinfunction "VCC_1") (pintype "passive"))
      (node (ref "U1") (pin "5") (pinfunction "DE_5") (pintype "passive"))
      (node (ref "U14") (pin "4") (pinfunction "VCC_4") (pintype "passive"))
      (node (ref "U19") (pin "1") (pinfunction "VCC_1") (pintype "passive"))
      (node (ref "U2") (pin "1") (pinfunction "VCC_1") (pintype "passive"))
      (node (ref "U27") (pin "16") (pinfunction "VCC_16") (pintype "passive"))
      (node (ref "U27") (pin "4") (pinfunction "G_4") (pintype "passive"))
      (node (ref "U33") (pin "100") (pinfunction "VDD_100") (pintype "passive"))
      (node (ref "U33") (pin "11") (pinfunction "VDD_11") (pintype "passive"))
      (node (ref "U33") (pin "19") (pinfunction "VDD_19") (pintype "passive"))
      (node (ref "U33") (pin "28") (pinfunction "VDD_28") (pintype "passive"))
      (node (ref "U33") (pin "50") (pinfunction "VDD_50") (pintype "passive"))
      (node (ref "U33") (pin "6") (pinfunction "VBAT_6") (pintype "passive"))
      (node (ref "U33") (pin "75") (pinfunction "VDD_75") (pintype "passive"))
      (node (ref "U34") (pin "8") (pinfunction "8_8") (pintype "passive"))
      (node (ref "U5") (pin "1") (pinfunction "VCC_1") (pintype "passive"))
      (node (ref "U5") (pin "5") (pinfunction "DE_5") (pintype "passive"))
      (node (ref "U6") (pin "1") (pinfunction "VCC_1") (pintype "passive"))
      (node (ref "U7") (pin "2") (pinfunction "OUT_2") (pintype "passive"))
      (node (ref "U7") (pin "4") (pinfunction "OUT_4") (pintype "passive"))
      (node (ref "X1") (pin "1") (pinfunction "Tri-state_1") (pintype "passive"))
      (node (ref "X1") (pin "4") (pinfunction "VDD_4") (pintype "passive"))
    )
    (net (code "105") (name "5V") (class "Default")
      (node (ref "B1") (pin "2") (pinfunction "2_2") (pintype "passive"))
      (node (ref "C18") (pin "1") (pinfunction "1_1") (pintype "passive"))
      (node (ref "C19") (pin "2") (pinfunction "2_2") (pintype "passive"))
      (node (ref "C24") (pin "1") (pinfunction "1_1") (pintype "passive"))
      (node (ref "C62") (pin "1") (pinfunction "1_1") (pintype "passive"))
      (node (ref "C64") (pin "1") (pinfunction "1_1") (pintype "passive"))
      (node (ref "C87") (pin "2") (pinfunction "2_2") (pintype "passive"))
      (node (ref "C92") (pin "1") (pinfunction "1_1") (pintype "passive"))
      (node (ref "C95") (pin "2") (pinfunction "2_2") (pintype "passive"))
      (node (ref "D111") (pin "1") (pinfunction "1_1") (pintype "passive"))
      (node (ref "L3") (pin "2") (pinfunction "2_2") (pintype "passive"))
      (node (ref "P20") (pin "3") (pinfunction "3_3") (pintype "passive"))
      (node (ref "Q6") (pin "2") (pinfunction "S_2") (pintype "passive"))
      (node (ref "R100") (pin "2") (pinfunction "2_2") (pintype "passive"))
      (node (ref "R103") (pin "1") (pinfunction "1_1") (pintype "passive"))
      (node (ref "R15") (pin "2") (pinfunction "2_2") (pintype "passive"))
      (node (ref "R165") (pin "2") (pinfunction "2_2") (pintype "passive"))
      (node (ref "R168") (pin "2") (pinfunction "2_2") (pintype "passive"))
      (node (ref "R171") (pin "2") (pinfunction "2_2") (pintype "passive"))
      (node (ref "R174") (pin "2") (pinfunction "2_2") (pintype "passive"))
      (node (ref "R184") (pin "1") (pinfunction "1_1") (pintype "passive"))
      (node (ref "R202") (pin "2") (pinfunction "2_2") (pintype "passive"))
      (node (ref "R204") (pin "2") (pinfunction "2_2") (pintype "passive"))
      (node (ref "R205") (pin "2") (pinfunction "2_2") (pintype "passive"))
      (node (ref "R206") (pin "2") (pinfunction "2_2") (pintype "passive"))
      (node (ref "R208") (pin "2") (pinfunction "2_2") (pintype "passive"))
      (node (ref "R209") (pin "2") (pinfunction "2_2") (pintype "passive"))
      (node (ref "TP3") (pin "1") (pinfunction "1_1") (pintype "passive"))
      (node (ref "U29") (pin "5") (pinfunction "VCC_5") (pintype "passive"))
      (node (ref "U31") (pin "5") (pinfunction "VCC_5") (pintype "passive"))
      (node (ref "U35") (pin "4") (pinfunction "4_4") (pintype "passive"))
      (node (ref "U4") (pin "4") (pinfunction "FB_4") (pintype "passive"))
      (node (ref "U7") (pin "3") (pinfunction "IN_3") (pintype "passive"))
    )
    (net (code "106") (name "12V") (class "Default")
      (node (ref "C12") (pin "2") (pinfunction "2_2") (pintype "passive"))
      (node (ref "C13") (pin "1") (pinfunction "1_1") (pintype "passive"))
      (node (ref "L2") (pin "2") (pinfunction "2_2") (pintype "passive"))
      (node (ref "P15") (pin "1") (pinfunction "1_1") (pintype "passive"))
      (node (ref "TP2") (pin "1") (pinfunction "1_1") (pintype "passive"))
      (node (ref "U3") (pin "4") (pinfunction "FEEDBACK_4") (pintype "passive"))
    )
    (net (code "107") (name "24V") (class "Default")
      (node (ref "C10") (pin "1") (pinfunction "1_1") (pintype "passive"))
      (node (ref "C11") (pin "1") (pinfunction "1_1") (pintype "passive"))
      (node (ref "C17") (pin "1") (pinfunction "1_1") (pintype "passive"))
      (node (ref "C20") (pin "1") (pinfunction "1_1") (pintype "passive"))
      (node (ref "F1") (pin "1") (pinfunction "1_1") (pintype "passive"))
      (node (ref "F2") (pin "2") (pinfunction "2_2") (pintype "passive"))
      (node (ref "P21") (pin "7") (pinfunction "7_7") (pintype "passive"))
      (node (ref "P22") (pin "1") (pinfunction "1_1") (pintype "passive"))
      (node (ref "P25") (pin "1") (pinfunction "1_1") (pintype "passive"))
      (node (ref "P26") (pin "1") (pinfunction "1_1") (pintype "passive"))
      (node (ref "P27") (pin "1") (pinfunction "1_1") (pintype "passive"))
      (node (ref "P28") (pin "1") (pinfunction "1_1") (pintype "passive"))
      (node (ref "P7") (pin "1") (pinfunction "1_1") (pintype "passive"))
      (node (ref "P7") (pin "10") (pinfunction "10_10") (pintype "passive"))
      (node (ref "P7") (pin "2") (pinfunction "2_2") (pintype "passive"))
      (node (ref "P7") (pin "4") (pinfunction "4_4") (pintype "passive"))
      (node (ref "Q10") (pin "2") (pinfunction "E_2") (pintype "passive"))
      (node (ref "Q2") (pin "2") (pinfunction "S_2") (pintype "passive"))
      (node (ref "Q4") (pin "2") (pinfunction "E_2") (pintype "passive"))
      (node (ref "Q5") (pin "2") (pinfunction "E_2") (pintype "passive"))
      (node (ref "Q9") (pin "2") (pinfunction "E_2") (pintype "passive"))
      (node (ref "R1") (pin "2") (pinfunction "2_2") (pintype "passive"))
      (node (ref "R113") (pin "2") (pinfunction "2_2") (pintype "passive"))
      (node (ref "R114") (pin "2") (pinfunction "2_2") (pintype "passive"))
      (node (ref "R116") (pin "2") (pinfunction "2_2") (pintype "passive"))
      (node (ref "R117") (pin "2") (pinfunction "2_2") (pintype "passive"))
      (node (ref "R118") (pin "2") (pinfunction "2_2") (pintype "passive"))
      (node (ref "R120") (pin "2") (pinfunction "2_2") (pintype "passive"))
      (node (ref "R121") (pin "2") (pinfunction "2_2") (pintype "passive"))
      (node (ref "R124") (pin "2") (pinfunction "2_2") (pintype "passive"))
      (node (ref "R125") (pin "1") (pinfunction "1_1") (pintype "passive"))
      (node (ref "R127") (pin "2") (pinfunction "2_2") (pintype "passive"))
      (node (ref "R129") (pin "2") (pinfunction "2_2") (pintype "passive"))
      (node (ref "R132") (pin "2") (pinfunction "2_2") (pintype "passive"))
      (node (ref "R134") (pin "2") (pinfunction "2_2") (pintype "passive"))
      (node (ref "R135") (pin "1") (pinfunction "1_1") (pintype "passive"))
      (node (ref "R138") (pin "2") (pinfunction "2_2") (pintype "passive"))
      (node (ref "R140") (pin "2") (pinfunction "2_2") (pintype "passive"))
      (node (ref "R141") (pin "2") (pinfunction "2_2") (pintype "passive"))
      (node (ref "R145") (pin "2") (pinfunction "2_2") (pintype "passive"))
      (node (ref "R148") (pin "2") (pinfunction "2_2") (pintype "passive"))
      (node (ref "R151") (pin "2") (pinfunction "2_2") (pintype "passive"))
      (node (ref "R157") (pin "2") (pinfunction "2_2") (pintype "passive"))
      (node (ref "R158") (pin "2") (pinfunction "2_2") (pintype "passive"))
      (node (ref "R32") (pin "1") (pinfunction "1_1") (pintype "passive"))
      (node (ref "R44") (pin "1") (pinfunction "1_1") (pintype "passive"))
      (node (ref "R51") (pin "1") (pinfunction "1_1") (pintype "passive"))
      (node (ref "R52") (pin "2") (pinfunction "2_2") (pintype "passive"))
      (node (ref "R75") (pin "1") (pinfunction "1_1") (pintype "passive"))
      (node (ref "R77") (pin "1") (pinfunction "1_1") (pintype "passive"))
      (node (ref "R89") (pin "1") (pinfunction "1_1") (pintype "passive"))
      (node (ref "R90") (pin "1") (pinfunction "1_1") (pintype "passive"))
      (node (ref "U25") (pin "4") (pinfunction "4_4") (pintype "passive"))
      (node (ref "U3") (pin "1") (pinfunction "VIN_1") (pintype "passive"))
      (node (ref "U4") (pin "7") (pinfunction "VIN_7") (pintype "passive"))
    )
    (net (code "108") (name "24V_IN") (class "Default")
      (node (ref "C3") (pin "1") (pinfunction "1_1") (pintype "passive"))
      (node (ref "C4") (pin "1") (pinfunction "1_1") (pintype "passive"))
      (node (ref "D1") (pin "1") (pinfunction "K_1") (pintype "passive"))
      (node (ref "F1") (pin "2") (pinfunction "2_2") (pintype "passive"))
      (node (ref "P2") (pin "1") (pinfunction "1_1") (pintype "passive"))
    )
    (net (code "109") (name "AGND_M") (class "Default")
      (node (ref "D47") (pin "2") (pinfunction "2_2") (pintype "passive"))
      (node (ref "P13") (pin "2") (pinfunction "2_2") (pintype "passive"))
      (node (ref "P14") (pin "2") (pinfunction "2_2") (pintype "passive"))
      (node (ref "P6") (pin "2") (pinfunction "2_2") (pintype "passive"))
    )
    (net (code "110") (name "CANG_1") (class "Default")
      (node (ref "C6") (pin "2") (pinfunction "2_2") (pintype "passive"))
      (node (ref "C9") (pin "2") (pinfunction "2_2") (pintype "passive"))
      (node (ref "P1") (pin "3") (pinfunction "3_3") (pintype "passive"))
      (node (ref "TVS3") (pin "3") (pinfunction "3_3") (pintype "passive"))
      (node (ref "U2") (pin "8") (pinfunction "CANG_8") (pintype "passive"))
    )
    (net (code "111") (name "CANG_2") (class "Default")
      (node (ref "C22") (pin "2") (pinfunction "2_2") (pintype "passive"))
      (node (ref "C27") (pin "2") (pinfunction "2_2") (pintype "passive"))
      (node (ref "P4") (pin "3") (pinfunction "3_3") (pintype "passive"))
      (node (ref "TVS2") (pin "3") (pinfunction "3_3") (pintype "passive"))
      (node (ref "U6") (pin "8") (pinfunction "CANG_8") (pintype "passive"))
    )
    (net (code "112") (name "GND") (class "Default")
      (node (ref "C1") (pin "2") (pinfunction "2_2") (pintype "passive"))
      (node (ref "C10") (pin "2") (pinfunction "2_2") (pintype "passive"))
      (node (ref "C11") (pin "2") (pinfunction "2_2") (pintype "passive"))
      (node (ref "C12") (pin "1") (pinfunction "1_1") (pintype "passive"))
      (node (ref "C13") (pin "2") (pinfunction "2_2") (pintype "passive"))
      (node (ref "C15") (pin "2") (pinfunction "2_2") (pintype "passive"))
      (node (ref "C17") (pin "2") (pinfunction "2_2") (pintype "passive"))
      (node (ref "C18") (pin "2") (pinfunction "2_2") (pintype "passive"))
      (node (ref "C19") (pin "1") (pinfunction "1_1") (pintype "passive"))
      (node (ref "C2") (pin "1") (pinfunction "1_1") (pintype "passive"))
      (node (ref "C20") (pin "2") (pinfunction "2_2") (pintype "passive"))
      (node (ref "C24") (pin "2") (pinfunction "2_2") (pintype "passive"))
      (node (ref "C25") (pin "1") (pinfunction "1_1") (pintype "passive"))
      (node (ref "C29") (pin "1") (pinfunction "1_1") (pintype "passive"))
      (node (ref "C3") (pin "2") (pinfunction "2_2") (pintype "passive"))
      (node (ref "C31") (pin "1") (pinfunction "1_1") (pintype "passive"))
      (node (ref "C32") (pin "1") (pinfunction "1_1") (pintype "passive"))
      (node (ref "C34") (pin "2") (pinfunction "2_2") (pintype "passive"))
      (node (ref "C35") (pin "2") (pinfunction "2_2") (pintype "passive"))
      (node (ref "C37") (pin "1") (pinfunction "1_1") (pintype "passive"))
      (node (ref "C4") (pin "2") (pinfunction "2_2") (pintype "passive"))
      (node (ref "C41") (pin "1") (pinfunction "1_1") (pintype "passive"))
      (node (ref "C46") (pin "1") (pinfunction "1_1") (pintype "passive"))
      (node (ref "C47") (pin "1") (pinfunction "1_1") (pintype "passive"))
      (node (ref "C48") (pin "1") (pinfunction "1_1") (pintype "passive"))
      (node (ref "C5") (pin "2") (pintype "passive"))
      (node (ref "C50") (pin "1") (pinfunction "1_1") (pintype "passive"))
      (node (ref "C51") (pin "1") (pinfunction "1_1") (pintype "passive"))
      (node (ref "C52") (pin "1") (pinfunction "1_1") (pintype "passive"))
      (node (ref "C53") (pin "1") (pinfunction "1_1") (pintype "passive"))
      (node (ref "C54") (pin "1") (pinfunction "1_1") (pintype "passive"))
      (node (ref "C55") (pin "1") (pinfunction "1_1") (pintype "passive"))
      (node (ref "C56") (pin "1") (pinfunction "1_1") (pintype "passive"))
      (node (ref "C57") (pin "1") (pinfunction "1_1") (pintype "passive"))
      (node (ref "C58") (pin "1") (pinfunction "1_1") (pintype "passive"))
      (node (ref "C59") (pin "1") (pinfunction "1_1") (pintype "passive"))
      (node (ref "C60") (pin "2") (pinfunction "2_2") (pintype "passive"))
      (node (ref "C61") (pin "1") (pinfunction "1_1") (pintype "passive"))
      (node (ref "C62") (pin "2") (pinfunction "2_2") (pintype "passive"))
      (node (ref "C63") (pin "1") (pinfunction "1_1") (pintype "passive"))
      (node (ref "C64") (pin "2") (pinfunction "2_2") (pintype "passive"))
      (node (ref "C65") (pin "1") (pinfunction "1_1") (pintype "passive"))
      (node (ref "C66") (pin "2") (pinfunction "2_2") (pintype "passive"))
      (node (ref "C67") (pin "2") (pinfunction "2_2") (pintype "passive"))
      (node (ref "C69") (pin "2") (pinfunction "2_2") (pintype "passive"))
      (node (ref "C7") (pin "1") (pinfunction "1_1") (pintype "passive"))
      (node (ref "C75") (pin "1") (pinfunction "1_1") (pintype "passive"))
      (node (ref "C8") (pin "1") (pinfunction "1_1") (pintype "passive"))
      (node (ref "C80") (pin "1") (pinfunction "1_1") (pintype "passive"))
      (node (ref "C81") (pin "1") (pinfunction "1_1") (pintype "passive"))
      (node (ref "C82") (pin "2") (pinfunction "2_2") (pintype "passive"))
      (node (ref "C83") (pin "1") (pinfunction "1_1") (pintype "passive"))
      (node (ref "C84") (pin "1") (pinfunction "1_1") (pintype "passive"))
      (node (ref "C85") (pin "1") (pinfunction "1_1") (pintype "passive"))
      (node (ref "C86") (pin "1") (pinfunction "1_1") (pintype "passive"))
      (node (ref "C87") (pin "1") (pinfunction "1_1") (pintype "passive"))
      (node (ref "C88") (pin "2") (pinfunction "2_2") (pintype "passive"))
      (node (ref "C90") (pin "2") (pinfunction "2_2") (pintype "passive"))
      (node (ref "C91") (pin "2") (pinfunction "2_2") (pintype "passive"))
      (node (ref "C92") (pin "2") (pinfunction "2_2") (pintype "passive"))
      (node (ref "C93") (pin "1") (pinfunction "1_1") (pintype "passive"))
      (node (ref "C94") (pin "1") (pinfunction "1_1") (pintype "passive"))
      (node (ref "C95") (pin "1") (pinfunction "1_1") (pintype "passive"))
      (node (ref "D1") (pin "2") (pinfunction "A_2") (pintype "passive"))
      (node (ref "D10") (pin "2") (pinfunction "2_2") (pintype "passive"))
      (node (ref "D100") (pin "2") (pinfunction "2_2") (pintype "passive"))
      (node (ref "D101") (pin "2") (pinfunction "2_2") (pintype "passive"))
      (node (ref "D16") (pin "2") (pinfunction "2_2") (pintype "passive"))
      (node (ref "D18") (pin "2") (pinfunction "2_2") (pintype "passive"))
      (node (ref "D19") (pin "2") (pinfunction "K_2") (pintype "passive"))
      (node (ref "D21") (pin "2") (pinfunction "K_2") (pintype "passive"))
      (node (ref "D22") (pin "2") (pinfunction "2_2") (pintype "passive"))
      (node (ref "D24") (pin "2") (pinfunction "K_2") (pintype "passive"))
      (node (ref "D25") (pin "2") (pinfunction "2_2") (pintype "passive"))
      (node (ref "D28") (pin "2") (pinfunction "K_2") (pintype "passive"))
      (node (ref "D35") (pin "1") (pinfunction "1_1") (pintype "passive"))
      (node (ref "D36") (pin "1") (pinfunction "1_1") (pintype "passive"))
      (node (ref "D4") (pin "2") (pinfunction "K_2") (pintype "passive"))
      (node (ref "D46") (pin "2") (pinfunction "2_2") (pintype "passive"))
      (node (ref "D48") (pin "2") (pinfunction "K_2") (pintype "passive"))
      (node (ref "D56") (pin "2") (pinfunction "2_2") (pintype "passive"))
      (node (ref "D58") (pin "2") (pinfunction "K_2") (pintype "passive"))
      (node (ref "D61") (pin "1") (pinfunction "1_1") (pintype "passive"))
      (node (ref "D63") (pin "1") (pinfunction "1_1") (pintype "passive"))
      (node (ref "D8") (pin "2") (pinfunction "2_2") (pintype "passive"))
      (node (ref "D9") (pin "2") (pinfunction "K_2") (pintype "passive"))
      (node (ref "D95") (pin "2") (pinfunction "2_2") (pintype "passive"))
      (node (ref "D96") (pin "2") (pinfunction "K_2") (pintype "passive"))
      (node (ref "D99") (pin "2") (pinfunction "2_2") (pintype "passive"))
      (node (ref "K1") (pin "8") (pinfunction "8_8") (pintype "passive"))
      (node (ref "L9") (pin "1") (pinfunction "1_1") (pintype "passive"))
      (node (ref "P10") (pin "2") (pinfunction "2_2") (pintype "passive"))
      (node (ref "P15") (pin "4") (pinfunction "4_4") (pintype "passive"))
      (node (ref "P16") (pin "2") (pinfunction "2_2") (pintype "passive"))
      (node (ref "P17") (pin "2") (pinfunction "2_2") (pintype "passive"))
      (node (ref "P18") (pin "2") (pinfunction "2_2") (pintype "passive"))
      (node (ref "P19") (pin "6") (pinfunction "1_6") (pintype "passive"))
      (node (ref "P2") (pin "2") (pinfunction "2_2") (pintype "passive"))
      (node (ref "P21") (pin "4") (pinfunction "4_4") (pintype "passive"))
      (node (ref "P22") (pin "3") (pinfunction "3_3") (pintype "passive"))
      (node (ref "P23") (pin "5") (pinfunction "5_5") (pintype "passive"))
      (node (ref "P24") (pin "2") (pinfunction "2_2") (pintype "passive"))
      (node (ref "P25") (pin "3") (pinfunction "3_3") (pintype "passive"))
      (node (ref "P26") (pin "3") (pinfunction "3_3") (pintype "passive"))
      (node (ref "P27") (pin "3") (pinfunction "3_3") (pintype "passive"))
      (node (ref "P28") (pin "3") (pinfunction "3_3") (pintype "passive"))
      (node (ref "P29") (pin "3") (pinfunction "3_3") (pintype "passive"))
      (node (ref "P30") (pin "1") (pinfunction "1_1") (pintype "passive"))
      (node (ref "P31") (pin "4") (pinfunction "4_4") (pintype "passive"))
      (node (ref "P32") (pin "4") (pinfunction "4_4") (pintype "passive"))
      (node (ref "P32") (pin "6") (pinfunction "6_6") (pintype "passive"))
      (node (ref "P32") (pin "7") (pinfunction "7_7") (pintype "passive"))
      (node (ref "P7") (pin "15") (pinfunction "15_15") (pintype "passive"))
      (node (ref "P7") (pin "16") (pinfunction "16_16") (pintype "passive"))
      (node (ref "P9") (pin "2") (pinfunction "2_2") (pintype "passive"))
      (node (ref "Q12") (pin "2") (pinfunction "E_2") (pintype "passive"))
      (node (ref "Q14") (pin "2") (pinfunction "E_2") (pintype "passive"))
      (node (ref "Q20") (pin "2") (pinfunction "E_2") (pintype "passive"))
      (node (ref "Q3") (pin "2") (pinfunction "E_2") (pintype "passive"))
      (node (ref "Q8") (pin "2") (pinfunction "E_2") (pintype "passive"))
      (node (ref "R142") (pin "1") (pinfunction "1_1") (pintype "passive"))
      (node (ref "R144") (pin "1") (pinfunction "1_1") (pintype "passive"))
      (node (ref "R147") (pin "1") (pinfunction "1_1") (pintype "passive"))
      (node (ref "R154") (pin "1") (pinfunction "1_1") (pintype "passive"))
      (node (ref "R179") (pin "2") (pinfunction "2_2") (pintype "passive"))
      (node (ref "R181") (pin "2") (pinfunction "2_2") (pintype "passive"))
      (node (ref "R193") (pin "1") (pinfunction "1_1") (pintype "passive"))
      (node (ref "R194") (pin "2") (pinfunction "2_2") (pintype "passive"))
      (node (ref "R199") (pin "1") (pinfunction "1_1") (pintype "passive"))
      (node (ref "R55") (pin "2") (pinfunction "2_2") (pintype "passive"))
      (node (ref "T1") (pin "1") (pinfunction "1_1") (pintype "passive"))
      (node (ref "TP5") (pin "1") (pinfunction "1_1") (pintype "passive"))
      (node (ref "U1") (pin "2") (pinfunction "GND_2") (pintype "passive"))
      (node (ref "U1") (pin "6") (pinfunction "RE_6") (pintype "passive"))
      (node (ref "U10") (pin "2") (pinfunction "2_2") (pintype "passive"))
      (node (ref "U10") (pin "3") (pinfunction "3_3") (pintype "passive"))
      (node (ref "U11") (pin "2") (pinfunction "2_2") (pintype "passive"))
      (node (ref "U11") (pin "3") (pinfunction "3_3") (pintype "passive"))
      (node (ref "U13") (pin "2") (pinfunction "2_2") (pintype "passive"))
      (node (ref "U13") (pin "3") (pinfunction "3_3") (pintype "passive"))
      (node (ref "U14") (pin "3") (pinfunction "GND_3") (pintype "passive"))
      (node (ref "U17") (pin "3") (pinfunction "3_3") (pintype "passive"))
      (node (ref "U18") (pin "3") (pinfunction "3_3") (pintype "passive"))
      (node (ref "U19") (pin "2") (pinfunction "GND_2") (pintype "passive"))
      (node (ref "U19") (pin "5") (pinfunction "RGND_5") (pintype "passive"))
      (node (ref "U2") (pin "2") (pinfunction "GND_2") (pintype "passive"))
      (node (ref "U20") (pin "3") (pinfunction "3_3") (pintype "passive"))
      (node (ref "U21") (pin "11") (pinfunction "EM3_11") (pintype "passive"))
      (node (ref "U21") (pin "13") (pinfunction "EM2_13") (pintype "passive"))
      (node (ref "U21") (pin "15") (pinfunction "EM1_15") (pintype "passive"))
      (node (ref "U21") (pin "9") (pinfunction "EM4_9") (pintype "passive"))
      (node (ref "U22") (pin "3") (pinfunction "3_3") (pintype "passive"))
      (node (ref "U23") (pin "3") (pinfunction "3_3") (pintype "passive"))
      (node (ref "U24") (pin "3") (pinfunction "3_3") (pintype "passive"))
      (node (ref "U26") (pin "3") (pinfunction "3_3") (pintype "passive"))
      (node (ref "U27") (pin "12") (pinfunction "G#_12") (pintype "passive"))
      (node (ref "U27") (pin "8") (pinfunction "GND_8") (pintype "passive"))
      (node (ref "U28") (pin "3") (pinfunction "3_3") (pintype "passive"))
      (node (ref "U29") (pin "3") (pinfunction "GND_3") (pintype "passive"))
      (node (ref "U3") (pin "3") (pinfunction "GND_3") (pintype "passive"))
      (node (ref "U3") (pin "5") (pinfunction "ON/OFF_5") (pintype "passive"))
      (node (ref "U30") (pin "3") (pinfunction "3_3") (pintype "passive"))
      (node (ref "U31") (pin "3") (pinfunction "GND_3") (pintype "passive"))
      (node (ref "U32") (pin "2") (pinfunction "2_2") (pintype "passive"))
      (node (ref "U32") (pin "3") (pinfunction "3_3") (pintype "passive"))
      (node (ref "U33") (pin "10") (pinfunction "VSS_10") (pintype "passive"))
      (node (ref "U33") (pin "27") (pinfunction "VSS_27") (pintype "passive"))
      (node (ref "U33") (pin "74") (pinfunction "VSS_74") (pintype "passive"))
      (node (ref "U33") (pin "99") (pinfunction "VSS_99") (pintype "passive"))
      (node (ref "U34") (pin "1") (pinfunction "1_1") (pintype "passive"))
      (node (ref "U34") (pin "2") (pinfunction "2_2") (pintype "passive"))
      (node (ref "U34") (pin "3") (pinfunction "3_3") (pintype "passive"))
      (node (ref "U34") (pin "4") (pinfunction "4_4") (pintype "passive"))
      (node (ref "U34") (pin "7") (pinfunction "7_7") (pintype "passive"))
      (node (ref "U36") (pin "3") (pinfunction "3_3") (pintype "passive"))
      (node (ref "U37") (pin "3") (pinfunction "3_3") (pintype "passive"))
      (node (ref "U4") (pin "6") (pinfunction "GND_6") (pintype "passive"))
      (node (ref "U5") (pin "2") (pinfunction "GND_2") (pintype "passive"))
      (node (ref "U5") (pin "6") (pinfunction "RE_6") (pintype "passive"))
      (node (ref "U6") (pin "2") (pinfunction "GND_2") (pintype "passive"))
      (node (ref "U7") (pin "1") (pinfunction "ADJ/GND_1") (pintype "passive"))
      (node (ref "U8") (pin "2") (pinfunction "2_2") (pintype "passive"))
      (node (ref "U8") (pin "3") (pinfunction "3_3") (pintype "passive"))
      (node (ref "X1") (pin "2") (pinfunction "GND_2") (pintype "passive"))
    )
    (net (code "113") (name "GND_422_1") (class "Default")
      (node (ref "D15") (pin "2") (pinfunction "2_2") (pintype "passive"))
      (node (ref "D29") (pin "2") (pinfunction "2_2") (pintype "passive"))
      (node (ref "D31") (pin "3") (pinfunction "3_3") (pintype "passive"))
      (node (ref "D32") (pin "3") (pinfunction "3_3") (pintype "passive"))
      (node (ref "D33") (pin "2") (pinfunction "2_2") (pintype "passive"))
      (node (ref "D34") (pin "2") (pinfunction "2_2") (pintype "passive"))
      (node (ref "P11") (pin "5") (pinfunction "5_5") (pintype "passive"))
      (node (ref "U5") (pin "7") (pinfunction "RGND_7") (pintype "passive"))
    )
    (net (code "114") (name "GND_422_2") (class "Default")
      (node (ref "D11") (pin "2") (pinfunction "2_2") (pintype "passive"))
      (node (ref "D12") (pin "2") (pinfunction "2_2") (pintype "passive"))
      (node (ref "D14") (pin "2") (pinfunction "2_2") (pintype "passive"))
      (node (ref "D2") (pin "3") (pinfunction "3_3") (pintype "passive"))
      (node (ref "D3") (pin "3") (pinfunction "3_3") (pintype "passive"))
      (node (ref "D7") (pin "2") (pinfunction "2_2") (pintype "passive"))
      (node (ref "P34") (pin "5") (pinfunction "5_5") (pintype "passive"))
      (node (ref "U1") (pin "7") (pinfunction "RGND_7") (pintype "passive"))
    )
    (net (code "115") (name "GND_485") (class "Default")
      (node (ref "C36") (pin "1") (pinfunction "1_1") (pintype "passive"))
      (node (ref "C40") (pin "1") (pinfunction "1_1") (pintype "passive"))
      (node (ref "D30") (pin "3") (pinfunction "3_3") (pintype "passive"))
      (node (ref "D5") (pin "2") (pinfunction "2_2") (pintype "passive"))
      (node (ref "D6") (pin "2") (pinfunction "2_2") (pintype "passive"))
      (node (ref "P12") (pin "3") (pinfunction "3_3") (pintype "passive"))
      (node (ref "R67") (pin "2") (pinfunction "2_2") (pintype "passive"))
      (node (ref "U14") (pin "5") (pinfunction "RGND_5") (pintype "passive"))
    )
    (net (code "116") (name "Net-(C41-Pad2)") (class "Default")
      (node (ref "C41") (pin "2") (pinfunction "2_2") (pintype "passive"))
      (node (ref "R75") (pin "2") (pinfunction "2_2") (pintype "passive"))
      (node (ref "R78") (pin "2") (pinfunction "2_2") (pintype "passive"))
      (node (ref "U17") (pin "4") (pinfunction "4_4") (pintype "passive"))
    )
    (net (code "117") (name "Net-(C47-Pad2)") (class "Default")
      (node (ref "C47") (pin "2") (pinfunction "2_2") (pintype "passive"))
      (node (ref "R89") (pin "2") (pinfunction "2_2") (pintype "passive"))
      (node (ref "R93") (pin "2") (pinfunction "2_2") (pintype "passive"))
      (node (ref "U18") (pin "4") (pinfunction "4_4") (pintype "passive"))
    )
    (net (code "118") (name "Net-(C51-Pad2)") (class "Default")
      (node (ref "C51") (pin "2") (pinfunction "2_2") (pintype "passive"))
      (node (ref "R101") (pin "2") (pinfunction "2_2") (pintype "passive"))
      (node (ref "R103") (pin "2") (pinfunction "2_2") (pintype "passive"))
      (node (ref "U20") (pin "4") (pinfunction "4_4") (pintype "passive"))
    )
    (net (code "119") (name "Net-(D4-A)") (class "Default")
      (node (ref "D4") (pin "1") (pinfunction "A_1") (pintype "passive"))
      (node (ref "R1") (pin "1") (pinfunction "1_1") (pintype "passive"))
    )
    (net (code "120") (name "Net-(D9-A)") (class "Default")
      (node (ref "D9") (pin "1") (pinfunction "A_1") (pintype "passive"))
      (node (ref "R15") (pin "1") (pinfunction "1_1") (pintype "passive"))
    )
    (net (code "121") (name "Net-(D16-Pad1)") (class "Default")
      (node (ref "D16") (pin "1") (pinfunction "1_1") (pintype "passive"))
      (node (ref "R27") (pin "1") (pinfunction "1_1") (pintype "passive"))
      (node (ref "R31") (pin "1") (pinfunction "1_1") (pintype "passive"))
      (node (ref "U8") (pin "1") (pinfunction "1_1") (pintype "passive"))
    )
    (net (code "122") (name "Net-(D18-Pad1)") (class "Default")
      (node (ref "D18") (pin "1") (pinfunction "1_1") (pintype "passive"))
      (node (ref "R29") (pin "1") (pinfunction "1_1") (pintype "passive"))
      (node (ref "R35") (pin "1") (pinfunction "1_1") (pintype "passive"))
      (node (ref "U10") (pin "1") (pinfunction "1_1") (pintype "passive"))
    )
    (net (code "123") (name "Net-(D19-A)") (class "Default")
      (node (ref "D19") (pin "1") (pinfunction "A_1") (pintype "passive"))
      (node (ref "R36") (pin "1") (pinfunction "1_1") (pintype "passive"))
    )
    (net (code "124") (name "Net-(D20-A)") (class "Default")
      (node (ref "D20") (pin "1") (pinfunction "A_1") (pintype "passive"))
      (node (ref "R37") (pin "1") (pinfunction "1_1") (pintype "passive"))
    )
    (net (code "125") (name "Net-(D21-A)") (class "Default")
      (node (ref "D21") (pin "1") (pinfunction "A_1") (pintype "passive"))
      (node (ref "R38") (pin "1") (pinfunction "1_1") (pintype "passive"))
    )
    (net (code "126") (name "Net-(D22-Pad1)") (class "Default")
      (node (ref "D22") (pin "1") (pinfunction "1_1") (pintype "passive"))
      (node (ref "R39") (pin "1") (pinfunction "1_1") (pintype "passive"))
      (node (ref "R42") (pin "1") (pinfunction "1_1") (pintype "passive"))
      (node (ref "U11") (pin "1") (pinfunction "1_1") (pintype "passive"))
    )
    (net (code "127") (name "Net-(D23-Pad1)") (class "Default")
      (node (ref "D23") (pin "1") (pinfunction "1_1") (pintype "passive"))
      (node (ref "R40") (pin "1") (pinfunction "1_1") (pintype "passive"))
      (node (ref "R45") (pin "1") (pinfunction "1_1") (pintype "passive"))
      (node (ref "U12") (pin "1") (pinfunction "1_1") (pintype "passive"))
    )
    (net (code "128") (name "Net-(D24-A)") (class "Default")
      (node (ref "D24") (pin "1") (pinfunction "A_1") (pintype "passive"))
      (node (ref "R47") (pin "1") (pinfunction "1_1") (pintype "passive"))
    )
    (net (code "129") (name "Net-(D25-Pad1)") (class "Default")
      (node (ref "D25") (pin "1") (pinfunction "1_1") (pintype "passive"))
      (node (ref "R43") (pin "2") (pinfunction "2_2") (pintype "passive"))
      (node (ref "R48") (pin "2") (pinfunction "2_2") (pintype "passive"))
      (node (ref "U13") (pin "1") (pinfunction "1_1") (pintype "passive"))
    )
    (net (code "130") (name "Net-(D26-A)") (class "Default")
      (node (ref "D26") (pin "1") (pinfunction "A_1") (pintype "passive"))
      (node (ref "R49") (pin "1") (pinfunction "1_1") (pintype "passive"))
    )
    (net (code "131") (name "Net-(D28-A)") (class "Default")
      (node (ref "D28") (pin "1") (pinfunction "A_1") (pintype "passive"))
      (node (ref "R56") (pin "1") (pinfunction "1_1") (pintype "passive"))
    )
    (net (code "132") (name "Net-(D40-Pad1)") (class "Default")
      (node (ref "D40") (pin "1") (pinfunction "1_1") (pintype "passive"))
      (node (ref "R71") (pin "1") (pinfunction "1_1") (pintype "passive"))
      (node (ref "R74") (pin "1") (pinfunction "1_1") (pintype "passive"))
      (node (ref "U17") (pin "1") (pinfunction "1_1") (pintype "passive"))
    )
    (net (code "133") (name "Net-(D41-A)") (class "Default")
      (node (ref "D41") (pin "1") (pinfunction "A_1") (pintype "passive"))
      (node (ref "R76") (pin "1") (pinfunction "1_1") (pintype "passive"))
    )
    (net (code "134") (name "Net-(D47-Pad1)") (class "Default")
      (node (ref "D47") (pin "1") (pinfunction "1_1") (pintype "passive"))
      (node (ref "K1") (pin "4") (pinfunction "4_4") (pintype "passive"))
      (node (ref "K1") (pin "5") (pinfunction "5_5") (pintype "passive"))
      (node (ref "P13") (pin "1") (pinfunction "1_1") (pintype "passive"))
    )
    (net (code "135") (name "Net-(D48-A)") (class "Default")
      (node (ref "D48") (pin "1") (pinfunction "A_1") (pintype "passive"))
      (node (ref "R83") (pin "1") (pinfunction "1_1") (pintype "passive"))
    )
    (net (code "136") (name "Net-(D54-Pad1)") (class "Default")
      (node (ref "D54") (pin "1") (pinfunction "1_1") (pintype "passive"))
      (node (ref "R86") (pin "1") (pinfunction "1_1") (pintype "passive"))
      (node (ref "R88") (pin "1") (pinfunction "1_1") (pintype "passive"))
      (node (ref "U18") (pin "1") (pinfunction "1_1") (pintype "passive"))
    )
    (net (code "137") (name "Net-(D57-A)") (class "Default")
      (node (ref "D57") (pin "1") (pinfunction "A_1") (pintype "passive"))
      (node (ref "R92") (pin "1") (pinfunction "1_1") (pintype "passive"))
    )
    (net (code "138") (name "Net-(D58-A)") (class "Default")
      (node (ref "D58") (pin "1") (pinfunction "A_1") (pintype "passive"))
      (node (ref "R95") (pin "1") (pinfunction "1_1") (pintype "passive"))
    )
    (net (code "139") (name "Net-(D64-Pad1)") (class "Default")
      (node (ref "D64") (pin "1") (pinfunction "1_1") (pintype "passive"))
      (node (ref "R102") (pin "1") (pinfunction "1_1") (pintype "passive"))
      (node (ref "R99") (pin "1") (pinfunction "1_1") (pintype "passive"))
      (node (ref "U20") (pin "1") (pinfunction "1_1") (pintype "passive"))
    )
    (net (code "140") (name "Net-(D65-A)") (class "Default")
      (node (ref "D65") (pin "1") (pinfunction "A_1") (pintype "passive"))
      (node (ref "R104") (pin "1") (pinfunction "1_1") (pintype "passive"))
    )
    (net (code "141") (name "Net-(D66-A)") (class "Default")
      (node (ref "D66") (pin "1") (pinfunction "A_1") (pintype "passive"))
      (node (ref "R108") (pin "1") (pinfunction "1_1") (pintype "passive"))
    )
    (net (code "142") (name "Net-(D68-A)") (class "Default")
      (node (ref "D68") (pin "1") (pinfunction "A_1") (pintype "passive"))
      (node (ref "R112") (pin "1") (pinfunction "1_1") (pintype "passive"))
    )
    (net (code "143") (name "Net-(D70-A)") (class "Default")
      (node (ref "D70") (pin "1") (pinfunction "A_1") (pintype "passive"))
      (node (ref "R116") (pin "1") (pinfunction "1_1") (pintype "passive"))
    )
    (net (code "144") (name "Net-(D72-A)") (class "Default")
      (node (ref "D72") (pin "1") (pinfunction "A_1") (pintype "passive"))
      (node (ref "R120") (pin "1") (pinfunction "1_1") (pintype "passive"))
    )
    (net (code "145") (name "Net-(D74-Pad1)") (class "Default")
      (node (ref "D74") (pin "1") (pinfunction "1_1") (pintype "passive"))
      (node (ref "R121") (pin "1") (pinfunction "1_1") (pintype "passive"))
      (node (ref "R124") (pin "1") (pinfunction "1_1") (pintype "passive"))
      (node (ref "U22") (pin "1") (pinfunction "1_1") (pintype "passive"))
    )
    (net (code "146") (name "Net-(D75-Pad1)") (class "Default")
      (node (ref "D75") (pin "1") (pinfunction "1_1") (pintype "passive"))
      (node (ref "R122") (pin "2") (pinfunction "2_2") (pintype "passive"))
      (node (ref "R126") (pin "1") (pinfunction "1_1") (pintype "passive"))
      (node (ref "U23") (pin "1") (pinfunction "1_1") (pintype "passive"))
    )
    (net (code "147") (name "Net-(D76-A)") (class "Default")
      (node (ref "D76") (pin "1") (pinfunction "A_1") (pintype "passive"))
      (node (ref "R127") (pin "1") (pinfunction "1_1") (pintype "passive"))
    )
    (net (code "148") (name "Net-(D77-A)") (class "Default")
      (node (ref "D77") (pin "1") (pinfunction "A_1") (pintype "passive"))
      (node (ref "R128") (pin "1") (pinfunction "1_1") (pintype "passive"))
    )
    (net (code "149") (name "Net-(D78-Pad1)") (class "Default")
      (node (ref "D78") (pin "1") (pinfunction "1_1") (pintype "passive"))
      (node (ref "R129") (pin "1") (pinfunction "1_1") (pintype "passive"))
      (node (ref "R132") (pin "1") (pinfunction "1_1") (pintype "passive"))
      (node (ref "U24") (pin "1") (pinfunction "1_1") (pintype "passive"))
    )
    (net (code "150") (name "Net-(D79-A)") (class "Default")
      (node (ref "D79") (pin "1") (pinfunction "A_1") (pintype "passive"))
      (node (ref "R134") (pin "1") (pinfunction "1_1") (pintype "passive"))
    )
    (net (code "151") (name "Net-(D80-Pad1)") (class "Default")
      (node (ref "D80") (pin "1") (pinfunction "1_1") (pintype "passive"))
      (node (ref "R131") (pin "2") (pinfunction "2_2") (pintype "passive"))
      (node (ref "R133") (pin "1") (pinfunction "1_1") (pintype "passive"))
      (node (ref "U25") (pin "1") (pinfunction "1_1") (pintype "passive"))
    )
    (net (code "152") (name "Net-(D81-A)") (class "Default")
      (node (ref "D81") (pin "1") (pinfunction "A_1") (pintype "passive"))
      (node (ref "R135") (pin "2") (pinfunction "2_2") (pintype "passive"))
    )
    (net (code "153") (name "Net-(D82-A)") (class "Default")
      (node (ref "D82") (pin "1") (pinfunction "A_1") (pintype "passive"))
      (node (ref "R136") (pin "1") (pinfunction "1_1") (pintype "passive"))
    )
    (net (code "154") (name "Net-(D83-Pad1)") (class "Default")
      (node (ref "D83") (pin "1") (pinfunction "1_1") (pintype "passive"))
      (node (ref "R138") (pin "1") (pinfunction "1_1") (pintype "passive"))
      (node (ref "R140") (pin "1") (pinfunction "1_1") (pintype "passive"))
      (node (ref "U26") (pin "1") (pinfunction "1_1") (pintype "passive"))
    )
    (net (code "155") (name "Net-(D84-A)") (class "Default")
      (node (ref "D84") (pin "1") (pinfunction "A_1") (pintype "passive"))
      (node (ref "R141") (pin "1") (pinfunction "1_1") (pintype "passive"))
    )
    (net (code "156") (name "Net-(D85-Pad1)") (class "Default")
      (node (ref "D85") (pin "1") (pinfunction "1_1") (pintype "passive"))
      (node (ref "R145") (pin "1") (pinfunction "1_1") (pintype "passive"))
      (node (ref "R148") (pin "1") (pinfunction "1_1") (pintype "passive"))
      (node (ref "U28") (pin "1") (pinfunction "1_1") (pintype "passive"))
    )
    (net (code "157") (name "Net-(D86-A)") (class "Default")
      (node (ref "D86") (pin "1") (pinfunction "A_1") (pintype "passive"))
      (node (ref "R151") (pin "1") (pinfunction "1_1") (pintype "passive"))
    )
    (net (code "158") (name "Net-(D91-Pad1)") (class "Default")
      (node (ref "D91") (pin "1") (pinfunction "1_1") (pintype "passive"))
      (node (ref "R166") (pin "1") (pinfunction "1_1") (pintype "passive"))
      (node (ref "R167") (pin "1") (pinfunction "1_1") (pintype "passive"))
      (node (ref "U30") (pin "1") (pinfunction "1_1") (pintype "passive"))
    )
    (net (code "159") (name "Net-(D92-A)") (class "Default")
      (node (ref "D92") (pin "1") (pinfunction "A_1") (pintype "passive"))
      (node (ref "R170") (pin "1") (pinfunction "1_1") (pintype "passive"))
    )
    (net (code "160") (name "Net-(D92-K)") (class "Default")
      (node (ref "D91") (pin "2") (pinfunction "2_2") (pintype "passive"))
      (node (ref "D92") (pin "2") (pinfunction "K_2") (pintype "passive"))
      (node (ref "U30") (pin "2") (pinfunction "2_2") (pintype "passive"))
    )
    (net (code "161") (name "Net-(D95-Pad1)") (class "Default")
      (node (ref "D95") (pin "1") (pinfunction "1_1") (pintype "passive"))
      (node (ref "R172") (pin "1") (pinfunction "1_1") (pintype "passive"))
      (node (ref "R173") (pin "1") (pinfunction "1_1") (pintype "passive"))
      (node (ref "U32") (pin "1") (pinfunction "1_1") (pintype "passive"))
    )
    (net (code "162") (name "Net-(D96-A)") (class "Default")
      (node (ref "D96") (pin "1") (pinfunction "A_1") (pintype "passive"))
      (node (ref "R176") (pin "1") (pinfunction "1_1") (pintype "passive"))
    )
    (net (code "163") (name "Net-(D98-A)") (class "Default")
      (node (ref "D98") (pin "1") (pinfunction "A_1") (pintype "passive"))
      (node (ref "R191") (pin "2") (pinfunction "2_2") (pintype "passive"))
    )
    (net (code "164") (name "Net-(D99-Pad1)") (class "Default")
      (node (ref "D99") (pin "1") (pinfunction "1_1") (pintype "passive"))
      (node (ref "P30") (pin "4") (pinfunction "4_4") (pintype "passive"))
      (node (ref "R184") (pin "2") (pinfunction "2_2") (pintype "passive"))
    )
    (net (code "165") (name "Net-(D100-Pad1)") (class "Default")
      (node (ref "D100") (pin "1") (pinfunction "1_1") (pintype "passive"))
      (node (ref "P30") (pin "3") (pinfunction "3_3") (pintype "passive"))
      (node (ref "R187") (pin "2") (pinfunction "2_2") (pintype "passive"))
    )
    (net (code "166") (name "Net-(D101-Pad1)") (class "Default")
      (node (ref "D101") (pin "1") (pinfunction "1_1") (pintype "passive"))
      (node (ref "P30") (pin "2") (pinfunction "2_2") (pintype "passive"))
      (node (ref "R188") (pin "2") (pinfunction "2_2") (pintype "passive"))
    )
    (net (code "167") (name "Net-(D102-Pad1)") (class "Default")
      (node (ref "D102") (pin "1") (pinfunction "1_1") (pintype "passive"))
      (node (ref "R197") (pin "1") (pinfunction "1_1") (pintype "passive"))
      (node (ref "U35") (pin "1") (pinfunction "1_1") (pintype "passive"))
    )
    (net (code "168") (name "Net-(D103-A)") (class "Default")
      (node (ref "D103") (pin "1") (pinfunction "A_1") (pintype "passive"))
      (node (ref "R200") (pin "1") (pinfunction "1_1") (pintype "passive"))
    )
    (net (code "169") (name "Net-(D104-Pad1)") (class "Default")
      (node (ref "D104") (pin "1") (pinfunction "1_1") (pintype "passive"))
      (node (ref "R202") (pin "1") (pinfunction "1_1") (pintype "passive"))
      (node (ref "U36") (pin "1") (pinfunction "1_1") (pintype "passive"))
    )
    (net (code "170") (name "Net-(D105-A)") (class "Default")
      (node (ref "D105") (pin "1") (pinfunction "A_1") (pintype "passive"))
      (node (ref "R205") (pin "1") (pinfunction "1_1") (pintype "passive"))
    )
    (net (code "171") (name "Net-(D106-Pad1)") (class "Default")
      (node (ref "D106") (pin "1") (pinfunction "1_1") (pintype "passive"))
      (node (ref "R206") (pin "1") (pinfunction "1_1") (pintype "passive"))
      (node (ref "U37") (pin "1") (pinfunction "1_1") (pintype "passive"))
    )
    (net (code "172") (name "Net-(D107-A)") (class "Default")
      (node (ref "D107") (pin "1") (pinfunction "A_1") (pintype "passive"))
      (node (ref "R209") (pin "1") (pinfunction "1_1") (pintype "passive"))
    )
    (net (code "173") (name "Net-(D180-Pad1)") (class "Default")
      (node (ref "D180") (pin "1") (pinfunction "1_1") (pintype "passive"))
      (node (ref "R28") (pin "1") (pinfunction "1_1") (pintype "passive"))
      (node (ref "R34") (pin "1") (pinfunction "1_1") (pintype "passive"))
      (node (ref "U9") (pin "1") (pinfunction "1_1") (pintype "passive"))
    )
    (net (code "174") (name "Net-(F2-Pad1)") (class "Default")
      (node (ref "F2") (pin "1") (pinfunction "1_1") (pintype "passive"))
      (node (ref "P20") (pin "1") (pinfunction "1_1") (pintype "passive"))
    )
    (net (code "175") (name "Net-(P14-Pad1)") (class "Default")
      (node (ref "P14") (pin "1") (pinfunction "1_1") (pintype "passive"))
      (node (ref "T1") (pin "4") (pinfunction "4_4") (pintype "passive"))
      (node (ref "T1") (pin "5") (pinfunction "5_5") (pintype "passive"))
    )
    (net (code "176") (name "Net-(P33-Pad1)") (class "Default")
      (node (ref "P33") (pin "1") (pinfunction "1_1") (pintype "passive"))
      (node (ref "P8") (pin "2") (pinfunction "2_2") (pintype "passive"))
    )
    (net (code "177") (name "Net-(P33-Pad2)") (class "Default")
      (node (ref "P33") (pin "2") (pinfunction "2_2") (pintype "passive"))
      (node (ref "R29") (pin "2") (pinfunction "2_2") (pintype "passive"))
      (node (ref "R35") (pin "2") (pinfunction "2_2") (pintype "passive"))
      (node (ref "R38") (pin "2") (pinfunction "2_2") (pintype "passive"))
      (node (ref "R54") (pin "2") (pinfunction "2_2") (pintype "passive"))
    )
    (net (code "178") (name "Net-(Q2-D)") (class "Default")
      (node (ref "P10") (pin "1") (pinfunction "1_1") (pintype "passive"))
      (node (ref "P9") (pin "1") (pinfunction "1_1") (pintype "passive"))
      (node (ref "Q2") (pin "3") (pinfunction "D_3") (pintype "passive"))
      (node (ref "R56") (pin "2") (pinfunction "2_2") (pintype "passive"))
    )
    (net (code "179") (name "Net-(Q2-G)") (class "Default")
      (node (ref "Q2") (pin "1") (pinfunction "G_1") (pintype "passive"))
      (node (ref "R52") (pin "1") (pinfunction "1_1") (pintype "passive"))
      (node (ref "R53") (pin "2") (pinfunction "2_2") (pintype "passive"))
    )
    (net (code "180") (name "Net-(Q3-B)") (class "Default")
      (node (ref "Q3") (pin "1") (pinfunction "B_1") (pintype "passive"))
      (node (ref "R54") (pin "1") (pinfunction "1_1") (pintype "passive"))
      (node (ref "R55") (pin "1") (pinfunction "1_1") (pintype "passive"))
    )
    (net (code "181") (name "Net-(Q3-C)") (class "Default")
      (node (ref "Q3") (pin "3") (pinfunction "C_3") (pintype "passive"))
      (node (ref "R51") (pin "2") (pinfunction "2_2") (pintype "passive"))
      (node (ref "R53") (pin "1") (pinfunction "1_1") (pintype "passive"))
    )
    (net (code "182") (name "Net-(Q4-B)") (class "Default")
      (node (ref "Q4") (pin "1") (pinfunction "B_1") (pintype "passive"))
      (node (ref "R77") (pin "2") (pinfunction "2_2") (pintype "passive"))
      (node (ref "R78") (pin "1") (pinfunction "1_1") (pintype "passive"))
    )
    (net (code "183") (name "Net-(Q4-C)") (class "Default")
      (node (ref "C46") (pin "2") (pinfunction "2_2") (pintype "passive"))
      (node (ref "D46") (pin "1") (pinfunction "1_1") (pintype "passive"))
      (node (ref "K1") (pin "1") (pinfunction "1_1") (pintype "passive"))
      (node (ref "Q4") (pin "3") (pinfunction "C_3") (pintype "passive"))
      (node (ref "R83") (pin "2") (pinfunction "2_2") (pintype "passive"))
    )
    (net (code "184") (name "Net-(Q5-B)") (class "Default")
      (node (ref "Q5") (pin "1") (pinfunction "B_1") (pintype "passive"))
      (node (ref "R90") (pin "2") (pinfunction "2_2") (pintype "passive"))
      (node (ref "R93") (pin "1") (pinfunction "1_1") (pintype "passive"))
    )
    (net (code "185") (name "Net-(Q6-G)") (class "Default")
      (node (ref "Q6") (pin "1") (pinfunction "G_1") (pintype "passive"))
      (node (ref "R100") (pin "1") (pinfunction "1_1") (pintype "passive"))
      (node (ref "R101") (pin "1") (pinfunction "1_1") (pintype "passive"))
    )
    (net (code "186") (name "Net-(Q7-B)") (class "Default")
      (node (ref "Q7") (pin "1") (pinfunction "B_1") (pintype "passive"))
      (node (ref "R137") (pin "1") (pinfunction "1_1") (pintype "passive"))
      (node (ref "R142") (pin "2") (pinfunction "2_2") (pintype "passive"))
    )
    (net (code "187") (name "Net-(Q7-E)") (class "Default")
      (node (ref "Q7") (pin "2") (pinfunction "E_2") (pintype "passive"))
      (node (ref "Q8") (pin "3") (pinfunction "C_3") (pintype "passive"))
    )
    (net (code "188") (name "Net-(Q8-B)") (class "Default")
      (node (ref "Q8") (pin "1") (pinfunction "B_1") (pintype "passive"))
      (node (ref "R143") (pin "1") (pinfunction "1_1") (pintype "passive"))
      (node (ref "R144") (pin "2") (pinfunction "2_2") (pintype "passive"))
    )
    (net (code "189") (name "Net-(Q9-B)") (class "Default")
      (node (ref "Q9") (pin "1") (pinfunction "B_1") (pintype "passive"))
      (node (ref "R157") (pin "1") (pinfunction "1_1") (pintype "passive"))
      (node (ref "R160") (pin "1") (pinfunction "1_1") (pintype "passive"))
    )
    (net (code "190") (name "Net-(Q10-B)") (class "Default")
      (node (ref "Q10") (pin "1") (pinfunction "B_1") (pintype "passive"))
      (node (ref "R158") (pin "1") (pinfunction "1_1") (pintype "passive"))
      (node (ref "R161") (pin "1") (pinfunction "1_1") (pintype "passive"))
    )
    (net (code "191") (name "Net-(Q11-B)") (class "Default")
      (node (ref "Q11") (pin "1") (pinfunction "B_1") (pintype "passive"))
      (node (ref "R163") (pin "1") (pinfunction "1_1") (pintype "passive"))
    )
    (net (code "192") (name "Net-(Q11-C)") (class "Default")
      (node (ref "Q11") (pin "3") (pinfunction "C_3") (pintype "passive"))
      (node (ref "R160") (pin "2") (pinfunction "2_2") (pintype "passive"))
      (node (ref "R161") (pin "2") (pinfunction "2_2") (pintype "passive"))
    )
    (net (code "193") (name "Net-(Q11-E)") (class "Default")
      (node (ref "Q11") (pin "2") (pinfunction "E_2") (pintype "passive"))
      (node (ref "Q12") (pin "3") (pinfunction "C_3") (pintype "passive"))
    )
    (net (code "194") (name "Net-(Q12-B)") (class "Default")
      (node (ref "Q12") (pin "1") (pinfunction "B_1") (pintype "passive"))
      (node (ref "R164") (pin "1") (pinfunction "1_1") (pintype "passive"))
    )
    (net (code "195") (name "Net-(Q14-B)") (class "Default")
      (node (ref "Q14") (pin "1") (pinfunction "B_1") (pintype "passive"))
      (node (ref "R201") (pin "1") (pinfunction "1_1") (pintype "passive"))
    )
    (net (code "196") (name "Net-(Q20-B)") (class "Default")
      (node (ref "Q20") (pin "1") (pinfunction "B_1") (pintype "passive"))
      (node (ref "R194") (pin "1") (pinfunction "1_1") (pintype "passive"))
      (node (ref "R195") (pin "1") (pinfunction "1_1") (pintype "passive"))
    )
    (net (code "197") (name "Net-(Q20-C)") (class "Default")
      (node (ref "B1") (pin "1") (pinfunction "1_1") (pintype "passive"))
      (node (ref "D111") (pin "2") (pinfunction "2_2") (pintype "passive"))
      (node (ref "Q20") (pin "3") (pinfunction "C_3") (pintype "passive"))
    )
    (net (code "198") (name "Net-(R137-Pad2)") (class "Default")
      (node (ref "R137") (pin "2") (pinfunction "2_2") (pintype "passive"))
      (node (ref "U25") (pin "3") (pinfunction "3_3") (pintype "passive"))
    )
    (net (code "199") (name "Net-(U1-A)") (class "Default")
      (node (ref "L8") (pin "2") (pinfunction "2_2") (pintype "passive"))
      (node (ref "U1") (pin "11") (pinfunction "A_11") (pintype "passive"))
    )
    (net (code "200") (name "Net-(U1-B)") (class "Default")
      (node (ref "L8") (pin "1") (pinfunction "1_1") (pintype "passive"))
      (node (ref "U1") (pin "10") (pinfunction "B_10") (pintype "passive"))
    )
    (net (code "201") (name "Net-(U1-Y)") (class "Default")
      (node (ref "L11") (pin "1") (pinfunction "1_1") (pintype "passive"))
      (node (ref "U1") (pin "8") (pinfunction "Y_8") (pintype "passive"))
    )
    (net (code "202") (name "Net-(U1-Z)") (class "Default")
      (node (ref "L11") (pin "2") (pinfunction "2_2") (pintype "passive"))
      (node (ref "U1") (pin "9") (pinfunction "Z_9") (pintype "passive"))
    )
    (net (code "203") (name "Net-(U2-CANH)") (class "Default")
      (node (ref "L1") (pin "4") (pinfunction "4_4") (pintype "passive"))
      (node (ref "U2") (pin "6") (pinfunction "CANH_6") (pintype "passive"))
    )
    (net (code "204") (name "Net-(U2-CANL)") (class "Default")
      (node (ref "L1") (pin "3") (pinfunction "3_3") (pintype "passive"))
      (node (ref "U2") (pin "7") (pinfunction "CANL_7") (pintype "passive"))
    )
    (net (code "205") (name "Net-(U3-VOUT)") (class "Default")
      (node (ref "D8") (pin "1") (pinfunction "1_1") (pintype "passive"))
      (node (ref "L2") (pin "1") (pinfunction "1_1") (pintype "passive"))
      (node (ref "U3") (pin "2") (pinfunction "VOUT_2") (pintype "passive"))
    )
    (net (code "206") (name "Net-(U4-CB)") (class "Default")
      (node (ref "C14") (pin "1") (pinfunction "1_1") (pintype "passive"))
      (node (ref "U4") (pin "1") (pinfunction "CB_1") (pintype "passive"))
    )
    (net (code "207") (name "Net-(U4-VSW)") (class "Default")
      (node (ref "C14") (pin "2") (pinfunction "2_2") (pintype "passive"))
      (node (ref "D10") (pin "1") (pinfunction "1_1") (pintype "passive"))
      (node (ref "L3") (pin "1") (pinfunction "1_1") (pintype "passive"))
      (node (ref "U4") (pin "8") (pinfunction "VSW_8") (pintype "passive"))
    )
    (net (code "208") (name "Net-(U5-A)") (class "Default")
      (node (ref "L6") (pin "2") (pinfunction "2_2") (pintype "passive"))
      (node (ref "U5") (pin "11") (pinfunction "A_11") (pintype "passive"))
    )
    (net (code "209") (name "Net-(U5-B)") (class "Default")
      (node (ref "L6") (pin "1") (pinfunction "1_1") (pintype "passive"))
      (node (ref "U5") (pin "10") (pinfunction "B_10") (pintype "passive"))
    )
    (net (code "210") (name "Net-(U5-Y)") (class "Default")
      (node (ref "L7") (pin "1") (pinfunction "1_1") (pintype "passive"))
      (node (ref "U5") (pin "8") (pinfunction "Y_8") (pintype "passive"))
    )
    (net (code "211") (name "Net-(U5-Z)") (class "Default")
      (node (ref "L7") (pin "2") (pinfunction "2_2") (pintype "passive"))
      (node (ref "U5") (pin "9") (pinfunction "Z_9") (pintype "passive"))
    )
    (net (code "212") (name "Net-(U6-CANH)") (class "Default")
      (node (ref "L4") (pin "2") (pinfunction "2_2") (pintype "passive"))
      (node (ref "U6") (pin "6") (pinfunction "CANH_6") (pintype "passive"))
    )
    (net (code "213") (name "Net-(U6-CANL)") (class "Default")
      (node (ref "L4") (pin "1") (pinfunction "1_1") (pintype "passive"))
      (node (ref "U6") (pin "7") (pinfunction "CANL_7") (pintype "passive"))
    )
    (net (code "214") (name "Net-(U14-A)") (class "Default")
      (node (ref "L5") (pin "1") (pinfunction "1_1") (pintype "passive"))
      (node (ref "R58") (pin "2") (pinfunction "2_2") (pintype "passive"))
      (node (ref "U14") (pin "6") (pinfunction "A_6") (pintype "passive"))
    )
    (net (code "215") (name "Net-(U14-B)") (class "Default")
      (node (ref "L5") (pin "2") (pinfunction "2_2") (pintype "passive"))
      (node (ref "R67") (pin "1") (pinfunction "1_1") (pintype "passive"))
      (node (ref "U14") (pin "7") (pinfunction "B_7") (pintype "passive"))
    )
    (net (code "216") (name "Net-(U14-VO)") (class "Default")
      (node (ref "R58") (pin "1") (pinfunction "1_1") (pintype "passive"))
      (node (ref "U14") (pin "8") (pinfunction "VO_8") (pintype "passive"))
    )
    (net (code "217") (name "Net-(U19-R_IN)") (class "Default")
      (node (ref "D63") (pin "2") (pinfunction "2_2") (pintype "passive"))
      (node (ref "R98") (pin "2") (pinfunction "2_2") (pintype "passive"))
      (node (ref "U19") (pin "4") (pinfunction "R_IN_4") (pintype "passive"))
    )
    (net (code "218") (name "Net-(U19-T_OUT)") (class "Default")
      (node (ref "D61") (pin "2") (pinfunction "2_2") (pintype "passive"))
      (node (ref "R97") (pin "2") (pinfunction "2_2") (pintype "passive"))
      (node (ref "U19") (pin "3") (pinfunction "T_OUT_3") (pintype "passive"))
    )
    (net (code "219") (name "Net-(U21-AN1)") (class "Default")
      (node (ref "D67") (pin "1") (pinfunction "1_1") (pintype "passive"))
      (node (ref "R106") (pin "1") (pinfunction "1_1") (pintype "passive"))
      (node (ref "R107") (pin "1") (pinfunction "1_1") (pintype "passive"))
      (node (ref "U21") (pin "1") (pinfunction "AN1_1") (pintype "passive"))
    )
    (net (code "220") (name "Net-(U21-AN2)") (class "Default")
      (node (ref "D69") (pin "1") (pinfunction "1_1") (pintype "passive"))
      (node (ref "R109") (pin "1") (pinfunction "1_1") (pintype "passive"))
      (node (ref "R111") (pin "1") (pinfunction "1_1") (pintype "passive"))
      (node (ref "U21") (pin "3") (pinfunction "AN2_3") (pintype "passive"))
    )
    (net (code "221") (name "Net-(U21-AN3)") (class "Default")
      (node (ref "D17") (pin "1") (pinfunction "1_1") (pintype "passive"))
      (node (ref "R113") (pin "1") (pinfunction "1_1") (pintype "passive"))
      (node (ref "R114") (pin "1") (pinfunction "1_1") (pintype "passive"))
      (node (ref "U21") (pin "5") (pinfunction "AN3_5") (pintype "passive"))
    )
    (net (code "222") (name "Net-(U21-AN4)") (class "Default")
      (node (ref "D73") (pin "1") (pinfunction "1_1") (pintype "passive"))
      (node (ref "R117") (pin "1") (pinfunction "1_1") (pintype "passive"))
      (node (ref "R118") (pin "1") (pinfunction "1_1") (pintype "passive"))
      (node (ref "U21") (pin "7") (pinfunction "AN4_7") (pintype "passive"))
    )
    (net (code "223") (name "Net-(U27-3A)") (class "Default")
      (node (ref "R153") (pin "2") (pinfunction "2_2") (pintype "passive"))
      (node (ref "U27") (pin "10") (pinfunction "3A_10") (pintype "passive"))
    )
    (net (code "224") (name "Net-(U27-3B)") (class "Default")
      (node (ref "R154") (pin "2") (pinfunction "2_2") (pintype "passive"))
      (node (ref "U27") (pin "9") (pinfunction "3B_9") (pintype "passive"))
    )
    (net (code "225") (name "Net-(U27-4A)") (class "Default")
      (node (ref "R149") (pin "2") (pinfunction "2_2") (pintype "passive"))
      (node (ref "U27") (pin "14") (pinfunction "4A_14") (pintype "passive"))
    )
    (net (code "226") (name "Net-(U27-4B)") (class "Default")
      (node (ref "R147") (pin "2") (pinfunction "2_2") (pintype "passive"))
      (node (ref "U27") (pin "15") (pinfunction "4B_15") (pintype "passive"))
    )
    (net (code "227") (name "Net-(U29-A)") (class "Default")
      (node (ref "D89") (pin "2") (pinfunction "2_2") (pintype "passive"))
      (node (ref "R165") (pin "1") (pinfunction "1_1") (pintype "passive"))
      (node (ref "U29") (pin "1") (pinfunction "A_1") (pintype "passive"))
    )
    (net (code "228") (name "Net-(U29-B)") (class "Default")
      (node (ref "D90") (pin "2") (pinfunction "2_2") (pintype "passive"))
      (node (ref "R168") (pin "1") (pinfunction "1_1") (pintype "passive"))
      (node (ref "U29") (pin "2") (pinfunction "B_2") (pintype "passive"))
    )
    (net (code "229") (name "Net-(U29-Y)") (class "Default")
      (node (ref "R163") (pin "2") (pinfunction "2_2") (pintype "passive"))
      (node (ref "R166") (pin "2") (pinfunction "2_2") (pintype "passive"))
      (node (ref "R167") (pin "2") (pinfunction "2_2") (pintype "passive"))
      (node (ref "R170") (pin "2") (pinfunction "2_2") (pintype "passive"))
      (node (ref "U29") (pin "4") (pinfunction "Y_4") (pintype "passive"))
    )
    (net (code "230") (name "Net-(U31-A)") (class "Default")
      (node (ref "D93") (pin "2") (pinfunction "2_2") (pintype "passive"))
      (node (ref "R171") (pin "1") (pinfunction "1_1") (pintype "passive"))
      (node (ref "U31") (pin "1") (pinfunction "A_1") (pintype "passive"))
    )
    (net (code "231") (name "Net-(U31-B)") (class "Default")
      (node (ref "D94") (pin "2") (pinfunction "2_2") (pintype "passive"))
      (node (ref "R174") (pin "1") (pinfunction "1_1") (pintype "passive"))
      (node (ref "U31") (pin "2") (pinfunction "B_2") (pintype "passive"))
    )
    (net (code "232") (name "Net-(U31-Y)") (class "Default")
      (node (ref "R164") (pin "2") (pinfunction "2_2") (pintype "passive"))
      (node (ref "R172") (pin "2") (pinfunction "2_2") (pintype "passive"))
      (node (ref "R173") (pin "2") (pinfunction "2_2") (pintype "passive"))
      (node (ref "R176") (pin "2") (pinfunction "2_2") (pintype "passive"))
      (node (ref "U31") (pin "4") (pinfunction "Y_4") (pintype "passive"))
    )
    (net (code "233") (name "Net-(U33A-BOOT0)") (class "Default")
      (node (ref "R179") (pin "1") (pinfunction "1_1") (pintype "passive"))
      (node (ref "U33") (pin "94") (pinfunction "BOOT0_94") (pintype "passive"))
    )
    (net (code "234") (name "Net-(U33A-PB2-BOOT1(PB2))") (class "Default")
      (node (ref "R181") (pin "1") (pinfunction "1_1") (pintype "passive"))
      (node (ref "U33") (pin "37") (pinfunction "PB2-BOOT1(PB2)_37") (pintype "passive"))
    )
    (net (code "235") (name "Net-(U33A-VCAP_1)") (class "Default")
      (node (ref "C84") (pin "2") (pinfunction "2_2") (pintype "passive"))
      (node (ref "U33") (pin "49") (pinfunction "VCAP_1_49") (pintype "passive"))
    )
    (net (code "236") (name "Net-(U33A-VCAP_2)") (class "Default")
      (node (ref "C82") (pin "1") (pinfunction "1_1") (pintype "passive"))
      (node (ref "U33") (pin "73") (pinfunction "VCAP_2_73") (pintype "passive"))
    )
    (net (code "237") (name "Net-(X1-OUTPUT)") (class "Default")
      (node (ref "R2") (pin "2") (pintype "passive"))
      (node (ref "X1") (pin "3") (pinfunction "OUTPUT_3") (pintype "passive"))
    )
    (net (code "238") (name "VDDA") (class "Default")
      (node (ref "C76") (pin "2") (pinfunction "2_2") (pintype "passive"))
      (node (ref "C77") (pin "2") (pinfunction "2_2") (pintype "passive"))
      (node (ref "L10") (pin "2") (pinfunction "2_2") (pintype "passive"))
      (node (ref "U33") (pin "21") (pinfunction "VREF+_21") (pintype "passive"))
      (node (ref "U33") (pin "22") (pinfunction "VDDA_22") (pintype "passive"))
    )
    (net (code "239") (name "VSSA") (class "Default")
      (node (ref "C76") (pin "1") (pinfunction "1_1") (pintype "passive"))
      (node (ref "C77") (pin "1") (pinfunction "1_1") (pintype "passive"))
      (node (ref "L9") (pin "2") (pinfunction "2_2") (pintype "passive"))
      (node (ref "U33") (pin "20") (pinfunction "VSSA_20") (pintype "passive"))
    )
    (net (code "240") (name "unconnected-(K1-Pad2)") (class "Default")
      (node (ref "K1") (pin "2") (pinfunction "2_2") (pintype "passive+no_connect"))
    )
    (net (code "241") (name "unconnected-(K1-Pad7)") (class "Default")
      (node (ref "K1") (pin "7") (pinfunction "7_7") (pintype "passive+no_connect"))
    )
    (net (code "242") (name "unconnected-(P24-Pad4)") (class "Default")
      (node (ref "P24") (pin "4") (pinfunction "4_4") (pintype "passive+no_connect"))
    )
    (net (code "243") (name "unconnected-(T1-Pad2)") (class "Default")
      (node (ref "T1") (pin "2") (pinfunction "2_2") (pintype "passive+no_connect"))
    )
    (net (code "244") (name "unconnected-(T1-Pad7)") (class "Default")
      (node (ref "T1") (pin "7") (pinfunction "7_7") (pintype "passive+no_connect"))
    )
    (net (code "245") (name "unconnected-(U1-VO-Pad12)") (class "Default")
      (node (ref "U1") (pin "12") (pinfunction "VO_12") (pintype "passive"))
    )
    (net (code "246") (name "unconnected-(U3-PAD-Pad6)") (class "Default")
      (node (ref "U3") (pin "6") (pinfunction "PAD_6") (pintype "passive+no_connect"))
    )
    (net (code "247") (name "unconnected-(U4-ON{slash}OFF#-Pad5)") (class "Default")
      (node (ref "U4") (pin "5") (pinfunction "ON/OFF#_5") (pintype "passive+no_connect"))
    )
    (net (code "248") (name "unconnected-(U4-SS-Pad2)") (class "Default")
      (node (ref "U4") (pin "2") (pinfunction "SS_2") (pintype "passive+no_connect"))
    )
    (net (code "249") (name "unconnected-(U4-SYNC-Pad3)") (class "Default")
      (node (ref "U4") (pin "3") (pinfunction "SYNC_3") (pintype "passive+no_connect"))
    )
    (net (code "250") (name "unconnected-(U5-VO-Pad12)") (class "Default")
      (node (ref "U5") (pin "12") (pinfunction "VO_12") (pintype "passive"))
    )
    (net (code "251") (name "unconnected-(U19-NC-Pad6)") (class "Default")
      (node (ref "U19") (pin "6") (pinfunction "NC_6") (pintype "passive+no_connect"))
    )
    (net (code "252") (name "unconnected-(U19-NC-Pad7)") (class "Default")
      (node (ref "U19") (pin "7") (pinfunction "NC_7") (pintype "passive+no_connect"))
    )
    (net (code "253") (name "unconnected-(U27-3Y-Pad11)") (class "Default")
      (node (ref "U27") (pin "11") (pinfunction "3Y_11") (pintype "passive+no_connect"))
    )
    (net (code "254") (name "unconnected-(U27-4Y-Pad13)") (class "Default")
      (node (ref "U27") (pin "13") (pinfunction "4Y_13") (pintype "passive+no_connect"))
    )
    (net (code "255") (name "unconnected-(U33A-PA0-WKUP(PA0)-Pad23)") (class "Default")
      (node (ref "U33") (pin "23") (pinfunction "PA0-WKUP(PA0)_23") (pintype "passive+no_connect"))
    )
    (net (code "256") (name "unconnected-(U33A-PA1-Pad24)") (class "Default")
      (node (ref "U33") (pin "24") (pinfunction "PA1_24") (pintype "passive+no_connect"))
    )
    (net (code "257") (name "unconnected-(U33A-PA2-Pad25)") (class "Default")
      (node (ref "U33") (pin "25") (pinfunction "PA2_25") (pintype "passive+no_connect"))
    )
    (net (code "258") (name "unconnected-(U33A-PA9-Pad68)") (class "Default")
      (node (ref "U33") (pin "68") (pinfunction "PA9_68") (pintype "passive"))
    )
    (net (code "259") (name "unconnected-(U33A-PA10-Pad69)") (class "Default")
      (node (ref "U33") (pin "69") (pinfunction "PA10_69") (pintype "passive"))
    )
    (net (code "260") (name "unconnected-(U33A-PB0-Pad35)") (class "Default")
      (node (ref "U33") (pin "35") (pinfunction "PB0_35") (pintype "passive+no_connect"))
    )
    (net (code "261") (name "unconnected-(U33A-PB1-Pad36)") (class "Default")
      (node (ref "U33") (pin "36") (pinfunction "PB1_36") (pintype "passive+no_connect"))
    )
    (net (code "262") (name "unconnected-(U33A-PB14-Pad53)") (class "Default")
      (node (ref "U33") (pin "53") (pinfunction "PB14_53") (pintype "passive+no_connect"))
    )
    (net (code "263") (name "unconnected-(U33A-PB15-Pad54)") (class "Default")
      (node (ref "U33") (pin "54") (pinfunction "PB15_54") (pintype "passive+no_connect"))
    )
    (net (code "264") (name "unconnected-(U33A-PC5-Pad34)") (class "Default")
      (node (ref "U33") (pin "34") (pinfunction "PC5_34") (pintype "passive+no_connect"))
    )
    (net (code "265") (name "unconnected-(U33A-PC6-Pad63)") (class "Default")
      (node (ref "U33") (pin "63") (pinfunction "PC6_63") (pintype "passive+no_connect"))
    )
    (net (code "266") (name "unconnected-(U33A-PC7-Pad64)") (class "Default")
      (node (ref "U33") (pin "64") (pinfunction "PC7_64") (pintype "passive+no_connect"))
    )
    (net (code "267") (name "unconnected-(U33A-PC15-OSC32_OUT(PC15)-Pad9)") (class "Default")
      (node (ref "U33") (pin "9") (pinfunction "PC15-OSC32_OUT(PC15)_9") (pintype "passive+no_connect"))
    )
    (net (code "268") (name "unconnected-(U33A-PD0-Pad81)") (class "Default")
      (node (ref "U33") (pin "81") (pinfunction "PD0_81") (pintype "passive+no_connect"))
    )
    (net (code "269") (name "unconnected-(U33A-PD1-Pad82)") (class "Default")
      (node (ref "U33") (pin "82") (pinfunction "PD1_82") (pintype "passive+no_connect"))
    )
    (net (code "270") (name "unconnected-(U33A-PD3-Pad84)") (class "Default")
      (node (ref "U33") (pin "84") (pinfunction "PD3_84") (pintype "passive+no_connect"))
    )
    (net (code "271") (name "unconnected-(U33A-PD4-Pad85)") (class "Default")
      (node (ref "U33") (pin "85") (pinfunction "PD4_85") (pintype "passive+no_connect"))
    )
    (net (code "272") (name "unconnected-(U33A-PD7-Pad88)") (class "Default")
      (node (ref "U33") (pin "88") (pinfunction "PD7_88") (pintype "passive+no_connect"))
    )
    (net (code "273") (name "unconnected-(U33A-PD8-Pad55)") (class "Default")
      (node (ref "U33") (pin "55") (pinfunction "PD8_55") (pintype "passive+no_connect"))
    )
    (net (code "274") (name "unconnected-(U33A-PD12-Pad59)") (class "Default")
      (node (ref "U33") (pin "59") (pinfunction "PD12_59") (pintype "passive+no_connect"))
    )
    (net (code "275") (name "unconnected-(U33A-PD13-Pad60)") (class "Default")
      (node (ref "U33") (pin "60") (pinfunction "PD13_60") (pintype "passive+no_connect"))
    )
    (net (code "276") (name "unconnected-(U33A-PE0-Pad97)") (class "Default")
      (node (ref "U33") (pin "97") (pinfunction "PE0_97") (pintype "passive+no_connect"))
    )
    (net (code "277") (name "unconnected-(U33A-PE1-Pad98)") (class "Default")
      (node (ref "U33") (pin "98") (pinfunction "PE1_98") (pintype "passive+no_connect"))
    )
    (net (code "278") (name "unconnected-(U33A-PE5-Pad4)") (class "Default")
      (node (ref "U33") (pin "4") (pinfunction "PE5_4") (pintype "passive+no_connect"))
    )
    (net (code "279") (name "unconnected-(U33A-PE7-Pad38)") (class "Default")
      (node (ref "U33") (pin "38") (pinfunction "PE7_38") (pintype "passive+no_connect"))
    )
    (net (code "280") (name "unconnected-(U33A-PE8-Pad39)") (class "Default")
      (node (ref "U33") (pin "39") (pinfunction "PE8_39") (pintype "passive+no_connect"))
    )
    (net (code "281") (name "unconnected-(U33A-PE9-Pad40)") (class "Default")
      (node (ref "U33") (pin "40") (pinfunction "PE9_40") (pintype "passive+no_connect"))
    )
    (net (code "282") (name "unconnected-(U33A-PE10-Pad41)") (class "Default")
      (node (ref "U33") (pin "41") (pinfunction "PE10_41") (pintype "passive+no_connect"))
    )
    (net (code "283") (name "unconnected-(U33A-PE11-Pad42)") (class "Default")
      (node (ref "U33") (pin "42") (pinfunction "PE11_42") (pintype "passive+no_connect"))
    )
    (net (code "284") (name "unconnected-(U33A-PE12-Pad43)") (class "Default")
      (node (ref "U33") (pin "43") (pinfunction "PE12_43") (pintype "passive+no_connect"))
    )
    (net (code "285") (name "unconnected-(U33A-PH1-OSC_OUT(PH1)-Pad13)") (class "Default")
      (node (ref "U33") (pin "13") (pinfunction "PH1-OSC_OUT(PH1)_13") (pintype "passive"))
    )
  )
)
